# ProDoc_ZYNQ7020_V1_2024-12-19.net
KiCad netlist of a schematic drawn in EasyEDA Pro
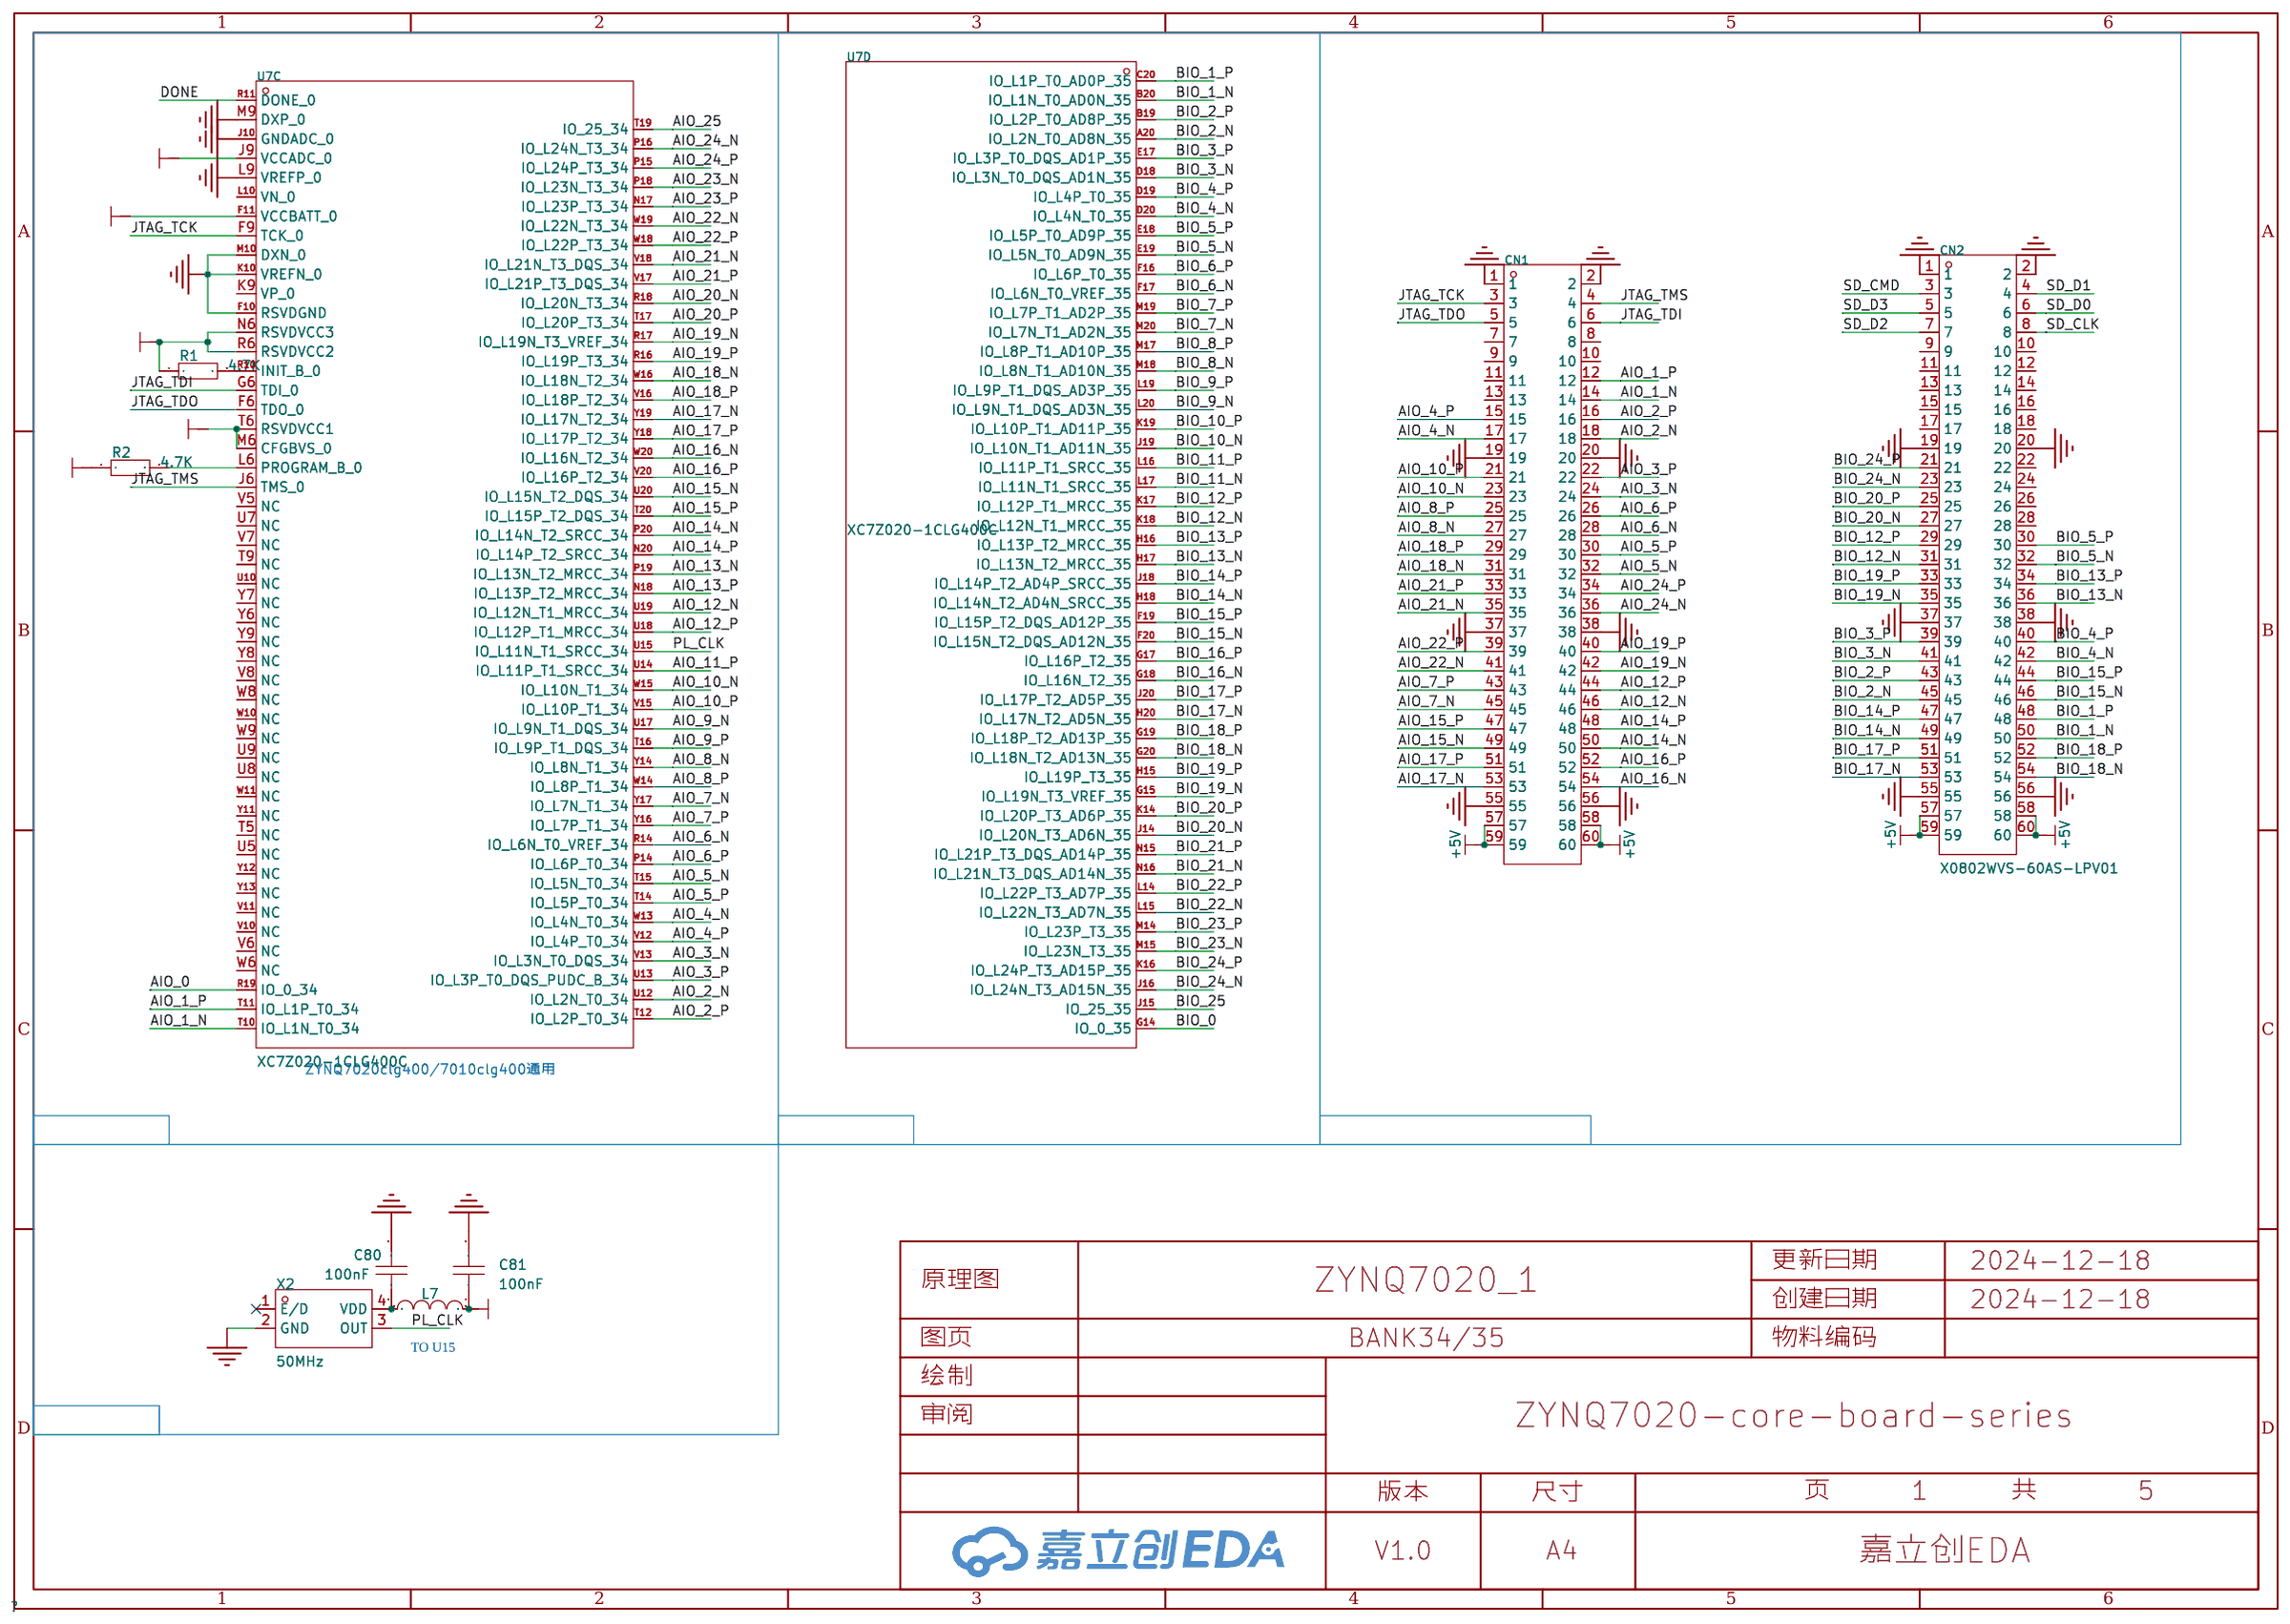
[diagram p0: BANK34/35]
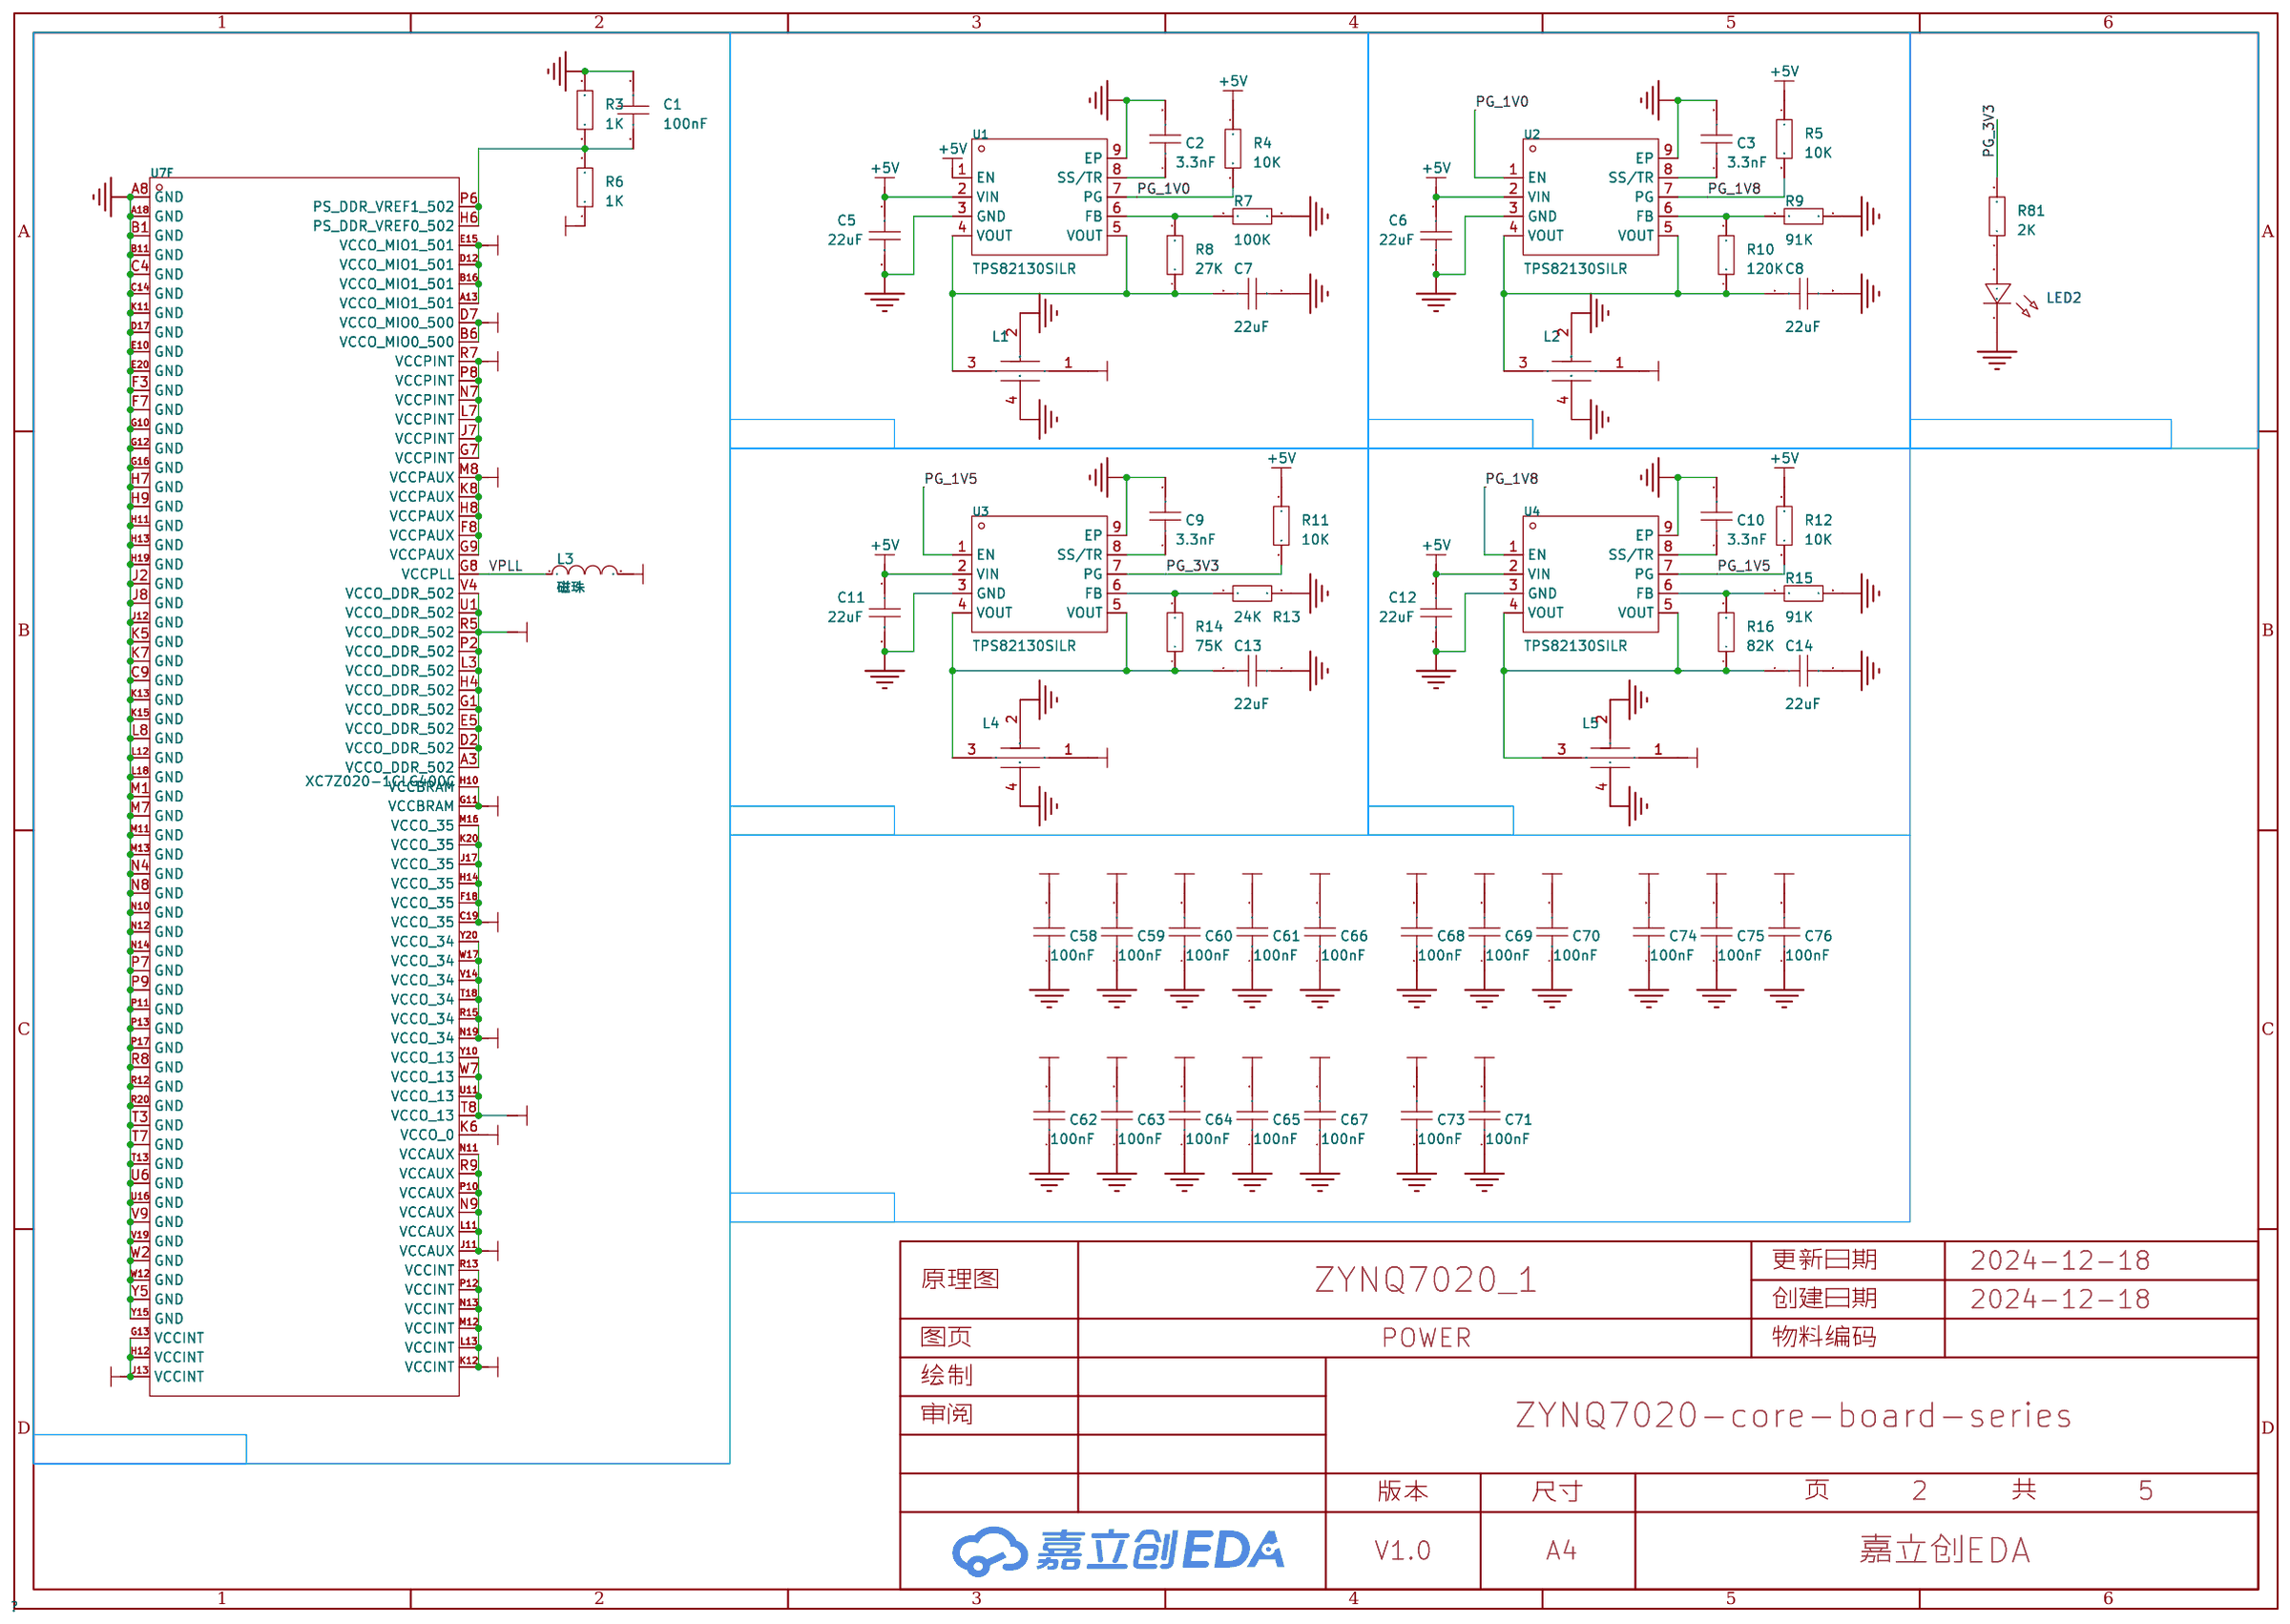
[diagram p1: POWER]
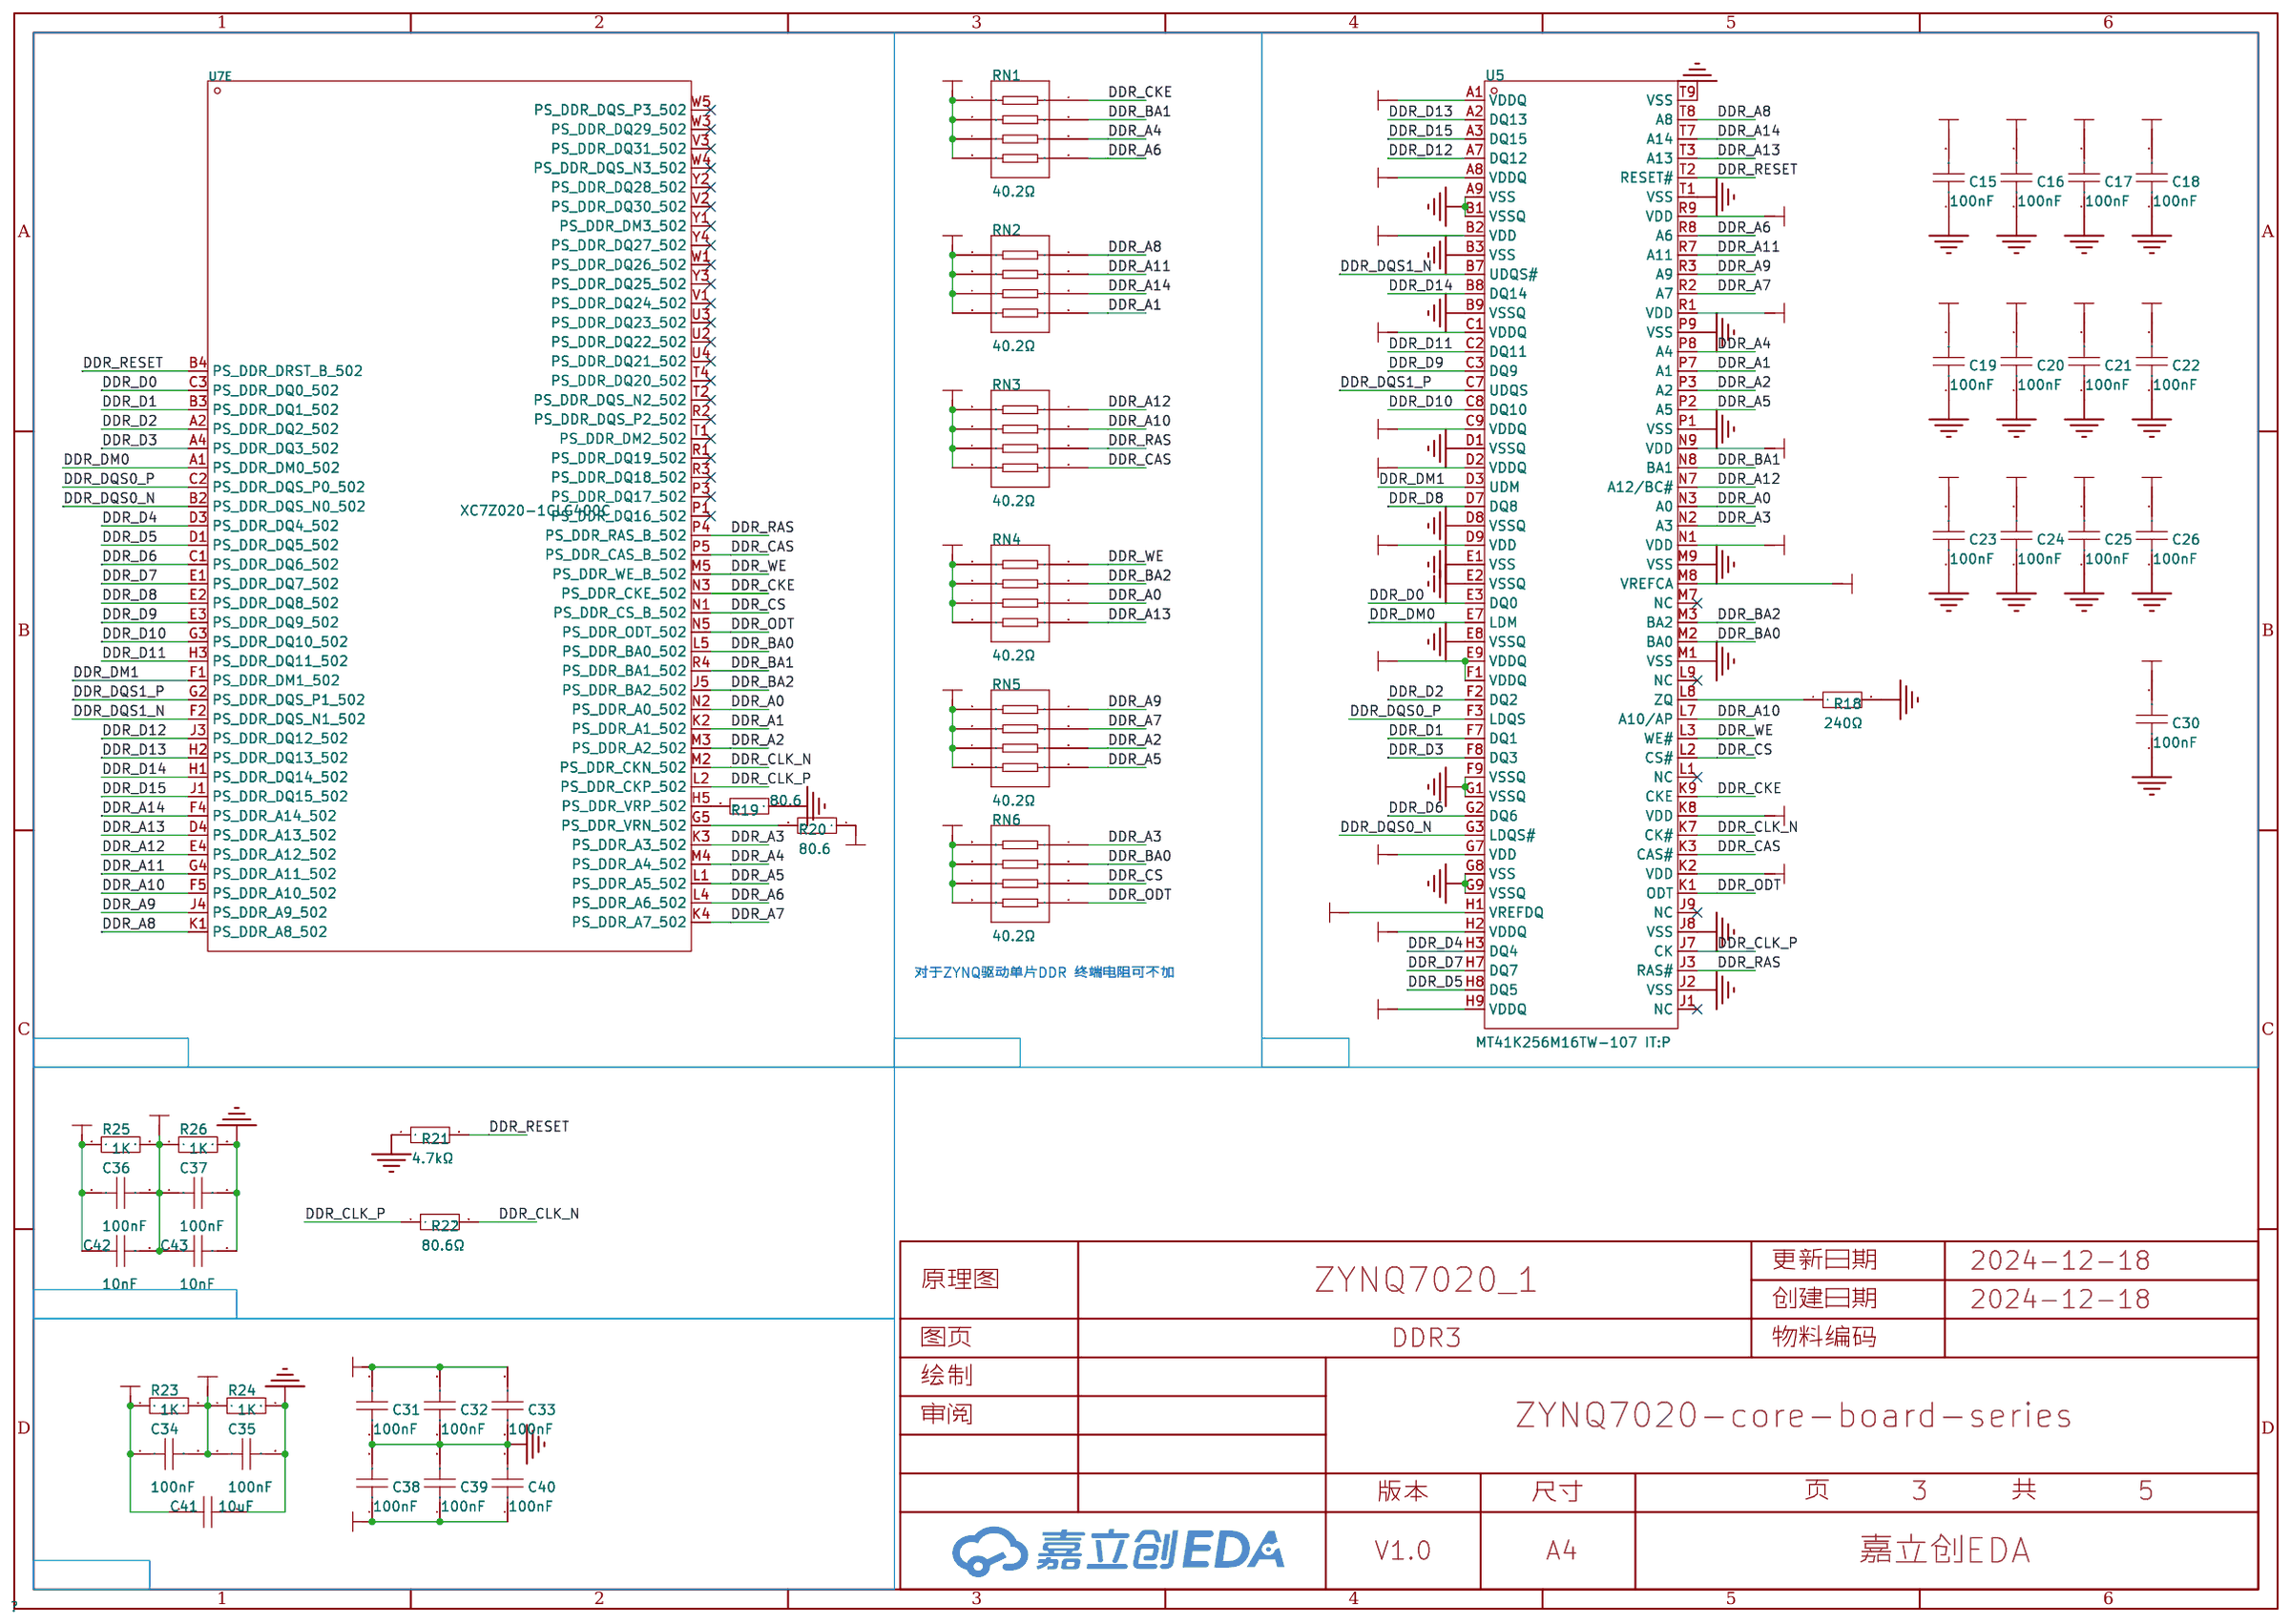
[diagram p2: DDR3]
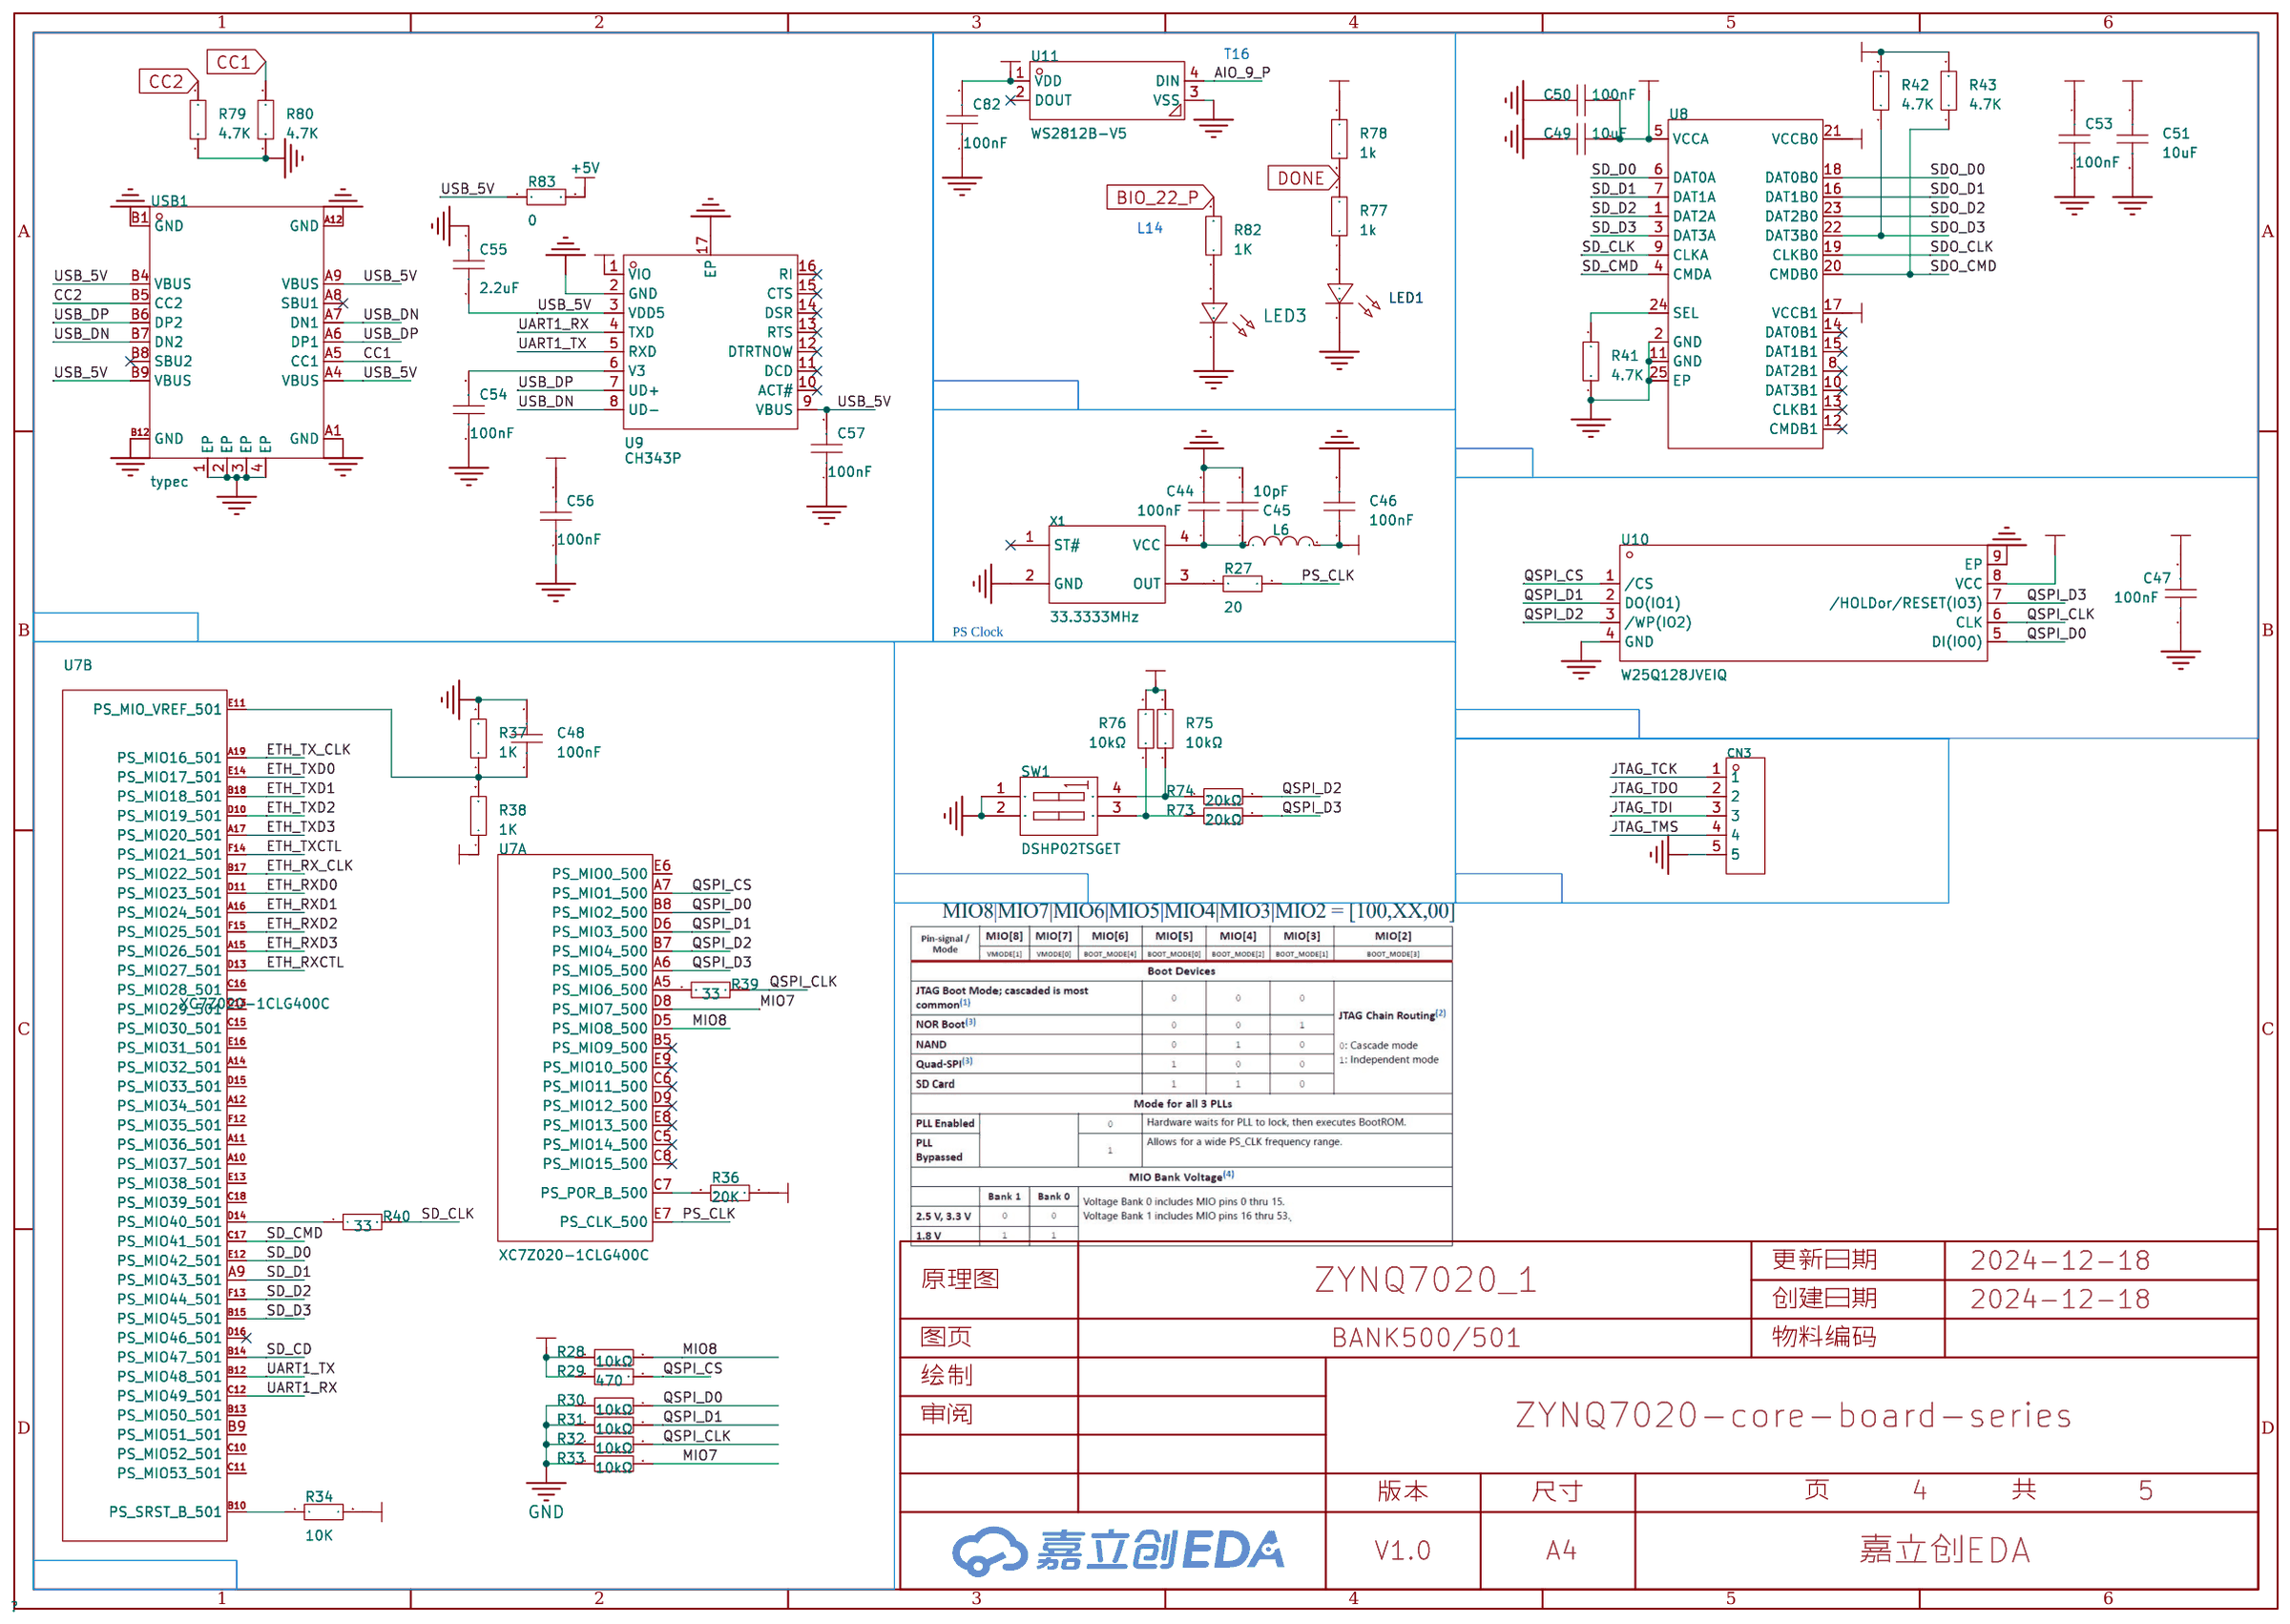
[diagram p3: BANK500/501]
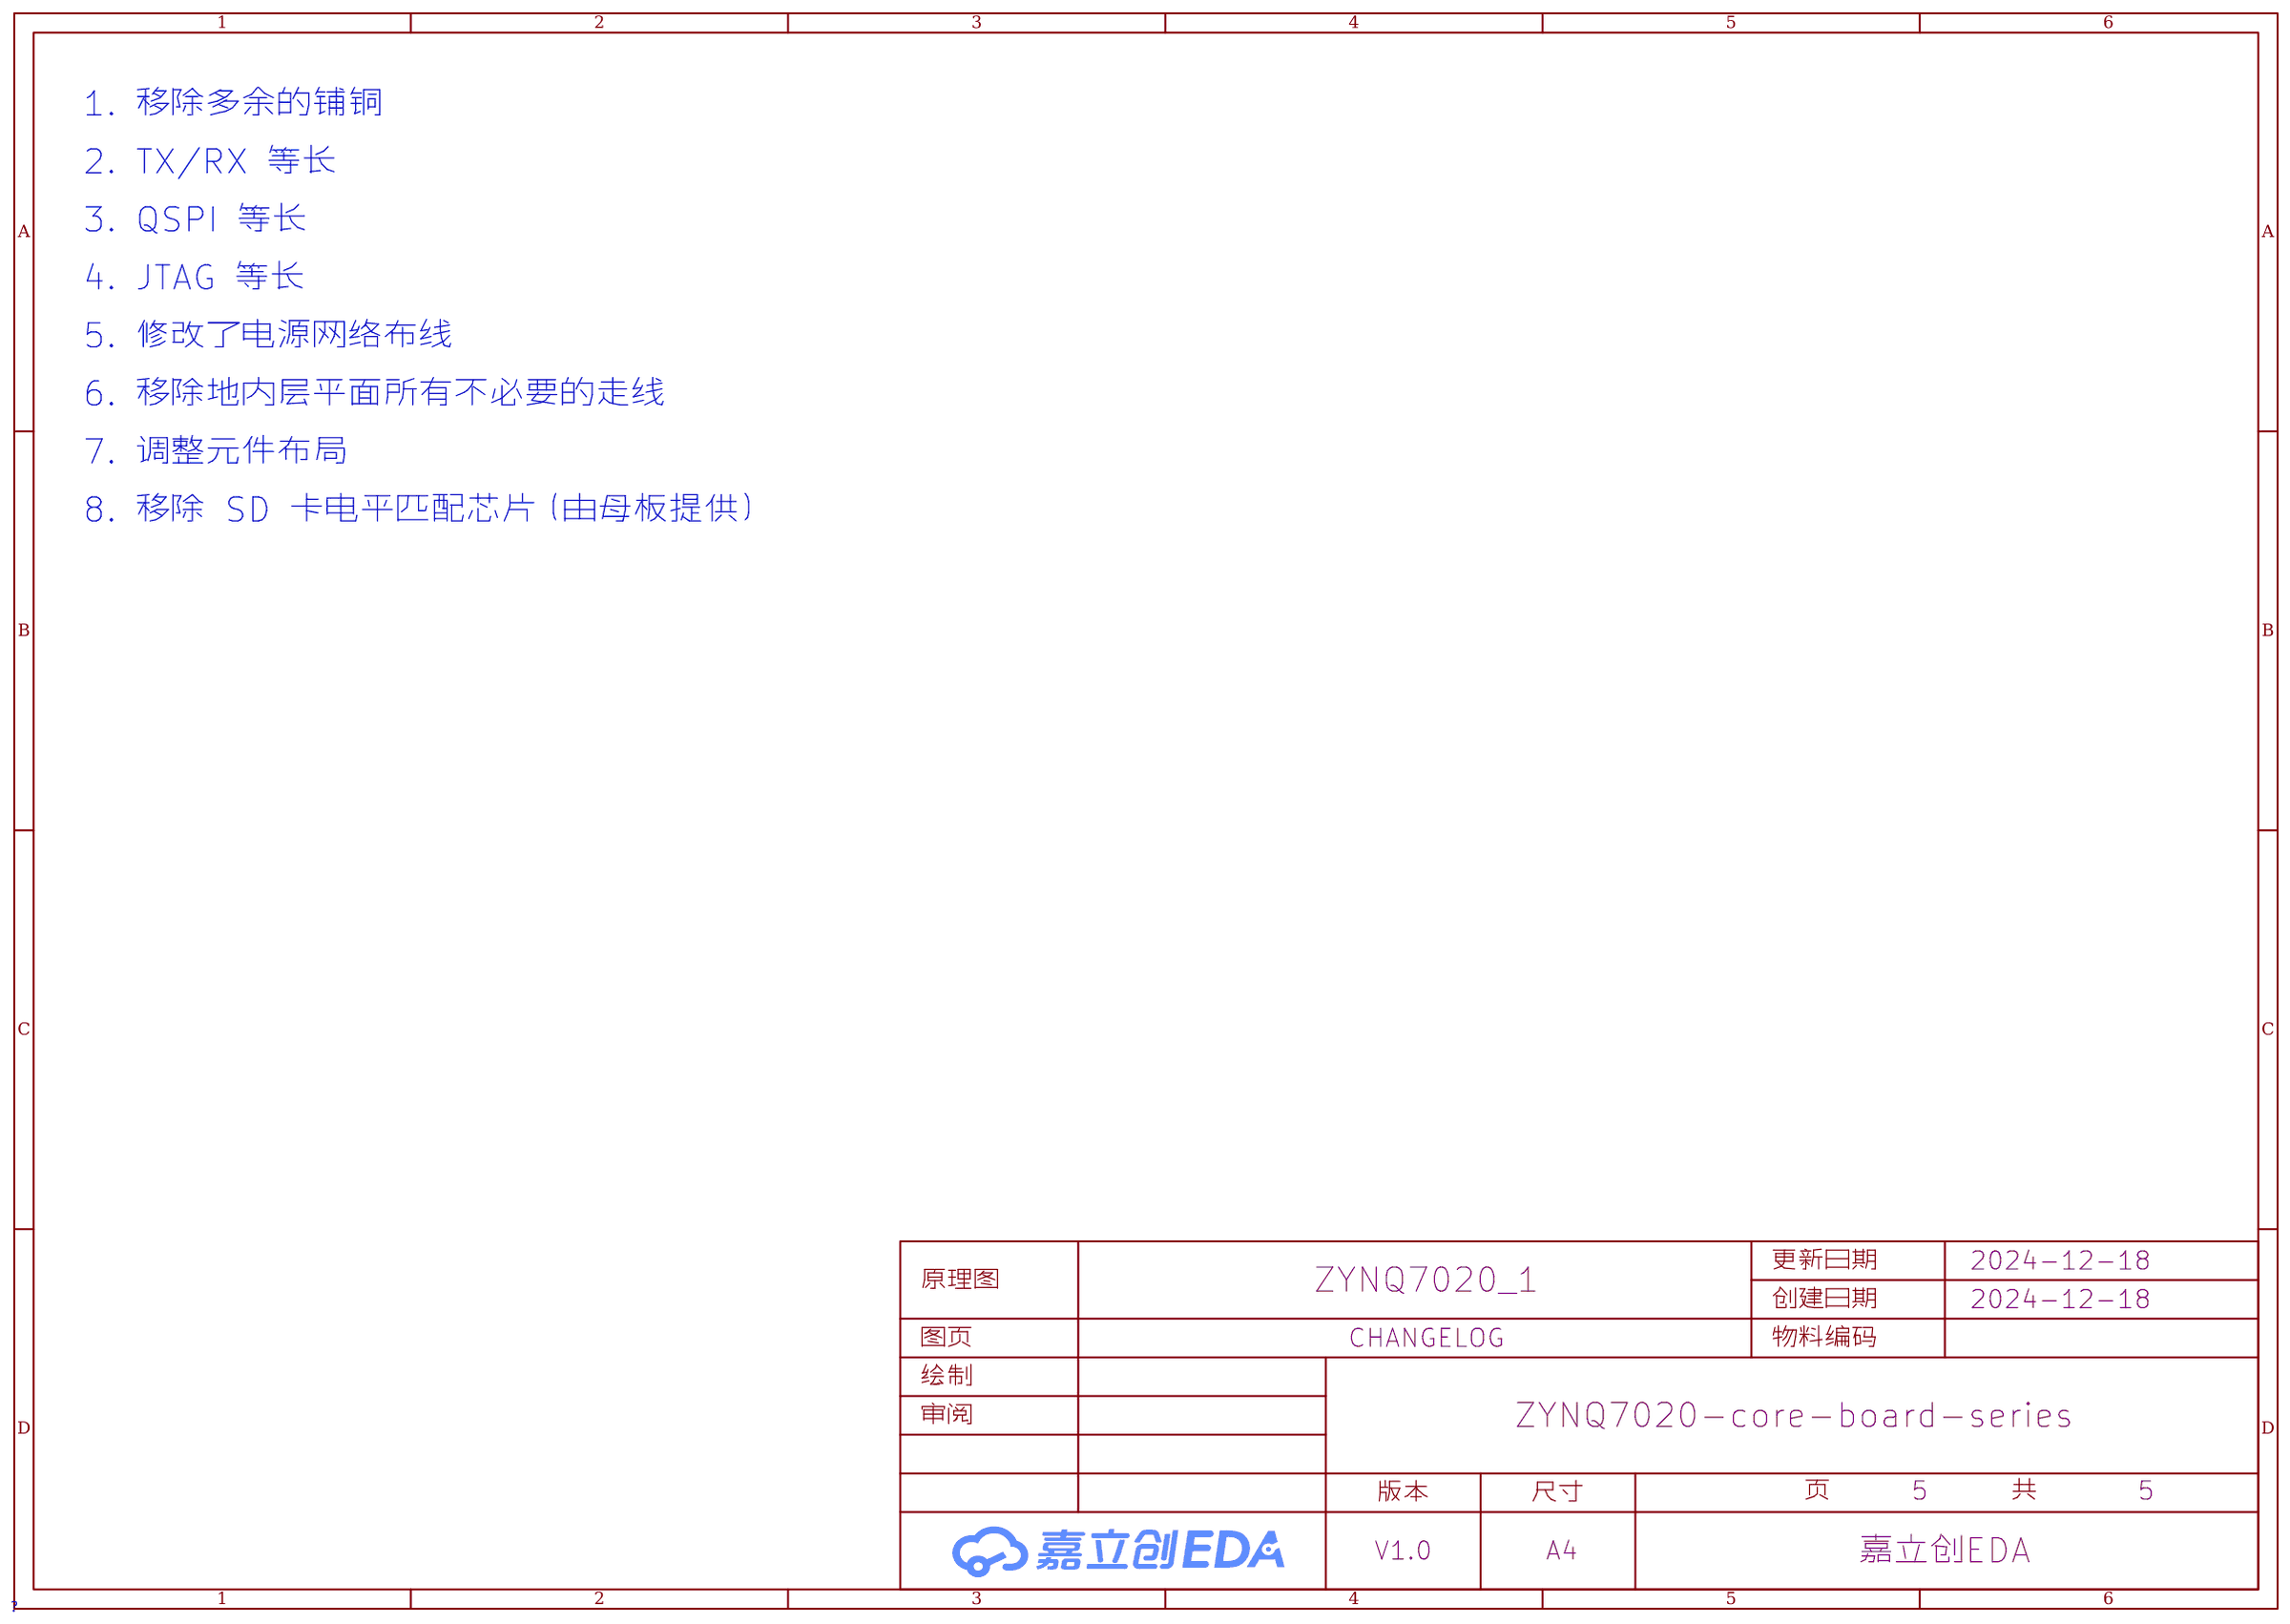
[diagram p4: CHANGELOG]

(export (version "E")
  (design (tool "Eeschema 10.0.6"))
  (components
    (comp (ref "C80")
      (value "100nF")
      (footprint "easyedapro:C0402")
      (libsource (lib "easyedapro") (part "CapAcitance"))
    )
    (comp (ref "C81")
      (value "100nF")
      (footprint "easyedapro:C0402")
      (libsource (lib "easyedapro") (part "CapAcitance"))
    )
    (comp (ref "CN1")
      (value "X0802WVS-60AS-LPV01")
      (footprint "easyedapro:CONN-SMD_60P-P0.80_XKB_X0802WVS-60ADS-LPV01")
      (description "PIN总数:60;间距:0.8mm;行数:2;公母:公;安装方式:立贴;额定电流:500mA;工作温度范围:-25°C~+85°C;")
      (fields (field (name "Manufacturer") "XKB Connectivity(中国星坤)"))
      (libsource (lib "easyedapro") (part "X0802WVS-60ADS-LPV01"))
    )
    (comp (ref "CN2")
      (value "X0802WVS-60AS-LPV01")
      (footprint "easyedapro:CONN-SMD_60P-P0.80_XKB_X0802WVS-60ADS-LPV01")
      (description "PIN总数:60;间距:0.8mm;行数:2;公母:公;安装方式:立贴;额定电流:500mA;工作温度范围:-25°C~+85°C;")
      (fields (field (name "Manufacturer") "XKB Connectivity(中国星坤)"))
      (libsource (lib "easyedapro") (part "X0802WVS-60ADS-LPV01"))
    )
    (comp (ref "L7")
      (value "10uH")
      (footprint "easyedapro:L0603")
      (libsource (lib "easyedapro") (part "SDFL1608S100KTF"))
    )
    (comp (ref "R1") (value "4.7K") (footprint "easyedapro:R0402") (libsource (lib "easyedapro") (part "电阻")))
    (comp (ref "R2") (value "4.7K") (footprint "easyedapro:R0402") (libsource (lib "easyedapro") (part "电阻")))
    (comp (ref "U7")
      (value "XC7Z020-1CLG400C")
      (footprint "easyedapro:FBGA-400_L17.0-W17.0-R20-C20-P0.80-TL")
      (fields (field (name "Manufacturer") "XILINX(赛灵思)"))
      (libsource (lib "easyedapro") (part "XC7Z010-1CLG400C"))
    )
    (comp (ref "X2")
      (value "50MHz")
      (footprint "easyedapro:OSC-SMD_4P-L2.5-W2.0-BL")
      (description "频率:50MHz;工作电压:1.8V~3.3V;频率稳定度:±10ppm;")
      (fields (field (name "Manufacturer Part") "OT252050MJBA4SL") (field (name "Manufacturer") "YXC(扬兴晶振)"))
      (libsource (lib "easyedapro") (part "OT252050MJBA4SL"))
    )
    (comp (ref "C1")
      (value "100nF")
      (footprint "easyedapro:C0402")
      (libsource (lib "easyedapro") (part "CapAcitance"))
    )
    (comp (ref "C2")
      (value "3.3nF")
      (footprint "easyedapro:C0402")
      (libsource (lib "easyedapro") (part "CapAcitance"))
    )
    (comp (ref "C3")
      (value "3.3nF")
      (footprint "easyedapro:C0402")
      (libsource (lib "easyedapro") (part "CapAcitance"))
    )
    (comp (ref "C5")
      (value "22uF")
      (footprint "easyedapro:C0402")
      (libsource (lib "easyedapro") (part "CapAcitance"))
    )
    (comp (ref "C6")
      (value "22uF")
      (footprint "easyedapro:C0402")
      (libsource (lib "easyedapro") (part "CapAcitance"))
    )
    (comp (ref "C7")
      (value "22uF")
      (footprint "easyedapro:C0402")
      (libsource (lib "easyedapro") (part "CapAcitance"))
    )
    (comp (ref "C8")
      (value "22uF")
      (footprint "easyedapro:C0402")
      (libsource (lib "easyedapro") (part "CapAcitance"))
    )
    (comp (ref "C9")
      (value "3.3nF")
      (footprint "easyedapro:C0402")
      (libsource (lib "easyedapro") (part "CapAcitance"))
    )
    (comp (ref "C10")
      (value "3.3nF")
      (footprint "easyedapro:C0402")
      (libsource (lib "easyedapro") (part "CapAcitance"))
    )
    (comp (ref "C11")
      (value "22uF")
      (footprint "easyedapro:C0402")
      (libsource (lib "easyedapro") (part "CapAcitance"))
    )
    (comp (ref "C12")
      (value "22uF")
      (footprint "easyedapro:C0402")
      (libsource (lib "easyedapro") (part "CapAcitance"))
    )
    (comp (ref "C13")
      (value "22uF")
      (footprint "easyedapro:C0402")
      (libsource (lib "easyedapro") (part "CapAcitance"))
    )
    (comp (ref "C14")
      (value "22uF")
      (footprint "easyedapro:C0402")
      (libsource (lib "easyedapro") (part "CapAcitance"))
    )
    (comp (ref "C58")
      (value "100nF")
      (footprint "easyedapro:C0402")
      (libsource (lib "easyedapro") (part "CapAcitance"))
    )
    (comp (ref "C59")
      (value "100nF")
      (footprint "easyedapro:C0402")
      (libsource (lib "easyedapro") (part "CapAcitance"))
    )
    (comp (ref "C60")
      (value "100nF")
      (footprint "easyedapro:C0402")
      (libsource (lib "easyedapro") (part "CapAcitance"))
    )
    (comp (ref "C61")
      (value "100nF")
      (footprint "easyedapro:C0402")
      (libsource (lib "easyedapro") (part "CapAcitance"))
    )
    (comp (ref "C62")
      (value "100nF")
      (footprint "easyedapro:C0402")
      (libsource (lib "easyedapro") (part "CapAcitance"))
    )
    (comp (ref "C63")
      (value "100nF")
      (footprint "easyedapro:C0402")
      (libsource (lib "easyedapro") (part "CapAcitance"))
    )
    (comp (ref "C64")
      (value "100nF")
      (footprint "easyedapro:C0402")
      (libsource (lib "easyedapro") (part "CapAcitance"))
    )
    (comp (ref "C65")
      (value "100nF")
      (footprint "easyedapro:C0402")
      (libsource (lib "easyedapro") (part "CapAcitance"))
    )
    (comp (ref "C66")
      (value "100nF")
      (footprint "easyedapro:C0402")
      (libsource (lib "easyedapro") (part "CapAcitance"))
    )
    (comp (ref "C67")
      (value "100nF")
      (footprint "easyedapro:C0402")
      (libsource (lib "easyedapro") (part "CapAcitance"))
    )
    (comp (ref "C68")
      (value "100nF")
      (footprint "easyedapro:C0402")
      (libsource (lib "easyedapro") (part "CapAcitance"))
    )
    (comp (ref "C69")
      (value "100nF")
      (footprint "easyedapro:C0402")
      (libsource (lib "easyedapro") (part "CapAcitance"))
    )
    (comp (ref "C70")
      (value "100nF")
      (footprint "easyedapro:C0402")
      (libsource (lib "easyedapro") (part "CapAcitance"))
    )
    (comp (ref "C71")
      (value "100nF")
      (footprint "easyedapro:C0402")
      (libsource (lib "easyedapro") (part "CapAcitance"))
    )
    (comp (ref "C73")
      (value "100nF")
      (footprint "easyedapro:C0402")
      (libsource (lib "easyedapro") (part "CapAcitance"))
    )
    (comp (ref "C74")
      (value "100nF")
      (footprint "easyedapro:C0402")
      (libsource (lib "easyedapro") (part "CapAcitance"))
    )
    (comp (ref "C75")
      (value "100nF")
      (footprint "easyedapro:C0402")
      (libsource (lib "easyedapro") (part "CapAcitance"))
    )
    (comp (ref "C76")
      (value "100nF")
      (footprint "easyedapro:C0402")
      (libsource (lib "easyedapro") (part "CapAcitance"))
    )
    (comp (ref "L1")
      (value "NFM21PC104R1E3D")
      (footprint "easyedapro:CAP-SMD_4P-L2.0-W1.25")
      (description "电容量:100nF;精度:±20%;直流电阻:30mΩ;")
      (fields (field (name "Manufacturer") "muRata(村田)"))
      (libsource (lib "easyedapro") (part "NFM21PC104R1E3D"))
    )
    (comp (ref "L2")
      (value "NFM21PC104R1E3D")
      (footprint "easyedapro:CAP-SMD_4P-L2.0-W1.25")
      (description "电容量:100nF;精度:±20%;直流电阻:30mΩ;")
      (fields (field (name "Manufacturer") "muRata(村田)"))
      (libsource (lib "easyedapro") (part "NFM21PC104R1E3D"))
    )
    (comp (ref "L3")
      (value "磁珠")
      (footprint "easyedapro:L0603")
      (libsource (lib "easyedapro") (part "SDFL1608S100KTF"))
    )
    (comp (ref "L4")
      (value "NFM21PC104R1E3D")
      (footprint "easyedapro:CAP-SMD_4P-L2.0-W1.25")
      (description "电容量:100nF;精度:±20%;直流电阻:30mΩ;")
      (fields (field (name "Manufacturer") "muRata(村田)"))
      (libsource (lib "easyedapro") (part "NFM21PC104R1E3D"))
    )
    (comp (ref "L5")
      (value "NFM21PC104R1E3D")
      (footprint "easyedapro:CAP-SMD_4P-L2.0-W1.25")
      (description "电容量:100nF;精度:±20%;直流电阻:30mΩ;")
      (fields (field (name "Manufacturer") "muRata(村田)"))
      (libsource (lib "easyedapro") (part "NFM21PC104R1E3D"))
    )
    (comp (ref "LED2")
      (value "~")
      (footprint "easyedapro:LED_0603")
      (libsource (lib "easyedapro") (part "LED_G"))
    )
    (comp (ref "R3") (value "1K") (footprint "easyedapro:R0402") (libsource (lib "easyedapro") (part "电阻")))
    (comp (ref "R4") (value "10K") (footprint "easyedapro:R0402") (libsource (lib "easyedapro") (part "电阻")))
    (comp (ref "R5") (value "10K") (footprint "easyedapro:R0402") (libsource (lib "easyedapro") (part "电阻")))
    (comp (ref "R6") (value "1K") (footprint "easyedapro:R0402") (libsource (lib "easyedapro") (part "电阻")))
    (comp (ref "R7") (value "100K") (footprint "easyedapro:R0402") (libsource (lib "easyedapro") (part "电阻")))
    (comp (ref "R8") (value "27K") (footprint "easyedapro:R0402") (libsource (lib "easyedapro") (part "电阻")))
    (comp (ref "R9") (value "91K") (footprint "easyedapro:R0402") (libsource (lib "easyedapro") (part "电阻")))
    (comp (ref "R10")
      (value "120K")
      (footprint "easyedapro:R0402")
      (libsource (lib "easyedapro") (part "电阻"))
    )
    (comp (ref "R11") (value "10K") (footprint "easyedapro:R0402") (libsource (lib "easyedapro") (part "电阻")))
    (comp (ref "R12") (value "10K") (footprint "easyedapro:R0402") (libsource (lib "easyedapro") (part "电阻")))
    (comp (ref "R13") (value "24K") (footprint "easyedapro:R0402") (libsource (lib "easyedapro") (part "电阻")))
    (comp (ref "R14") (value "75K") (footprint "easyedapro:R0402") (libsource (lib "easyedapro") (part "电阻")))
    (comp (ref "R15") (value "91K") (footprint "easyedapro:R0402") (libsource (lib "easyedapro") (part "电阻")))
    (comp (ref "R16") (value "82K") (footprint "easyedapro:R0402") (libsource (lib "easyedapro") (part "电阻")))
    (comp (ref "R81") (value "2K") (footprint "easyedapro:R0402") (libsource (lib "easyedapro") (part "电阻")))
    (comp (ref "U1")
      (value "TPS82130SILR")
      (footprint "easyedapro:USIP-8_L3.0-W2.8-P0.65-TL-EP")
      (description "输入电压(DC):3V~17V;输出电压:900mV~6V;输出电流(最大值):3A;")
      (fields (field (name "Manufacturer") "TI(德州仪器)"))
      (libsource (lib "easyedapro") (part "TPS82130SILR"))
    )
    (comp (ref "U2")
      (value "TPS82130SILR")
      (footprint "easyedapro:USIP-8_L3.0-W2.8-P0.65-TL-EP")
      (description "输入电压(DC):3V~17V;输出电压:900mV~6V;输出电流(最大值):3A;")
      (fields (field (name "Manufacturer") "TI(德州仪器)"))
      (libsource (lib "easyedapro") (part "TPS82130SILR"))
    )
    (comp (ref "U3")
      (value "TPS82130SILR")
      (footprint "easyedapro:USIP-8_L3.0-W2.8-P0.65-TL-EP")
      (description "输入电压(DC):3V~17V;输出电压:900mV~6V;输出电流(最大值):3A;")
      (fields (field (name "Manufacturer") "TI(德州仪器)"))
      (libsource (lib "easyedapro") (part "TPS82130SILR"))
    )
    (comp (ref "U4")
      (value "TPS82130SILR")
      (footprint "easyedapro:USIP-8_L3.0-W2.8-P0.65-TL-EP")
      (description "输入电压(DC):3V~17V;输出电压:900mV~6V;输出电流(最大值):3A;")
      (fields (field (name "Manufacturer") "TI(德州仪器)"))
      (libsource (lib "easyedapro") (part "TPS82130SILR"))
    )
    (comp (ref "C15")
      (value "100nF")
      (footprint "easyedapro:C0402")
      (libsource (lib "easyedapro") (part "CapAcitance"))
    )
    (comp (ref "C16")
      (value "100nF")
      (footprint "easyedapro:C0402")
      (libsource (lib "easyedapro") (part "CapAcitance"))
    )
    (comp (ref "C17")
      (value "100nF")
      (footprint "easyedapro:C0402")
      (libsource (lib "easyedapro") (part "CapAcitance"))
    )
    (comp (ref "C18")
      (value "100nF")
      (footprint "easyedapro:C0402")
      (libsource (lib "easyedapro") (part "CapAcitance"))
    )
    (comp (ref "C19")
      (value "100nF")
      (footprint "easyedapro:C0402")
      (libsource (lib "easyedapro") (part "CapAcitance"))
    )
    (comp (ref "C20")
      (value "100nF")
      (footprint "easyedapro:C0402")
      (libsource (lib "easyedapro") (part "CapAcitance"))
    )
    (comp (ref "C21")
      (value "100nF")
      (footprint "easyedapro:C0402")
      (libsource (lib "easyedapro") (part "CapAcitance"))
    )
    (comp (ref "C22")
      (value "100nF")
      (footprint "easyedapro:C0402")
      (libsource (lib "easyedapro") (part "CapAcitance"))
    )
    (comp (ref "C23")
      (value "100nF")
      (footprint "easyedapro:C0402")
      (libsource (lib "easyedapro") (part "CapAcitance"))
    )
    (comp (ref "C24")
      (value "100nF")
      (footprint "easyedapro:C0402")
      (libsource (lib "easyedapro") (part "CapAcitance"))
    )
    (comp (ref "C25")
      (value "100nF")
      (footprint "easyedapro:C0402")
      (libsource (lib "easyedapro") (part "CapAcitance"))
    )
    (comp (ref "C26")
      (value "100nF")
      (footprint "easyedapro:C0402")
      (libsource (lib "easyedapro") (part "CapAcitance"))
    )
    (comp (ref "C30")
      (value "100nF")
      (footprint "easyedapro:C0402")
      (libsource (lib "easyedapro") (part "CapAcitance"))
    )
    (comp (ref "C31")
      (value "100nF")
      (footprint "easyedapro:C0402")
      (libsource (lib "easyedapro") (part "CapAcitance"))
    )
    (comp (ref "C32")
      (value "100nF")
      (footprint "easyedapro:C0402")
      (libsource (lib "easyedapro") (part "CapAcitance"))
    )
    (comp (ref "C33")
      (value "100nF")
      (footprint "easyedapro:C0402")
      (libsource (lib "easyedapro") (part "CapAcitance"))
    )
    (comp (ref "C34")
      (value "100nF")
      (footprint "easyedapro:C0402")
      (libsource (lib "easyedapro") (part "CapAcitance"))
    )
    (comp (ref "C35")
      (value "100nF")
      (footprint "easyedapro:C0402")
      (libsource (lib "easyedapro") (part "CapAcitance"))
    )
    (comp (ref "C36")
      (value "100nF")
      (footprint "easyedapro:C0402")
      (libsource (lib "easyedapro") (part "CapAcitance"))
    )
    (comp (ref "C37")
      (value "100nF")
      (footprint "easyedapro:C0402")
      (libsource (lib "easyedapro") (part "CapAcitance"))
    )
    (comp (ref "C38")
      (value "100nF")
      (footprint "easyedapro:C0402")
      (libsource (lib "easyedapro") (part "CapAcitance"))
    )
    (comp (ref "C39")
      (value "100nF")
      (footprint "easyedapro:C0402")
      (libsource (lib "easyedapro") (part "CapAcitance"))
    )
    (comp (ref "C40")
      (value "100nF")
      (footprint "easyedapro:C0402")
      (libsource (lib "easyedapro") (part "CapAcitance"))
    )
    (comp (ref "C41")
      (value "10uF")
      (footprint "easyedapro:C0402")
      (libsource (lib "easyedapro") (part "CapAcitance"))
    )
    (comp (ref "C42")
      (value "10nF")
      (footprint "easyedapro:C0402")
      (libsource (lib "easyedapro") (part "CapAcitance"))
    )
    (comp (ref "C43")
      (value "10nF")
      (footprint "easyedapro:C0402")
      (libsource (lib "easyedapro") (part "CapAcitance"))
    )
    (comp (ref "R18")
      (value "240Ω")
      (footprint "easyedapro:R0402")
      (libsource (lib "easyedapro") (part "电阻"))
    )
    (comp (ref "R19")
      (value "80.6")
      (footprint "easyedapro:R0402")
      (libsource (lib "easyedapro") (part "电阻"))
    )
    (comp (ref "R20")
      (value "80.6")
      (footprint "easyedapro:R0402")
      (libsource (lib "easyedapro") (part "电阻"))
    )
    (comp (ref "R21")
      (value "4.7kΩ")
      (footprint "easyedapro:R0402")
      (libsource (lib "easyedapro") (part "电阻"))
    )
    (comp (ref "R22")
      (value "80.6Ω")
      (footprint "easyedapro:R0402")
      (libsource (lib "easyedapro") (part "电阻"))
    )
    (comp (ref "R23") (value "1K") (footprint "easyedapro:R0402") (libsource (lib "easyedapro") (part "电阻")))
    (comp (ref "R24") (value "1K") (footprint "easyedapro:R0402") (libsource (lib "easyedapro") (part "电阻")))
    (comp (ref "R25") (value "1K") (footprint "easyedapro:R0402") (libsource (lib "easyedapro") (part "电阻")))
    (comp (ref "R26") (value "1K") (footprint "easyedapro:R0402") (libsource (lib "easyedapro") (part "电阻")))
    (comp (ref "RN1")
      (value "40.2Ω")
      (footprint "easyedapro:RES-ARRAY-SMD_0402-8P-L2.0-W1.0-BL")
      (description "阻值:49.9Ω;精度:±1%;单个元件功率:62.5mW;电阻器数:4;")
      (fields (field (name "Manufacturer Part") "YC124-FR-0749R9L") (field (name "Manufacturer") "YAGEO(国巨)"))
      (libsource (lib "easyedapro") (part "YC124-FR-0749R9L"))
    )
    (comp (ref "RN2")
      (value "40.2Ω")
      (footprint "easyedapro:RES-ARRAY-SMD_0402-8P-L2.0-W1.0-BL")
      (description "阻值:49.9Ω;精度:±1%;单个元件功率:62.5mW;电阻器数:4;")
      (fields (field (name "Manufacturer Part") "YC124-FR-0749R9L") (field (name "Manufacturer") "YAGEO(国巨)"))
      (libsource (lib "easyedapro") (part "YC124-FR-0749R9L"))
    )
    (comp (ref "RN3")
      (value "40.2Ω")
      (footprint "easyedapro:RES-ARRAY-SMD_0402-8P-L2.0-W1.0-BL")
      (description "阻值:49.9Ω;精度:±1%;单个元件功率:62.5mW;电阻器数:4;")
      (fields (field (name "Manufacturer Part") "YC124-FR-0749R9L") (field (name "Manufacturer") "YAGEO(国巨)"))
      (libsource (lib "easyedapro") (part "YC124-FR-0749R9L"))
    )
    (comp (ref "RN4")
      (value "40.2Ω")
      (footprint "easyedapro:RES-ARRAY-SMD_0402-8P-L2.0-W1.0-BL")
      (description "阻值:49.9Ω;精度:±1%;单个元件功率:62.5mW;电阻器数:4;")
      (fields (field (name "Manufacturer Part") "YC124-FR-0749R9L") (field (name "Manufacturer") "YAGEO(国巨)"))
      (libsource (lib "easyedapro") (part "YC124-FR-0749R9L"))
    )
    (comp (ref "RN5")
      (value "40.2Ω")
      (footprint "easyedapro:RES-ARRAY-SMD_0402-8P-L2.0-W1.0-BL")
      (description "阻值:49.9Ω;精度:±1%;单个元件功率:62.5mW;电阻器数:4;")
      (fields (field (name "Manufacturer Part") "YC124-FR-0749R9L") (field (name "Manufacturer") "YAGEO(国巨)"))
      (libsource (lib "easyedapro") (part "YC124-FR-0749R9L"))
    )
    (comp (ref "RN6")
      (value "40.2Ω")
      (footprint "easyedapro:RES-ARRAY-SMD_0402-8P-L2.0-W1.0-BL")
      (description "阻值:49.9Ω;精度:±1%;单个元件功率:62.5mW;电阻器数:4;")
      (fields (field (name "Manufacturer Part") "YC124-FR-0749R9L") (field (name "Manufacturer") "YAGEO(国巨)"))
      (libsource (lib "easyedapro") (part "YC124-FR-0749R9L"))
    )
    (comp (ref "U5")
      (value "MT41K256M16TW-107 IT:P")
      (footprint "easyedapro:FBGA-96_L14.0-W8.0-R16-C6-P0.80-TL")
      (fields (field (name "Manufacturer") "micron(镁光)"))
      (libsource (lib "easyedapro") (part "MT41K256M16TW-107IT{colon}P"))
    )
    (comp (ref "C44")
      (value "100nF")
      (footprint "easyedapro:C0402")
      (libsource (lib "easyedapro") (part "CapAcitance"))
    )
    (comp (ref "C45")
      (value "10pF")
      (footprint "easyedapro:C0402")
      (libsource (lib "easyedapro") (part "CapAcitance"))
    )
    (comp (ref "C46")
      (value "100nF")
      (footprint "easyedapro:C0402")
      (libsource (lib "easyedapro") (part "CapAcitance"))
    )
    (comp (ref "C47")
      (value "100nF")
      (footprint "easyedapro:C0402")
      (libsource (lib "easyedapro") (part "CapAcitance"))
    )
    (comp (ref "C48")
      (value "100nF")
      (footprint "easyedapro:C0402")
      (libsource (lib "easyedapro") (part "CapAcitance"))
    )
    (comp (ref "C49")
      (value "10uF")
      (footprint "easyedapro:C0402")
      (libsource (lib "easyedapro") (part "CapAcitance"))
    )
    (comp (ref "C50")
      (value "100nF")
      (footprint "easyedapro:C0402")
      (libsource (lib "easyedapro") (part "CapAcitance"))
    )
    (comp (ref "C51")
      (value "10uF")
      (footprint "easyedapro:C0402")
      (libsource (lib "easyedapro") (part "CapAcitance"))
    )
    (comp (ref "C53")
      (value "100nF")
      (footprint "easyedapro:C0402")
      (libsource (lib "easyedapro") (part "CapAcitance"))
    )
    (comp (ref "C54")
      (value "100nF")
      (footprint "easyedapro:C0402")
      (libsource (lib "easyedapro") (part "CapAcitance"))
    )
    (comp (ref "C55")
      (value "2.2uF")
      (footprint "easyedapro:C0402")
      (libsource (lib "easyedapro") (part "CapAcitance"))
    )
    (comp (ref "C56")
      (value "100nF")
      (footprint "easyedapro:C0402")
      (libsource (lib "easyedapro") (part "CapAcitance"))
    )
    (comp (ref "C57")
      (value "100nF")
      (footprint "easyedapro:C0402")
      (libsource (lib "easyedapro") (part "CapAcitance"))
    )
    (comp (ref "C82")
      (value "100nF")
      (footprint "easyedapro:C0402")
      (libsource (lib "easyedapro") (part "CapAcitance"))
    )
    (comp (ref "CN3")
      (value "1125-1105G0Z087CR01")
      (footprint "easyedapro:CONN-SMD_1125-1105G0Z087CR01")
      (fields (field (name "Manufacturer") "Wcon(维峰电子)"))
      (libsource (lib "easyedapro") (part "1125-1105G0Z087CR01"))
    )
    (comp (ref "L6")
      (value "10uH")
      (footprint "easyedapro:L0603")
      (libsource (lib "easyedapro") (part "SDFL1608S100KTF"))
    )
    (comp (ref "LED1")
      (value "~")
      (footprint "easyedapro:LED_0603")
      (libsource (lib "easyedapro") (part "LED_G"))
    )
    (comp (ref "LED3")
      (value "~")
      (footprint "easyedapro:LED_0603")
      (libsource (lib "easyedapro") (part "LED_R"))
    )
    (comp (ref "R27") (value "20") (footprint "easyedapro:R0402") (libsource (lib "easyedapro") (part "电阻")))
    (comp (ref "R28")
      (value "10kΩ")
      (footprint "easyedapro:R0402")
      (description "电阻类型:厚膜电阻;阻值:20kΩ;精度:±1%;功率:62.5mW;")
      (fields
        (field (name "Manufacturer Part") "0402WGF2002TCE")
        (field (name "Manufacturer") "UNI-ROYAL(厚声)")
      )
      (libsource (lib "easyedapro") (part "0402WGF2002TCE"))
    )
    (comp (ref "R29")
      (value "470")
      (footprint "easyedapro:R0402")
      (description "电阻类型:厚膜电阻;阻值:20kΩ;精度:±1%;功率:62.5mW;")
      (fields
        (field (name "Manufacturer Part") "0402WGF2002TCE")
        (field (name "Manufacturer") "UNI-ROYAL(厚声)")
      )
      (libsource (lib "easyedapro") (part "0402WGF2002TCE"))
    )
    (comp (ref "R30")
      (value "10kΩ")
      (footprint "easyedapro:R0402")
      (description "电阻类型:厚膜电阻;阻值:20kΩ;精度:±1%;功率:62.5mW;")
      (fields
        (field (name "Manufacturer Part") "0402WGF2002TCE")
        (field (name "Manufacturer") "UNI-ROYAL(厚声)")
      )
      (libsource (lib "easyedapro") (part "0402WGF2002TCE"))
    )
    (comp (ref "R31")
      (value "10kΩ")
      (footprint "easyedapro:R0402")
      (description "电阻类型:厚膜电阻;阻值:20kΩ;精度:±1%;功率:62.5mW;")
      (fields
        (field (name "Manufacturer Part") "0402WGF2002TCE")
        (field (name "Manufacturer") "UNI-ROYAL(厚声)")
      )
      (libsource (lib "easyedapro") (part "0402WGF2002TCE"))
    )
    (comp (ref "R32")
      (value "10kΩ")
      (footprint "easyedapro:R0402")
      (description "电阻类型:厚膜电阻;阻值:20kΩ;精度:±1%;功率:62.5mW;")
      (fields
        (field (name "Manufacturer Part") "0402WGF2002TCE")
        (field (name "Manufacturer") "UNI-ROYAL(厚声)")
      )
      (libsource (lib "easyedapro") (part "0402WGF2002TCE"))
    )
    (comp (ref "R33")
      (value "10kΩ")
      (footprint "easyedapro:R0402")
      (description "电阻类型:厚膜电阻;阻值:20kΩ;精度:±1%;功率:62.5mW;")
      (fields
        (field (name "Manufacturer Part") "0402WGF2002TCE")
        (field (name "Manufacturer") "UNI-ROYAL(厚声)")
      )
      (libsource (lib "easyedapro") (part "0402WGF2002TCE"))
    )
    (comp (ref "R34") (value "10K") (footprint "easyedapro:R0402") (libsource (lib "easyedapro") (part "电阻")))
    (comp (ref "R36") (value "20K") (footprint "easyedapro:R0402") (libsource (lib "easyedapro") (part "电阻")))
    (comp (ref "R37") (value "1K") (footprint "easyedapro:R0402") (libsource (lib "easyedapro") (part "电阻")))
    (comp (ref "R38") (value "1K") (footprint "easyedapro:R0402") (libsource (lib "easyedapro") (part "电阻")))
    (comp (ref "R39") (value "33") (footprint "easyedapro:R0402") (libsource (lib "easyedapro") (part "电阻")))
    (comp (ref "R40") (value "33") (footprint "easyedapro:R0402") (libsource (lib "easyedapro") (part "电阻")))
    (comp (ref "R41")
      (value "4.7K")
      (footprint "easyedapro:R0402")
      (libsource (lib "easyedapro") (part "电阻"))
    )
    (comp (ref "R42")
      (value "4.7K")
      (footprint "easyedapro:R0402")
      (libsource (lib "easyedapro") (part "电阻"))
    )
    (comp (ref "R43")
      (value "4.7K")
      (footprint "easyedapro:R0402")
      (libsource (lib "easyedapro") (part "电阻"))
    )
    (comp (ref "R73")
      (value "20kΩ")
      (footprint "easyedapro:R0402")
      (description "电阻类型:厚膜电阻;阻值:20kΩ;精度:±1%;功率:62.5mW;")
      (fields
        (field (name "Manufacturer Part") "0402WGF2002TCE")
        (field (name "Manufacturer") "UNI-ROYAL(厚声)")
      )
      (libsource (lib "easyedapro") (part "0402WGF2002TCE"))
    )
    (comp (ref "R74")
      (value "20kΩ")
      (footprint "easyedapro:R0402")
      (description "电阻类型:厚膜电阻;阻值:20kΩ;精度:±1%;功率:62.5mW;")
      (fields
        (field (name "Manufacturer Part") "0402WGF2002TCE")
        (field (name "Manufacturer") "UNI-ROYAL(厚声)")
      )
      (libsource (lib "easyedapro") (part "0402WGF2002TCE"))
    )
    (comp (ref "R75")
      (value "10kΩ")
      (footprint "easyedapro:R0402")
      (description "电阻类型:厚膜电阻;阻值:20kΩ;精度:±1%;功率:62.5mW;")
      (fields
        (field (name "Manufacturer Part") "0402WGF2002TCE")
        (field (name "Manufacturer") "UNI-ROYAL(厚声)")
      )
      (libsource (lib "easyedapro") (part "0402WGF2002TCE"))
    )
    (comp (ref "R76")
      (value "10kΩ")
      (footprint "easyedapro:R0402")
      (description "电阻类型:厚膜电阻;阻值:20kΩ;精度:±1%;功率:62.5mW;")
      (fields
        (field (name "Manufacturer Part") "0402WGF2002TCE")
        (field (name "Manufacturer") "UNI-ROYAL(厚声)")
      )
      (libsource (lib "easyedapro") (part "0402WGF2002TCE"))
    )
    (comp (ref "R77") (value "1k") (footprint "easyedapro:R0402") (libsource (lib "easyedapro") (part "电阻")))
    (comp (ref "R78") (value "1k") (footprint "easyedapro:R0402") (libsource (lib "easyedapro") (part "电阻")))
    (comp (ref "R79")
      (value "4.7K")
      (footprint "easyedapro:R0402")
      (libsource (lib "easyedapro") (part "电阻"))
    )
    (comp (ref "R80")
      (value "4.7K")
      (footprint "easyedapro:R0402")
      (libsource (lib "easyedapro") (part "电阻"))
    )
    (comp (ref "R82") (value "1K") (footprint "easyedapro:R0402") (libsource (lib "easyedapro") (part "电阻")))
    (comp (ref "R83") (value "0") (footprint "easyedapro:R0402") (libsource (lib "easyedapro") (part "电阻")))
    (comp (ref "SW1")
      (value "DSHP02TSGET")
      (footprint "easyedapro:SW-SMD_4P_DSHP02TSGET")
      (description "类型:平拨，凹槽式;电路结构:单刀单掷;开关位数:2;引脚间距:1.27mm;颜色:黑色;")
      (fields (field (name "Manufacturer") "YE"))
      (libsource (lib "easyedapro") (part "DSHP02TSGET"))
    )
    (comp (ref "U8")
      (value "~")
      (footprint "easyedapro:WQFN-24_L4.0-W4.0-P0.50-TL-EP2.5")
      (description "TXS02612 具有电压电平转换功能的 SDIO 端口扩展器")
      (fields (field (name "Manufacturer Part") "TXS02612RTWR") (field (name "Manufacturer") "TI(德州仪器)"))
      (libsource (lib "easyedapro") (part "TXS02612RTWR"))
    )
    (comp (ref "U9")
      (value "CH343P")
      (footprint "easyedapro:TQFN-16_L3.0-W3.0-P0.50-BL-EP1.7")
      (description "应用功能:-;接口协议:-;")
      (fields (field (name "Manufacturer") "WCH(南京沁恒)"))
      (libsource (lib "easyedapro") (part "CH343P"))
    )
    (comp (ref "U10")
      (value "W25Q128JVEIQ")
      (footprint "easyedapro:WSON-8_L6.0-W8.0-P1.27-BL-EP")
      (fields (field (name "Manufacturer") "WINBOND(华邦)"))
      (libsource (lib "easyedapro") (part "W25Q128JVEIQ"))
    )
    (comp (ref "U11")
      (value "WS2812B-V5")
      (footprint "easyedapro:LED-SMD_4P-L5.0-W5.0-TL_WS2812B-B")
      (libsource (lib "easyedapro") (part "WS2812B-V5"))
    )
    (comp (ref "USB1")
      (value "typec")
      (footprint "easyedapro:USB-C-SMD_KH-TYPE-C-16P")
      (libsource (lib "easyedapro") (part "TYPEC_C9900016956"))
    )
    (comp (ref "X1")
      (value "33.3333MHz")
      (footprint "easyedapro:OSC-SMD_4P-L3.2-W2.5-BL")
      (description "频率:50MHz;工作电压:3.3V;")
      (fields (field (name "Manufacturer Part") "Q33310F700622") (field (name "Manufacturer") "EPSON(爱普生)"))
      (libsource (lib "easyedapro") (part "Q33310F70062200"))
    )
  )
  (nets
    (net (code "1") (name "+5V") (class "Default")
      (node (ref "C11") (pin "1") (pinfunction "1_1") (pintype "input"))
      (node (ref "C12") (pin "1") (pinfunction "1_1") (pintype "input"))
      (node (ref "C5") (pin "1") (pinfunction "1_1") (pintype "input"))
      (node (ref "C6") (pin "1") (pinfunction "1_1") (pintype "input"))
      (node (ref "CN1") (pin "57") (pinfunction "57_57") (pintype "input"))
      (node (ref "CN1") (pin "58") (pinfunction "58_58") (pintype "input"))
      (node (ref "CN1") (pin "59") (pinfunction "59_59") (pintype "input"))
      (node (ref "CN1") (pin "60") (pinfunction "60_60") (pintype "input"))
      (node (ref "CN2") (pin "57") (pinfunction "57_57") (pintype "input"))
      (node (ref "CN2") (pin "58") (pinfunction "58_58") (pintype "input"))
      (node (ref "CN2") (pin "59") (pinfunction "59_59") (pintype "input"))
      (node (ref "CN2") (pin "60") (pinfunction "60_60") (pintype "input"))
      (node (ref "R11") (pin "1") (pinfunction "1_1") (pintype "input"))
      (node (ref "R12") (pin "2") (pinfunction "2_2") (pintype "input"))
      (node (ref "R4") (pin "1") (pinfunction "1_1") (pintype "input"))
      (node (ref "R5") (pin "1") (pinfunction "1_1") (pintype "input"))
      (node (ref "R83") (pin "2") (pinfunction "2_2") (pintype "input"))
      (node (ref "U1") (pin "1") (pinfunction "EN_1") (pintype "input"))
      (node (ref "U1") (pin "2") (pinfunction "VIN_2") (pintype "input"))
      (node (ref "U2") (pin "2") (pinfunction "VIN_2") (pintype "input"))
      (node (ref "U3") (pin "2") (pinfunction "VIN_2") (pintype "input"))
      (node (ref "U4") (pin "2") (pinfunction "VIN_2") (pintype "input"))
    )
    (net (code "2") (name "1V0") (class "Default")
      (node (ref "C68") (pin "2") (pinfunction "2_2") (pintype "input"))
      (node (ref "C69") (pin "2") (pinfunction "2_2") (pintype "input"))
      (node (ref "C70") (pin "2") (pinfunction "2_2") (pintype "input"))
      (node (ref "C71") (pin "2") (pinfunction "2_2") (pintype "input"))
      (node (ref "C73") (pin "2") (pinfunction "2_2") (pintype "input"))
      (node (ref "L1") (pin "1") (pinfunction "IN_1") (pintype "input"))
      (node (ref "U7") (pin "G11") (pinfunction "VCCBRAM_G11") (pintype "input"))
      (node (ref "U7") (pin "G13") (pinfunction "VCCINT_G13") (pintype "input"))
      (node (ref "U7") (pin "G7") (pinfunction "VCCPINT_G7") (pintype "input"))
      (node (ref "U7") (pin "H10") (pinfunction "VCCBRAM_H10") (pintype "input"))
      (node (ref "U7") (pin "H12") (pinfunction "VCCINT_H12") (pintype "input"))
      (node (ref "U7") (pin "J13") (pinfunction "VCCINT_J13") (pintype "input"))
      (node (ref "U7") (pin "J7") (pinfunction "VCCPINT_J7") (pintype "input"))
      (node (ref "U7") (pin "K12") (pinfunction "VCCINT_K12") (pintype "input"))
      (node (ref "U7") (pin "L13") (pinfunction "VCCINT_L13") (pintype "input"))
      (node (ref "U7") (pin "L7") (pinfunction "VCCPINT_L7") (pintype "input"))
      (node (ref "U7") (pin "M12") (pinfunction "VCCINT_M12") (pintype "input"))
      (node (ref "U7") (pin "N13") (pinfunction "VCCINT_N13") (pintype "input"))
      (node (ref "U7") (pin "N7") (pinfunction "VCCPINT_N7") (pintype "input"))
      (node (ref "U7") (pin "P12") (pinfunction "VCCINT_P12") (pintype "input"))
      (node (ref "U7") (pin "P8") (pinfunction "VCCPINT_P8") (pintype "input"))
      (node (ref "U7") (pin "R13") (pinfunction "VCCINT_R13") (pintype "input"))
      (node (ref "U7") (pin "R7") (pinfunction "VCCPINT_R7") (pintype "input"))
    )
    (net (code "3") (name "1V5") (class "Default")
      (node (ref "C15") (pin "2") (pinfunction "2_2") (pintype "input"))
      (node (ref "C16") (pin "2") (pinfunction "2_2") (pintype "input"))
      (node (ref "C17") (pin "2") (pinfunction "2_2") (pintype "input"))
      (node (ref "C18") (pin "2") (pinfunction "2_2") (pintype "input"))
      (node (ref "C19") (pin "2") (pinfunction "2_2") (pintype "input"))
      (node (ref "C20") (pin "2") (pinfunction "2_2") (pintype "input"))
      (node (ref "C21") (pin "2") (pinfunction "2_2") (pintype "input"))
      (node (ref "C22") (pin "2") (pinfunction "2_2") (pintype "input"))
      (node (ref "C23") (pin "2") (pinfunction "2_2") (pintype "input"))
      (node (ref "C24") (pin "2") (pinfunction "2_2") (pintype "input"))
      (node (ref "C25") (pin "2") (pinfunction "2_2") (pintype "input"))
      (node (ref "C26") (pin "2") (pinfunction "2_2") (pintype "input"))
      (node (ref "C30") (pin "2") (pinfunction "2_2") (pintype "input"))
      (node (ref "C34") (pin "1") (pinfunction "1_1") (pintype "input"))
      (node (ref "C36") (pin "1") (pinfunction "1_1") (pintype "input"))
      (node (ref "C41") (pin "1") (pinfunction "1_1") (pintype "input"))
      (node (ref "C42") (pin "1") (pinfunction "1_1") (pintype "input"))
      (node (ref "L5") (pin "1") (pinfunction "IN_1") (pintype "input"))
      (node (ref "R20") (pin "1") (pinfunction "1_1") (pintype "input"))
      (node (ref "R23") (pin "1") (pinfunction "1_1") (pintype "input"))
      (node (ref "R25") (pin "1") (pinfunction "1_1") (pintype "input"))
      (node (ref "R6") (pin "1") (pinfunction "1_1") (pintype "input"))
      (node (ref "U5") (pin "A1") (pinfunction "VDDQ_A1") (pintype "input"))
      (node (ref "U5") (pin "A8") (pinfunction "VDDQ_A8") (pintype "input"))
      (node (ref "U5") (pin "B2") (pinfunction "VDD_B2") (pintype "input"))
      (node (ref "U5") (pin "C1") (pinfunction "VDDQ_C1") (pintype "input"))
      (node (ref "U5") (pin "C9") (pinfunction "VDDQ_C9") (pintype "input"))
      (node (ref "U5") (pin "D2") (pinfunction "VDDQ_D2") (pintype "input"))
      (node (ref "U5") (pin "D9") (pinfunction "VDD_D9") (pintype "input"))
      (node (ref "U5") (pin "E9") (pinfunction "VDDQ_E9") (pintype "input"))
      (node (ref "U5") (pin "F1") (pinfunction "VDDQ_F1") (pintype "input"))
      (node (ref "U5") (pin "G7") (pinfunction "VDD_G7") (pintype "input"))
      (node (ref "U5") (pin "H2") (pinfunction "VDDQ_H2") (pintype "input"))
      (node (ref "U5") (pin "H9") (pinfunction "VDDQ_H9") (pintype "input"))
      (node (ref "U5") (pin "K2") (pinfunction "VDD_K2") (pintype "input"))
      (node (ref "U5") (pin "K8") (pinfunction "VDD_K8") (pintype "input"))
      (node (ref "U5") (pin "N1") (pinfunction "VDD_N1") (pintype "input"))
      (node (ref "U5") (pin "N9") (pinfunction "VDD_N9") (pintype "input"))
      (node (ref "U5") (pin "R1") (pinfunction "VDD_R1") (pintype "input"))
      (node (ref "U5") (pin "R9") (pinfunction "VDD_R9") (pintype "input"))
      (node (ref "U7") (pin "A3") (pinfunction "VCCO_DDR_502_A3") (pintype "input"))
      (node (ref "U7") (pin "D2") (pinfunction "VCCO_DDR_502_D2") (pintype "input"))
      (node (ref "U7") (pin "E5") (pinfunction "VCCO_DDR_502_E5") (pintype "input"))
      (node (ref "U7") (pin "G1") (pinfunction "VCCO_DDR_502_G1") (pintype "input"))
      (node (ref "U7") (pin "H4") (pinfunction "VCCO_DDR_502_H4") (pintype "input"))
      (node (ref "U7") (pin "L3") (pinfunction "VCCO_DDR_502_L3") (pintype "input"))
      (node (ref "U7") (pin "P2") (pinfunction "VCCO_DDR_502_P2") (pintype "input"))
      (node (ref "U7") (pin "R5") (pinfunction "VCCO_DDR_502_R5") (pintype "input"))
      (node (ref "U7") (pin "U1") (pinfunction "VCCO_DDR_502_U1") (pintype "input"))
      (node (ref "U7") (pin "V4") (pinfunction "VCCO_DDR_502_V4") (pintype "input"))
    )
    (net (code "4") (name "1V8") (class "Default")
      (node (ref "C49") (pin "1") (pinfunction "1_1") (pintype "input"))
      (node (ref "C50") (pin "1") (pinfunction "1_1") (pintype "input"))
      (node (ref "C56") (pin "2") (pinfunction "2_2") (pintype "input"))
      (node (ref "C74") (pin "2") (pinfunction "2_2") (pintype "input"))
      (node (ref "C75") (pin "2") (pinfunction "2_2") (pintype "input"))
      (node (ref "C76") (pin "2") (pinfunction "2_2") (pintype "input"))
      (node (ref "L2") (pin "1") (pinfunction "IN_1") (pintype "input"))
      (node (ref "L3") (pin "2") (pinfunction "2_2") (pintype "input"))
      (node (ref "R34") (pin "2") (pinfunction "2_2") (pintype "input"))
      (node (ref "R38") (pin "1") (pinfunction "1_1") (pintype "input"))
      (node (ref "U7") (pin "A13") (pinfunction "VCCO_MIO1_501_A13") (pintype "input"))
      (node (ref "U7") (pin "B16") (pinfunction "VCCO_MIO1_501_B16") (pintype "input"))
      (node (ref "U7") (pin "D12") (pinfunction "VCCO_MIO1_501_D12") (pintype "input"))
      (node (ref "U7") (pin "E15") (pinfunction "VCCO_MIO1_501_E15") (pintype "input"))
      (node (ref "U7") (pin "F11") (pinfunction "VCCBATT_0_F11") (pintype "input"))
      (node (ref "U7") (pin "F8") (pinfunction "VCCPAUX_F8") (pintype "input"))
      (node (ref "U7") (pin "G9") (pinfunction "VCCPAUX_G9") (pintype "input"))
      (node (ref "U7") (pin "H8") (pinfunction "VCCPAUX_H8") (pintype "input"))
      (node (ref "U7") (pin "J11") (pinfunction "VCCAUX_J11") (pintype "input"))
      (node (ref "U7") (pin "J9") (pinfunction "VCCADC_0_J9") (pintype "input"))
      (node (ref "U7") (pin "K8") (pinfunction "VCCPAUX_K8") (pintype "input"))
      (node (ref "U7") (pin "L11") (pinfunction "VCCAUX_L11") (pintype "input"))
      (node (ref "U7") (pin "M8") (pinfunction "VCCPAUX_M8") (pintype "input"))
      (node (ref "U7") (pin "N11") (pinfunction "VCCAUX_N11") (pintype "input"))
      (node (ref "U7") (pin "N9") (pinfunction "VCCAUX_N9") (pintype "input"))
      (node (ref "U7") (pin "P10") (pinfunction "VCCAUX_P10") (pintype "input"))
      (node (ref "U7") (pin "R9") (pinfunction "VCCAUX_R9") (pintype "input"))
      (node (ref "U8") (pin "5") (pinfunction "VCCA_5") (pintype "input"))
      (node (ref "U9") (pin "1") (pinfunction "VIO_1") (pintype "unspecified"))
    )
    (net (code "5") (name "3V3") (class "Default")
      (node (ref "C46") (pin "1") (pinfunction "1_1") (pintype "input"))
      (node (ref "C47") (pin "2") (pinfunction "2_2") (pintype "input"))
      (node (ref "C51") (pin "1") (pinfunction "1_1") (pintype "input"))
      (node (ref "C53") (pin "1") (pinfunction "1_1") (pintype "input"))
      (node (ref "C58") (pin "2") (pinfunction "2_2") (pintype "input"))
      (node (ref "C59") (pin "2") (pinfunction "2_2") (pintype "input"))
      (node (ref "C60") (pin "2") (pinfunction "2_2") (pintype "input"))
      (node (ref "C61") (pin "2") (pinfunction "2_2") (pintype "input"))
      (node (ref "C62") (pin "2") (pinfunction "2_2") (pintype "input"))
      (node (ref "C63") (pin "2") (pinfunction "2_2") (pintype "input"))
      (node (ref "C64") (pin "2") (pinfunction "2_2") (pintype "input"))
      (node (ref "C65") (pin "2") (pinfunction "2_2") (pintype "input"))
      (node (ref "C66") (pin "2") (pinfunction "2_2") (pintype "input"))
      (node (ref "C67") (pin "2") (pinfunction "2_2") (pintype "input"))
      (node (ref "C81") (pin "1") (pinfunction "1_1") (pintype "input"))
      (node (ref "C82") (pin "2") (pinfunction "2_2") (pintype "input"))
      (node (ref "L4") (pin "1") (pinfunction "IN_1") (pintype "input"))
      (node (ref "L6") (pin "2") (pinfunction "2_2") (pintype "input"))
      (node (ref "L7") (pin "2") (pinfunction "2_2") (pintype "input"))
      (node (ref "R1") (pin "1") (pinfunction "1_1") (pintype "input"))
      (node (ref "R2") (pin "1") (pinfunction "1_1") (pintype "input"))
      (node (ref "R28") (pin "1") (pinfunction "1_1") (pintype "input"))
      (node (ref "R29") (pin "1") (pinfunction "1_1") (pintype "input"))
      (node (ref "R36") (pin "1") (pinfunction "1_1") (pintype "input"))
      (node (ref "R42") (pin "2") (pinfunction "2_2") (pintype "input"))
      (node (ref "R43") (pin "2") (pinfunction "2_2") (pintype "input"))
      (node (ref "R75") (pin "2") (pinfunction "2_2") (pintype "input"))
      (node (ref "R76") (pin "2") (pinfunction "2_2") (pintype "input"))
      (node (ref "R78") (pin "1") (pinfunction "1_1") (pintype "input"))
      (node (ref "U10") (pin "8") (pinfunction "VCC_8") (pintype "input"))
      (node (ref "U11") (pin "1") (pinfunction "VDD_1") (pintype "input"))
      (node (ref "U7") (pin "B6") (pinfunction "VCCO_MIO0_500_B6") (pintype "input"))
      (node (ref "U7") (pin "C19") (pinfunction "VCCO_35_C19") (pintype "input"))
      (node (ref "U7") (pin "D7") (pinfunction "VCCO_MIO0_500_D7") (pintype "input"))
      (node (ref "U7") (pin "F18") (pinfunction "VCCO_35_F18") (pintype "input"))
      (node (ref "U7") (pin "H14") (pinfunction "VCCO_35_H14") (pintype "input"))
      (node (ref "U7") (pin "J17") (pinfunction "VCCO_35_J17") (pintype "input"))
      (node (ref "U7") (pin "K20") (pinfunction "VCCO_35_K20") (pintype "input"))
      (node (ref "U7") (pin "K6") (pinfunction "VCCO_0_K6") (pintype "input"))
      (node (ref "U7") (pin "M16") (pinfunction "VCCO_35_M16") (pintype "input"))
      (node (ref "U7") (pin "M6") (pinfunction "CFGBVS_0_M6") (pintype "input"))
      (node (ref "U7") (pin "N19") (pinfunction "VCCO_34_N19") (pintype "input"))
      (node (ref "U7") (pin "N6") (pinfunction "RSVDVCC3_N6") (pintype "input"))
      (node (ref "U7") (pin "R15") (pinfunction "VCCO_34_R15") (pintype "input"))
      (node (ref "U7") (pin "R6") (pinfunction "RSVDVCC2_R6") (pintype "input"))
      (node (ref "U7") (pin "T18") (pinfunction "VCCO_34_T18") (pintype "input"))
      (node (ref "U7") (pin "T6") (pinfunction "RSVDVCC1_T6") (pintype "input"))
      (node (ref "U7") (pin "T8") (pinfunction "VCCO_13_T8") (pintype "input"))
      (node (ref "U7") (pin "U11") (pinfunction "VCCO_13_U11") (pintype "input"))
      (node (ref "U7") (pin "V14") (pinfunction "VCCO_34_V14") (pintype "input"))
      (node (ref "U7") (pin "W17") (pinfunction "VCCO_34_W17") (pintype "input"))
      (node (ref "U7") (pin "W7") (pinfunction "VCCO_13_W7") (pintype "input"))
      (node (ref "U7") (pin "Y10") (pinfunction "VCCO_13_Y10") (pintype "input"))
      (node (ref "U7") (pin "Y20") (pinfunction "VCCO_34_Y20") (pintype "input"))
      (node (ref "U8") (pin "17") (pinfunction "VCCB1_17") (pintype "input"))
      (node (ref "U8") (pin "21") (pinfunction "VCCB0_21") (pintype "input"))
    )
    (net (code "6") (name "AIO_0") (class "Default")
      (node (ref "U7") (pin "R19") (pinfunction "IO_0_34_R19") (pintype "input"))
    )
    (net (code "7") (name "AIO_1_N") (class "Default")
      (node (ref "CN1") (pin "14") (pinfunction "14_14") (pintype "input"))
      (node (ref "U7") (pin "T10") (pinfunction "IO_L1N_T0_34_T10") (pintype "input"))
    )
    (net (code "8") (name "AIO_1_P") (class "Default")
      (node (ref "CN1") (pin "12") (pinfunction "12_12") (pintype "input"))
      (node (ref "U7") (pin "T11") (pinfunction "IO_L1P_T0_34_T11") (pintype "input"))
    )
    (net (code "9") (name "AIO_2_N") (class "Default")
      (node (ref "CN1") (pin "18") (pinfunction "18_18") (pintype "input"))
      (node (ref "U7") (pin "U12") (pinfunction "IO_L2N_T0_34_U12") (pintype "input"))
    )
    (net (code "10") (name "AIO_2_P") (class "Default")
      (node (ref "CN1") (pin "16") (pinfunction "16_16") (pintype "input"))
      (node (ref "U7") (pin "T12") (pinfunction "IO_L2P_T0_34_T12") (pintype "input"))
    )
    (net (code "11") (name "AIO_3_N") (class "Default")
      (node (ref "CN1") (pin "24") (pinfunction "24_24") (pintype "input"))
      (node (ref "U7") (pin "V13") (pinfunction "IO_L3N_T0_DQS_34_V13") (pintype "input"))
    )
    (net (code "12") (name "AIO_3_P") (class "Default")
      (node (ref "CN1") (pin "22") (pinfunction "22_22") (pintype "input"))
      (node (ref "U7") (pin "U13") (pinfunction "IO_L3P_T0_DQS_PUDC_B_34_U13") (pintype "input"))
    )
    (net (code "13") (name "AIO_4_N") (class "Default")
      (node (ref "CN1") (pin "17") (pinfunction "17_17") (pintype "input"))
      (node (ref "U7") (pin "W13") (pinfunction "IO_L4N_T0_34_W13") (pintype "input"))
    )
    (net (code "14") (name "AIO_4_P") (class "Default")
      (node (ref "CN1") (pin "15") (pinfunction "15_15") (pintype "input"))
      (node (ref "U7") (pin "V12") (pinfunction "IO_L4P_T0_34_V12") (pintype "input"))
    )
    (net (code "15") (name "AIO_5_N") (class "Default")
      (node (ref "CN1") (pin "32") (pinfunction "32_32") (pintype "input"))
      (node (ref "U7") (pin "T15") (pinfunction "IO_L5N_T0_34_T15") (pintype "input"))
    )
    (net (code "16") (name "AIO_5_P") (class "Default")
      (node (ref "CN1") (pin "30") (pinfunction "30_30") (pintype "input"))
      (node (ref "U7") (pin "T14") (pinfunction "IO_L5P_T0_34_T14") (pintype "input"))
    )
    (net (code "17") (name "AIO_6_N") (class "Default")
      (node (ref "CN1") (pin "28") (pinfunction "28_28") (pintype "input"))
      (node (ref "U7") (pin "R14") (pinfunction "IO_L6N_T0_VREF_34_R14") (pintype "input"))
    )
    (net (code "18") (name "AIO_6_P") (class "Default")
      (node (ref "CN1") (pin "26") (pinfunction "26_26") (pintype "input"))
      (node (ref "U7") (pin "P14") (pinfunction "IO_L6P_T0_34_P14") (pintype "input"))
    )
    (net (code "19") (name "AIO_7_N") (class "Default")
      (node (ref "CN1") (pin "45") (pinfunction "45_45") (pintype "input"))
      (node (ref "U7") (pin "Y17") (pinfunction "IO_L7N_T1_34_Y17") (pintype "input"))
    )
    (net (code "20") (name "AIO_7_P") (class "Default")
      (node (ref "CN1") (pin "43") (pinfunction "43_43") (pintype "input"))
      (node (ref "U7") (pin "Y16") (pinfunction "IO_L7P_T1_34_Y16") (pintype "input"))
    )
    (net (code "21") (name "AIO_8_N") (class "Default")
      (node (ref "CN1") (pin "27") (pinfunction "27_27") (pintype "input"))
      (node (ref "U7") (pin "Y14") (pinfunction "IO_L8N_T1_34_Y14") (pintype "input"))
    )
    (net (code "22") (name "AIO_8_P") (class "Default")
      (node (ref "CN1") (pin "25") (pinfunction "25_25") (pintype "input"))
      (node (ref "U7") (pin "W14") (pinfunction "IO_L8P_T1_34_W14") (pintype "input"))
    )
    (net (code "23") (name "AIO_9_N") (class "Default")
      (node (ref "U7") (pin "U17") (pinfunction "IO_L9N_T1_DQS_34_U17") (pintype "input"))
    )
    (net (code "24") (name "AIO_9_P") (class "Default")
      (node (ref "U11") (pin "4") (pinfunction "DIN_4") (pintype "input"))
      (node (ref "U7") (pin "T16") (pinfunction "IO_L9P_T1_DQS_34_T16") (pintype "input"))
    )
    (net (code "25") (name "AIO_10_N") (class "Default")
      (node (ref "CN1") (pin "23") (pinfunction "23_23") (pintype "input"))
      (node (ref "U7") (pin "W15") (pinfunction "IO_L10N_T1_34_W15") (pintype "input"))
    )
    (net (code "26") (name "AIO_10_P") (class "Default")
      (node (ref "CN1") (pin "21") (pinfunction "21_21") (pintype "input"))
      (node (ref "U7") (pin "V15") (pinfunction "IO_L10P_T1_34_V15") (pintype "input"))
    )
    (net (code "27") (name "AIO_11_P") (class "Default")
      (node (ref "U7") (pin "U14") (pinfunction "IO_L11P_T1_SRCC_34_U14") (pintype "input"))
    )
    (net (code "28") (name "AIO_12_N") (class "Default")
      (node (ref "CN1") (pin "46") (pinfunction "46_46") (pintype "input"))
      (node (ref "U7") (pin "U19") (pinfunction "IO_L12N_T1_MRCC_34_U19") (pintype "input"))
    )
    (net (code "29") (name "AIO_12_P") (class "Default")
      (node (ref "CN1") (pin "44") (pinfunction "44_44") (pintype "input"))
      (node (ref "U7") (pin "U18") (pinfunction "IO_L12P_T1_MRCC_34_U18") (pintype "input"))
    )
    (net (code "30") (name "AIO_13_N") (class "Default")
      (node (ref "U7") (pin "P19") (pinfunction "IO_L13N_T2_MRCC_34_P19") (pintype "input"))
    )
    (net (code "31") (name "AIO_13_P") (class "Default")
      (node (ref "U7") (pin "N18") (pinfunction "IO_L13P_T2_MRCC_34_N18") (pintype "input"))
    )
    (net (code "32") (name "AIO_14_N") (class "Default")
      (node (ref "CN1") (pin "50") (pinfunction "50_50") (pintype "input"))
      (node (ref "U7") (pin "P20") (pinfunction "IO_L14N_T2_SRCC_34_P20") (pintype "input"))
    )
    (net (code "33") (name "AIO_14_P") (class "Default")
      (node (ref "CN1") (pin "48") (pinfunction "48_48") (pintype "input"))
      (node (ref "U7") (pin "N20") (pinfunction "IO_L14P_T2_SRCC_34_N20") (pintype "input"))
    )
    (net (code "34") (name "AIO_15_N") (class "Default")
      (node (ref "CN1") (pin "49") (pinfunction "49_49") (pintype "input"))
      (node (ref "U7") (pin "U20") (pinfunction "IO_L15N_T2_DQS_34_U20") (pintype "input"))
    )
    (net (code "35") (name "AIO_15_P") (class "Default")
      (node (ref "CN1") (pin "47") (pinfunction "47_47") (pintype "input"))
      (node (ref "U7") (pin "T20") (pinfunction "IO_L15P_T2_DQS_34_T20") (pintype "input"))
    )
    (net (code "36") (name "AIO_16_N") (class "Default")
      (node (ref "CN1") (pin "54") (pinfunction "54_54") (pintype "input"))
      (node (ref "U7") (pin "W20") (pinfunction "IO_L16N_T2_34_W20") (pintype "input"))
    )
    (net (code "37") (name "AIO_16_P") (class "Default")
      (node (ref "CN1") (pin "52") (pinfunction "52_52") (pintype "input"))
      (node (ref "U7") (pin "V20") (pinfunction "IO_L16P_T2_34_V20") (pintype "input"))
    )
    (net (code "38") (name "AIO_17_N") (class "Default")
      (node (ref "CN1") (pin "53") (pinfunction "53_53") (pintype "input"))
      (node (ref "U7") (pin "Y19") (pinfunction "IO_L17N_T2_34_Y19") (pintype "input"))
    )
    (net (code "39") (name "AIO_17_P") (class "Default")
      (node (ref "CN1") (pin "51") (pinfunction "51_51") (pintype "input"))
      (node (ref "U7") (pin "Y18") (pinfunction "IO_L17P_T2_34_Y18") (pintype "input"))
    )
    (net (code "40") (name "AIO_18_N") (class "Default")
      (node (ref "CN1") (pin "31") (pinfunction "31_31") (pintype "input"))
      (node (ref "U7") (pin "W16") (pinfunction "IO_L18N_T2_34_W16") (pintype "input"))
    )
    (net (code "41") (name "AIO_18_P") (class "Default")
      (node (ref "CN1") (pin "29") (pinfunction "29_29") (pintype "input"))
      (node (ref "U7") (pin "V16") (pinfunction "IO_L18P_T2_34_V16") (pintype "input"))
    )
    (net (code "42") (name "AIO_19_N") (class "Default")
      (node (ref "CN1") (pin "42") (pinfunction "42_42") (pintype "input"))
      (node (ref "U7") (pin "R17") (pinfunction "IO_L19N_T3_VREF_34_R17") (pintype "input"))
    )
    (net (code "43") (name "AIO_19_P") (class "Default")
      (node (ref "CN1") (pin "40") (pinfunction "40_40") (pintype "input"))
      (node (ref "U7") (pin "R16") (pinfunction "IO_L19P_T3_34_R16") (pintype "input"))
    )
    (net (code "44") (name "AIO_20_N") (class "Default")
      (node (ref "U7") (pin "R18") (pinfunction "IO_L20N_T3_34_R18") (pintype "input"))
    )
    (net (code "45") (name "AIO_20_P") (class "Default")
      (node (ref "U7") (pin "T17") (pinfunction "IO_L20P_T3_34_T17") (pintype "input"))
    )
    (net (code "46") (name "AIO_21_N") (class "Default")
      (node (ref "CN1") (pin "35") (pinfunction "35_35") (pintype "input"))
      (node (ref "U7") (pin "V18") (pinfunction "IO_L21N_T3_DQS_34_V18") (pintype "input"))
    )
    (net (code "47") (name "AIO_21_P") (class "Default")
      (node (ref "CN1") (pin "33") (pinfunction "33_33") (pintype "input"))
      (node (ref "U7") (pin "V17") (pinfunction "IO_L21P_T3_DQS_34_V17") (pintype "input"))
    )
    (net (code "48") (name "AIO_22_N") (class "Default")
      (node (ref "CN1") (pin "41") (pinfunction "41_41") (pintype "input"))
      (node (ref "U7") (pin "W19") (pinfunction "IO_L22N_T3_34_W19") (pintype "input"))
    )
    (net (code "49") (name "AIO_22_P") (class "Default")
      (node (ref "CN1") (pin "39") (pinfunction "39_39") (pintype "input"))
      (node (ref "U7") (pin "W18") (pinfunction "IO_L22P_T3_34_W18") (pintype "input"))
    )
    (net (code "50") (name "AIO_23_N") (class "Default")
      (node (ref "U7") (pin "P18") (pinfunction "IO_L23N_T3_34_P18") (pintype "input"))
    )
    (net (code "51") (name "AIO_23_P") (class "Default")
      (node (ref "U7") (pin "N17") (pinfunction "IO_L23P_T3_34_N17") (pintype "input"))
    )
    (net (code "52") (name "AIO_24_N") (class "Default")
      (node (ref "CN1") (pin "36") (pinfunction "36_36") (pintype "input"))
      (node (ref "U7") (pin "P16") (pinfunction "IO_L24N_T3_34_P16") (pintype "input"))
    )
    (net (code "53") (name "AIO_24_P") (class "Default")
      (node (ref "CN1") (pin "34") (pinfunction "34_34") (pintype "input"))
      (node (ref "U7") (pin "P15") (pinfunction "IO_L24P_T3_34_P15") (pintype "input"))
    )
    (net (code "54") (name "AIO_25") (class "Default")
      (node (ref "U7") (pin "T19") (pinfunction "IO_25_34_T19") (pintype "input"))
    )
    (net (code "55") (name "BIO_0") (class "Default")
      (node (ref "U7") (pin "G14") (pinfunction "IO_0_35_G14") (pintype "input"))
    )
    (net (code "56") (name "BIO_1_N") (class "Default")
      (node (ref "CN2") (pin "50") (pinfunction "50_50") (pintype "input"))
      (node (ref "U7") (pin "B20") (pinfunction "IO_L1N_T0_AD0N_35_B20") (pintype "input"))
    )
    (net (code "57") (name "BIO_1_P") (class "Default")
      (node (ref "CN2") (pin "48") (pinfunction "48_48") (pintype "input"))
      (node (ref "U7") (pin "C20") (pinfunction "IO_L1P_T0_AD0P_35_C20") (pintype "input"))
    )
    (net (code "58") (name "BIO_2_N") (class "Default")
      (node (ref "CN2") (pin "45") (pinfunction "45_45") (pintype "input"))
      (node (ref "U7") (pin "A20") (pinfunction "IO_L2N_T0_AD8N_35_A20") (pintype "input"))
    )
    (net (code "59") (name "BIO_2_P") (class "Default")
      (node (ref "CN2") (pin "43") (pinfunction "43_43") (pintype "input"))
      (node (ref "U7") (pin "B19") (pinfunction "IO_L2P_T0_AD8P_35_B19") (pintype "input"))
    )
    (net (code "60") (name "BIO_3_N") (class "Default")
      (node (ref "CN2") (pin "41") (pinfunction "41_41") (pintype "input"))
      (node (ref "U7") (pin "D18") (pinfunction "IO_L3N_T0_DQS_AD1N_35_D18") (pintype "input"))
    )
    (net (code "61") (name "BIO_3_P") (class "Default")
      (node (ref "CN2") (pin "39") (pinfunction "39_39") (pintype "input"))
      (node (ref "U7") (pin "E17") (pinfunction "IO_L3P_T0_DQS_AD1P_35_E17") (pintype "input"))
    )
    (net (code "62") (name "BIO_4_N") (class "Default")
      (node (ref "CN2") (pin "42") (pinfunction "42_42") (pintype "input"))
      (node (ref "U7") (pin "D20") (pinfunction "IO_L4N_T0_35_D20") (pintype "input"))
    )
    (net (code "63") (name "BIO_4_P") (class "Default")
      (node (ref "CN2") (pin "40") (pinfunction "40_40") (pintype "input"))
      (node (ref "U7") (pin "D19") (pinfunction "IO_L4P_T0_35_D19") (pintype "input"))
    )
    (net (code "64") (name "BIO_5_N") (class "Default")
      (node (ref "CN2") (pin "32") (pinfunction "32_32") (pintype "input"))
      (node (ref "U7") (pin "E19") (pinfunction "IO_L5N_T0_AD9N_35_E19") (pintype "input"))
    )
    (net (code "65") (name "BIO_5_P") (class "Default")
      (node (ref "CN2") (pin "30") (pinfunction "30_30") (pintype "input"))
      (node (ref "U7") (pin "E18") (pinfunction "IO_L5P_T0_AD9P_35_E18") (pintype "input"))
    )
    (net (code "66") (name "BIO_6_N") (class "Default")
      (node (ref "U7") (pin "F17") (pinfunction "IO_L6N_T0_VREF_35_F17") (pintype "input"))
    )
    (net (code "67") (name "BIO_6_P") (class "Default")
      (node (ref "U7") (pin "F16") (pinfunction "IO_L6P_T0_35_F16") (pintype "input"))
    )
    (net (code "68") (name "BIO_7_N") (class "Default")
      (node (ref "U7") (pin "M20") (pinfunction "IO_L7N_T1_AD2N_35_M20") (pintype "input"))
    )
    (net (code "69") (name "BIO_7_P") (class "Default")
      (node (ref "U7") (pin "M19") (pinfunction "IO_L7P_T1_AD2P_35_M19") (pintype "input"))
    )
    (net (code "70") (name "BIO_8_N") (class "Default")
      (node (ref "U7") (pin "M18") (pinfunction "IO_L8N_T1_AD10N_35_M18") (pintype "input"))
    )
    (net (code "71") (name "BIO_8_P") (class "Default")
      (node (ref "U7") (pin "M17") (pinfunction "IO_L8P_T1_AD10P_35_M17") (pintype "input"))
    )
    (net (code "72") (name "BIO_9_N") (class "Default")
      (node (ref "U7") (pin "L20") (pinfunction "IO_L9N_T1_DQS_AD3N_35_L20") (pintype "input"))
    )
    (net (code "73") (name "BIO_9_P") (class "Default")
      (node (ref "U7") (pin "L19") (pinfunction "IO_L9P_T1_DQS_AD3P_35_L19") (pintype "input"))
    )
    (net (code "74") (name "BIO_10_N") (class "Default")
      (node (ref "U7") (pin "J19") (pinfunction "IO_L10N_T1_AD11N_35_J19") (pintype "input"))
    )
    (net (code "75") (name "BIO_10_P") (class "Default")
      (node (ref "U7") (pin "K19") (pinfunction "IO_L10P_T1_AD11P_35_K19") (pintype "input"))
    )
    (net (code "76") (name "BIO_11_N") (class "Default")
      (node (ref "U7") (pin "L17") (pinfunction "IO_L11N_T1_SRCC_35_L17") (pintype "input"))
    )
    (net (code "77") (name "BIO_11_P") (class "Default")
      (node (ref "U7") (pin "L16") (pinfunction "IO_L11P_T1_SRCC_35_L16") (pintype "input"))
    )
    (net (code "78") (name "BIO_12_N") (class "Default")
      (node (ref "CN2") (pin "31") (pinfunction "31_31") (pintype "input"))
      (node (ref "U7") (pin "K18") (pinfunction "IO_L12N_T1_MRCC_35_K18") (pintype "input"))
    )
    (net (code "79") (name "BIO_12_P") (class "Default")
      (node (ref "CN2") (pin "29") (pinfunction "29_29") (pintype "input"))
      (node (ref "U7") (pin "K17") (pinfunction "IO_L12P_T1_MRCC_35_K17") (pintype "input"))
    )
    (net (code "80") (name "BIO_13_N") (class "Default")
      (node (ref "CN2") (pin "36") (pinfunction "36_36") (pintype "input"))
      (node (ref "U7") (pin "H17") (pinfunction "IO_L13N_T2_MRCC_35_H17") (pintype "input"))
    )
    (net (code "81") (name "BIO_13_P") (class "Default")
      (node (ref "CN2") (pin "34") (pinfunction "34_34") (pintype "input"))
      (node (ref "U7") (pin "H16") (pinfunction "IO_L13P_T2_MRCC_35_H16") (pintype "input"))
    )
    (net (code "82") (name "BIO_14_N") (class "Default")
      (node (ref "CN2") (pin "49") (pinfunction "49_49") (pintype "input"))
      (node (ref "U7") (pin "H18") (pinfunction "IO_L14N_T2_AD4N_SRCC_35_H18") (pintype "input"))
    )
    (net (code "83") (name "BIO_14_P") (class "Default")
      (node (ref "CN2") (pin "47") (pinfunction "47_47") (pintype "input"))
      (node (ref "U7") (pin "J18") (pinfunction "IO_L14P_T2_AD4P_SRCC_35_J18") (pintype "input"))
    )
    (net (code "84") (name "BIO_15_N") (class "Default")
      (node (ref "CN2") (pin "46") (pinfunction "46_46") (pintype "input"))
      (node (ref "U7") (pin "F20") (pinfunction "IO_L15N_T2_DQS_AD12N_35_F20") (pintype "input"))
    )
    (net (code "85") (name "BIO_15_P") (class "Default")
      (node (ref "CN2") (pin "44") (pinfunction "44_44") (pintype "input"))
      (node (ref "U7") (pin "F19") (pinfunction "IO_L15P_T2_DQS_AD12P_35_F19") (pintype "input"))
    )
    (net (code "86") (name "BIO_16_N") (class "Default")
      (node (ref "U7") (pin "G18") (pinfunction "IO_L16N_T2_35_G18") (pintype "input"))
    )
    (net (code "87") (name "BIO_16_P") (class "Default")
      (node (ref "U7") (pin "G17") (pinfunction "IO_L16P_T2_35_G17") (pintype "input"))
    )
    (net (code "88") (name "BIO_17_N") (class "Default")
      (node (ref "CN2") (pin "53") (pinfunction "53_53") (pintype "input"))
      (node (ref "U7") (pin "H20") (pinfunction "IO_L17N_T2_AD5N_35_H20") (pintype "input"))
    )
    (net (code "89") (name "BIO_17_P") (class "Default")
      (node (ref "CN2") (pin "51") (pinfunction "51_51") (pintype "input"))
      (node (ref "U7") (pin "J20") (pinfunction "IO_L17P_T2_AD5P_35_J20") (pintype "input"))
    )
    (net (code "90") (name "BIO_18_N") (class "Default")
      (node (ref "CN2") (pin "54") (pinfunction "54_54") (pintype "input"))
      (node (ref "U7") (pin "G20") (pinfunction "IO_L18N_T2_AD13N_35_G20") (pintype "input"))
    )
    (net (code "91") (name "BIO_18_P") (class "Default")
      (node (ref "CN2") (pin "52") (pinfunction "52_52") (pintype "input"))
      (node (ref "U7") (pin "G19") (pinfunction "IO_L18P_T2_AD13P_35_G19") (pintype "input"))
    )
    (net (code "92") (name "BIO_19_N") (class "Default")
      (node (ref "CN2") (pin "35") (pinfunction "35_35") (pintype "input"))
      (node (ref "U7") (pin "G15") (pinfunction "IO_L19N_T3_VREF_35_G15") (pintype "input"))
    )
    (net (code "93") (name "BIO_19_P") (class "Default")
      (node (ref "CN2") (pin "33") (pinfunction "33_33") (pintype "input"))
      (node (ref "U7") (pin "H15") (pinfunction "IO_L19P_T3_35_H15") (pintype "input"))
    )
    (net (code "94") (name "BIO_20_N") (class "Default")
      (node (ref "CN2") (pin "27") (pinfunction "27_27") (pintype "input"))
      (node (ref "U7") (pin "J14") (pinfunction "IO_L20N_T3_AD6N_35_J14") (pintype "input"))
    )
    (net (code "95") (name "BIO_20_P") (class "Default")
      (node (ref "CN2") (pin "25") (pinfunction "25_25") (pintype "input"))
      (node (ref "U7") (pin "K14") (pinfunction "IO_L20P_T3_AD6P_35_K14") (pintype "input"))
    )
    (net (code "96") (name "BIO_21_N") (class "Default")
      (node (ref "U7") (pin "N16") (pinfunction "IO_L21N_T3_DQS_AD14N_35_N16") (pintype "input"))
    )
    (net (code "97") (name "BIO_21_P") (class "Default")
      (node (ref "U7") (pin "N15") (pinfunction "IO_L21P_T3_DQS_AD14P_35_N15") (pintype "input"))
    )
    (net (code "98") (name "BIO_22_N") (class "Default")
      (node (ref "U7") (pin "L15") (pinfunction "IO_L22N_T3_AD7N_35_L15") (pintype "input"))
    )
    (net (code "99") (name "BIO_22_P") (class "Default")
      (node (ref "R82") (pin "2") (pinfunction "2_2") (pintype "input"))
      (node (ref "U7") (pin "L14") (pinfunction "IO_L22P_T3_AD7P_35_L14") (pintype "input"))
    )
    (net (code "100") (name "BIO_23_N") (class "Default")
      (node (ref "U7") (pin "M15") (pinfunction "IO_L23N_T3_35_M15") (pintype "input"))
    )
    (net (code "101") (name "BIO_23_P") (class "Default")
      (node (ref "U7") (pin "M14") (pinfunction "IO_L23P_T3_35_M14") (pintype "input"))
    )
    (net (code "102") (name "BIO_24_N") (class "Default")
      (node (ref "CN2") (pin "23") (pinfunction "23_23") (pintype "input"))
      (node (ref "U7") (pin "J16") (pinfunction "IO_L24N_T3_AD15N_35_J16") (pintype "input"))
    )
    (net (code "103") (name "BIO_24_P") (class "Default")
      (node (ref "CN2") (pin "21") (pinfunction "21_21") (pintype "input"))
      (node (ref "U7") (pin "K16") (pinfunction "IO_L24P_T3_AD15P_35_K16") (pintype "input"))
    )
    (net (code "104") (name "BIO_25") (class "Default")
      (node (ref "U7") (pin "J15") (pinfunction "IO_25_35_J15") (pintype "input"))
    )
    (net (code "105") (name "CC1") (class "Default")
      (node (ref "R80") (pin "2") (pinfunction "2_2") (pintype "input"))
      (node (ref "USB1") (pin "A5") (pinfunction "CC1_A5") (pintype "input"))
    )
    (net (code "106") (name "CC2") (class "Default")
      (node (ref "R79") (pin "2") (pinfunction "2_2") (pintype "input"))
      (node (ref "USB1") (pin "B5") (pinfunction "CC2_B5") (pintype "input"))
    )
    (net (code "107") (name "DDRVTT") (class "Default")
      (node (ref "C31") (pin "2") (pinfunction "2_2") (pintype "input"))
      (node (ref "C32") (pin "2") (pinfunction "2_2") (pintype "input"))
      (node (ref "C33") (pin "2") (pinfunction "2_2") (pintype "input"))
      (node (ref "C34") (pin "2") (pinfunction "2_2") (pintype "input"))
      (node (ref "C35") (pin "1") (pinfunction "1_1") (pintype "input"))
      (node (ref "C38") (pin "1") (pinfunction "1_1") (pintype "input"))
      (node (ref "C39") (pin "1") (pinfunction "1_1") (pintype "input"))
      (node (ref "C40") (pin "1") (pinfunction "1_1") (pintype "input"))
      (node (ref "R23") (pin "2") (pinfunction "2_2") (pintype "input"))
      (node (ref "R24") (pin "1") (pinfunction "1_1") (pintype "input"))
      (node (ref "RN1") (pin "5") (pinfunction "5_5") (pintype "input"))
      (node (ref "RN1") (pin "6") (pinfunction "6_6") (pintype "input"))
      (node (ref "RN1") (pin "7") (pinfunction "7_7") (pintype "input"))
      (node (ref "RN1") (pin "8") (pinfunction "8_8") (pintype "input"))
      (node (ref "RN2") (pin "5") (pinfunction "5_5") (pintype "input"))
      (node (ref "RN2") (pin "6") (pinfunction "6_6") (pintype "input"))
      (node (ref "RN2") (pin "7") (pinfunction "7_7") (pintype "input"))
      (node (ref "RN2") (pin "8") (pinfunction "8_8") (pintype "input"))
      (node (ref "RN3") (pin "5") (pinfunction "5_5") (pintype "input"))
      (node (ref "RN3") (pin "6") (pinfunction "6_6") (pintype "input"))
      (node (ref "RN3") (pin "7") (pinfunction "7_7") (pintype "input"))
      (node (ref "RN3") (pin "8") (pinfunction "8_8") (pintype "input"))
      (node (ref "RN4") (pin "5") (pinfunction "5_5") (pintype "input"))
      (node (ref "RN4") (pin "6") (pinfunction "6_6") (pintype "input"))
      (node (ref "RN4") (pin "7") (pinfunction "7_7") (pintype "input"))
      (node (ref "RN4") (pin "8") (pinfunction "8_8") (pintype "input"))
      (node (ref "RN5") (pin "5") (pinfunction "5_5") (pintype "input"))
      (node (ref "RN5") (pin "6") (pinfunction "6_6") (pintype "input"))
      (node (ref "RN5") (pin "7") (pinfunction "7_7") (pintype "input"))
      (node (ref "RN5") (pin "8") (pinfunction "8_8") (pintype "input"))
      (node (ref "RN6") (pin "5") (pinfunction "5_5") (pintype "input"))
      (node (ref "RN6") (pin "6") (pinfunction "6_6") (pintype "input"))
      (node (ref "RN6") (pin "7") (pinfunction "7_7") (pintype "input"))
      (node (ref "RN6") (pin "8") (pinfunction "8_8") (pintype "input"))
    )
    (net (code "108") (name "DDR_A0") (class "Default")
      (node (ref "RN4") (pin "2") (pinfunction "2_2") (pintype "input"))
      (node (ref "U5") (pin "N3") (pinfunction "A0_N3") (pintype "input"))
      (node (ref "U7") (pin "N2") (pinfunction "PS_DDR_A0_502_N2") (pintype "input"))
    )
    (net (code "109") (name "DDR_A1") (class "Default")
      (node (ref "RN2") (pin "1") (pinfunction "1_1") (pintype "input"))
      (node (ref "U5") (pin "P7") (pinfunction "A1_P7") (pintype "input"))
      (node (ref "U7") (pin "K2") (pinfunction "PS_DDR_A1_502_K2") (pintype "input"))
    )
    (net (code "110") (name "DDR_A2") (class "Default")
      (node (ref "RN5") (pin "2") (pinfunction "2_2") (pintype "input"))
      (node (ref "U5") (pin "P3") (pinfunction "A2_P3") (pintype "input"))
      (node (ref "U7") (pin "M3") (pinfunction "PS_DDR_A2_502_M3") (pintype "input"))
    )
    (net (code "111") (name "DDR_A3") (class "Default")
      (node (ref "RN6") (pin "4") (pinfunction "4_4") (pintype "input"))
      (node (ref "U5") (pin "N2") (pinfunction "A3_N2") (pintype "input"))
      (node (ref "U7") (pin "K3") (pinfunction "PS_DDR_A3_502_K3") (pintype "input"))
    )
    (net (code "112") (name "DDR_A4") (class "Default")
      (node (ref "RN1") (pin "2") (pinfunction "2_2") (pintype "input"))
      (node (ref "U5") (pin "P8") (pinfunction "A4_P8") (pintype "input"))
      (node (ref "U7") (pin "M4") (pinfunction "PS_DDR_A4_502_M4") (pintype "input"))
    )
    (net (code "113") (name "DDR_A5") (class "Default")
      (node (ref "RN5") (pin "1") (pinfunction "1_1") (pintype "input"))
      (node (ref "U5") (pin "P2") (pinfunction "A5_P2") (pintype "input"))
      (node (ref "U7") (pin "L1") (pinfunction "PS_DDR_A5_502_L1") (pintype "input"))
    )
    (net (code "114") (name "DDR_A6") (class "Default")
      (node (ref "RN1") (pin "1") (pinfunction "1_1") (pintype "input"))
      (node (ref "U5") (pin "R8") (pinfunction "A6_R8") (pintype "input"))
      (node (ref "U7") (pin "L4") (pinfunction "PS_DDR_A6_502_L4") (pintype "input"))
    )
    (net (code "115") (name "DDR_A7") (class "Default")
      (node (ref "RN5") (pin "3") (pinfunction "3_3") (pintype "input"))
      (node (ref "U5") (pin "R2") (pinfunction "A7_R2") (pintype "input"))
      (node (ref "U7") (pin "K4") (pinfunction "PS_DDR_A7_502_K4") (pintype "input"))
    )
    (net (code "116") (name "DDR_A8") (class "Default")
      (node (ref "RN2") (pin "4") (pinfunction "4_4") (pintype "input"))
      (node (ref "U5") (pin "T8") (pinfunction "A8_T8") (pintype "input"))
      (node (ref "U7") (pin "K1") (pinfunction "PS_DDR_A8_502_K1") (pintype "input"))
    )
    (net (code "117") (name "DDR_A9") (class "Default")
      (node (ref "RN5") (pin "4") (pinfunction "4_4") (pintype "input"))
      (node (ref "U5") (pin "R3") (pinfunction "A9_R3") (pintype "input"))
      (node (ref "U7") (pin "J4") (pinfunction "PS_DDR_A9_502_J4") (pintype "input"))
    )
    (net (code "118") (name "DDR_A10") (class "Default")
      (node (ref "RN3") (pin "3") (pinfunction "3_3") (pintype "input"))
      (node (ref "U5") (pin "L7") (pinfunction "A10/AP_L7") (pintype "input"))
      (node (ref "U7") (pin "F5") (pinfunction "PS_DDR_A10_502_F5") (pintype "input"))
    )
    (net (code "119") (name "DDR_A11") (class "Default")
      (node (ref "RN2") (pin "3") (pinfunction "3_3") (pintype "input"))
      (node (ref "U5") (pin "R7") (pinfunction "A11_R7") (pintype "input"))
      (node (ref "U7") (pin "G4") (pinfunction "PS_DDR_A11_502_G4") (pintype "input"))
    )
    (net (code "120") (name "DDR_A12") (class "Default")
      (node (ref "RN3") (pin "4") (pinfunction "4_4") (pintype "input"))
      (node (ref "U5") (pin "N7") (pinfunction "A12/BC#_N7") (pintype "input"))
      (node (ref "U7") (pin "E4") (pinfunction "PS_DDR_A12_502_E4") (pintype "input"))
    )
    (net (code "121") (name "DDR_A13") (class "Default")
      (node (ref "RN4") (pin "1") (pinfunction "1_1") (pintype "input"))
      (node (ref "U5") (pin "T3") (pinfunction "A13_T3") (pintype "input"))
      (node (ref "U7") (pin "D4") (pinfunction "PS_DDR_A13_502_D4") (pintype "input"))
    )
    (net (code "122") (name "DDR_A14") (class "Default")
      (node (ref "RN2") (pin "2") (pinfunction "2_2") (pintype "input"))
      (node (ref "U5") (pin "T7") (pinfunction "A14_T7") (pintype "input"))
      (node (ref "U7") (pin "F4") (pinfunction "PS_DDR_A14_502_F4") (pintype "input"))
    )
    (net (code "123") (name "DDR_BA0") (class "Default")
      (node (ref "RN6") (pin "3") (pinfunction "3_3") (pintype "input"))
      (node (ref "U5") (pin "M2") (pinfunction "BA0_M2") (pintype "input"))
      (node (ref "U7") (pin "L5") (pinfunction "PS_DDR_BA0_502_L5") (pintype "input"))
    )
    (net (code "124") (name "DDR_BA1") (class "Default")
      (node (ref "RN1") (pin "3") (pinfunction "3_3") (pintype "input"))
      (node (ref "U5") (pin "N8") (pinfunction "BA1_N8") (pintype "input"))
      (node (ref "U7") (pin "R4") (pinfunction "PS_DDR_BA1_502_R4") (pintype "input"))
    )
    (net (code "125") (name "DDR_BA2") (class "Default")
      (node (ref "RN4") (pin "3") (pinfunction "3_3") (pintype "input"))
      (node (ref "U5") (pin "M3") (pinfunction "BA2_M3") (pintype "input"))
      (node (ref "U7") (pin "J5") (pinfunction "PS_DDR_BA2_502_J5") (pintype "input"))
    )
    (net (code "126") (name "DDR_CAS") (class "Default")
      (node (ref "RN3") (pin "1") (pinfunction "1_1") (pintype "input"))
      (node (ref "U5") (pin "K3") (pinfunction "CAS#_K3") (pintype "input"))
      (node (ref "U7") (pin "P5") (pinfunction "PS_DDR_CAS_B_502_P5") (pintype "input"))
    )
    (net (code "127") (name "DDR_CKE") (class "Default")
      (node (ref "RN1") (pin "4") (pinfunction "4_4") (pintype "input"))
      (node (ref "U5") (pin "K9") (pinfunction "CKE_K9") (pintype "input"))
      (node (ref "U7") (pin "N3") (pinfunction "PS_DDR_CKE_502_N3") (pintype "input"))
    )
    (net (code "128") (name "DDR_CLK_N") (class "Default")
      (node (ref "R22") (pin "2") (pinfunction "2_2") (pintype "input"))
      (node (ref "U5") (pin "K7") (pinfunction "CK#_K7") (pintype "input"))
      (node (ref "U7") (pin "M2") (pinfunction "PS_DDR_CKN_502_M2") (pintype "input"))
    )
    (net (code "129") (name "DDR_CLK_P") (class "Default")
      (node (ref "R22") (pin "1") (pinfunction "1_1") (pintype "input"))
      (node (ref "U5") (pin "J7") (pinfunction "CK_J7") (pintype "input"))
      (node (ref "U7") (pin "L2") (pinfunction "PS_DDR_CKP_502_L2") (pintype "input"))
    )
    (net (code "130") (name "DDR_CS") (class "Default")
      (node (ref "RN6") (pin "2") (pinfunction "2_2") (pintype "input"))
      (node (ref "U5") (pin "L2") (pinfunction "CS#_L2") (pintype "input"))
      (node (ref "U7") (pin "N1") (pinfunction "PS_DDR_CS_B_502_N1") (pintype "input"))
    )
    (net (code "131") (name "DDR_D0") (class "Default")
      (node (ref "U5") (pin "E3") (pinfunction "DQ0_E3") (pintype "input"))
      (node (ref "U7") (pin "C3") (pinfunction "PS_DDR_DQ0_502_C3") (pintype "input"))
    )
    (net (code "132") (name "DDR_D1") (class "Default")
      (node (ref "U5") (pin "F7") (pinfunction "DQ1_F7") (pintype "input"))
      (node (ref "U7") (pin "B3") (pinfunction "PS_DDR_DQ1_502_B3") (pintype "input"))
    )
    (net (code "133") (name "DDR_D2") (class "Default")
      (node (ref "U5") (pin "F2") (pinfunction "DQ2_F2") (pintype "input"))
      (node (ref "U7") (pin "A2") (pinfunction "PS_DDR_DQ2_502_A2") (pintype "input"))
    )
    (net (code "134") (name "DDR_D3") (class "Default")
      (node (ref "U5") (pin "F8") (pinfunction "DQ3_F8") (pintype "input"))
      (node (ref "U7") (pin "A4") (pinfunction "PS_DDR_DQ3_502_A4") (pintype "input"))
    )
    (net (code "135") (name "DDR_D4") (class "Default")
      (node (ref "U5") (pin "H3") (pinfunction "DQ4_H3") (pintype "input"))
      (node (ref "U7") (pin "D3") (pinfunction "PS_DDR_DQ4_502_D3") (pintype "input"))
    )
    (net (code "136") (name "DDR_D5") (class "Default")
      (node (ref "U5") (pin "H8") (pinfunction "DQ5_H8") (pintype "input"))
      (node (ref "U7") (pin "D1") (pinfunction "PS_DDR_DQ5_502_D1") (pintype "input"))
    )
    (net (code "137") (name "DDR_D6") (class "Default")
      (node (ref "U5") (pin "G2") (pinfunction "DQ6_G2") (pintype "input"))
      (node (ref "U7") (pin "C1") (pinfunction "PS_DDR_DQ6_502_C1") (pintype "input"))
    )
    (net (code "138") (name "DDR_D7") (class "Default")
      (node (ref "U5") (pin "H7") (pinfunction "DQ7_H7") (pintype "input"))
      (node (ref "U7") (pin "E1") (pinfunction "PS_DDR_DQ7_502_E1") (pintype "input"))
    )
    (net (code "139") (name "DDR_D8") (class "Default")
      (node (ref "U5") (pin "D7") (pinfunction "DQ8_D7") (pintype "input"))
      (node (ref "U7") (pin "E2") (pinfunction "PS_DDR_DQ8_502_E2") (pintype "input"))
    )
    (net (code "140") (name "DDR_D9") (class "Default")
      (node (ref "U5") (pin "C3") (pinfunction "DQ9_C3") (pintype "input"))
      (node (ref "U7") (pin "E3") (pinfunction "PS_DDR_DQ9_502_E3") (pintype "input"))
    )
    (net (code "141") (name "DDR_D10") (class "Default")
      (node (ref "U5") (pin "C8") (pinfunction "DQ10_C8") (pintype "input"))
      (node (ref "U7") (pin "G3") (pinfunction "PS_DDR_DQ10_502_G3") (pintype "input"))
    )
    (net (code "142") (name "DDR_D11") (class "Default")
      (node (ref "U5") (pin "C2") (pinfunction "DQ11_C2") (pintype "input"))
      (node (ref "U7") (pin "H3") (pinfunction "PS_DDR_DQ11_502_H3") (pintype "input"))
    )
    (net (code "143") (name "DDR_D12") (class "Default")
      (node (ref "U5") (pin "A7") (pinfunction "DQ12_A7") (pintype "input"))
      (node (ref "U7") (pin "J3") (pinfunction "PS_DDR_DQ12_502_J3") (pintype "input"))
    )
    (net (code "144") (name "DDR_D13") (class "Default")
      (node (ref "U5") (pin "A2") (pinfunction "DQ13_A2") (pintype "input"))
      (node (ref "U7") (pin "H2") (pinfunction "PS_DDR_DQ13_502_H2") (pintype "input"))
    )
    (net (code "145") (name "DDR_D14") (class "Default")
      (node (ref "U5") (pin "B8") (pinfunction "DQ14_B8") (pintype "input"))
      (node (ref "U7") (pin "H1") (pinfunction "PS_DDR_DQ14_502_H1") (pintype "input"))
    )
    (net (code "146") (name "DDR_D15") (class "Default")
      (node (ref "U5") (pin "A3") (pinfunction "DQ15_A3") (pintype "input"))
      (node (ref "U7") (pin "J1") (pinfunction "PS_DDR_DQ15_502_J1") (pintype "input"))
    )
    (net (code "147") (name "DDR_DM0") (class "Default")
      (node (ref "U5") (pin "E7") (pinfunction "LDM_E7") (pintype "input"))
      (node (ref "U7") (pin "A1") (pinfunction "PS_DDR_DM0_502_A1") (pintype "input"))
    )
    (net (code "148") (name "DDR_DM1") (class "Default")
      (node (ref "U5") (pin "D3") (pinfunction "UDM_D3") (pintype "input"))
      (node (ref "U7") (pin "F1") (pinfunction "PS_DDR_DM1_502_F1") (pintype "input"))
    )
    (net (code "149") (name "DDR_DQS0_N") (class "Default")
      (node (ref "U5") (pin "G3") (pinfunction "LDQS#_G3") (pintype "input"))
      (node (ref "U7") (pin "B2") (pinfunction "PS_DDR_DQS_N0_502_B2") (pintype "input"))
    )
    (net (code "150") (name "DDR_DQS0_P") (class "Default")
      (node (ref "U5") (pin "F3") (pinfunction "LDQS_F3") (pintype "input"))
      (node (ref "U7") (pin "C2") (pinfunction "PS_DDR_DQS_P0_502_C2") (pintype "input"))
    )
    (net (code "151") (name "DDR_DQS1_N") (class "Default")
      (node (ref "U5") (pin "B7") (pinfunction "UDQS#_B7") (pintype "input"))
      (node (ref "U7") (pin "F2") (pinfunction "PS_DDR_DQS_N1_502_F2") (pintype "input"))
    )
    (net (code "152") (name "DDR_DQS1_P") (class "Default")
      (node (ref "U5") (pin "C7") (pinfunction "UDQS_C7") (pintype "input"))
      (node (ref "U7") (pin "G2") (pinfunction "PS_DDR_DQS_P1_502_G2") (pintype "input"))
    )
    (net (code "153") (name "DDR_ODT") (class "Default")
      (node (ref "RN6") (pin "1") (pinfunction "1_1") (pintype "input"))
      (node (ref "U5") (pin "K1") (pinfunction "ODT_K1") (pintype "input"))
      (node (ref "U7") (pin "N5") (pinfunction "PS_DDR_ODT_502_N5") (pintype "input"))
    )
    (net (code "154") (name "DDR_RAS") (class "Default")
      (node (ref "RN3") (pin "2") (pinfunction "2_2") (pintype "input"))
      (node (ref "U5") (pin "J3") (pinfunction "RAS#_J3") (pintype "input"))
      (node (ref "U7") (pin "P4") (pinfunction "PS_DDR_RAS_B_502_P4") (pintype "input"))
    )
    (net (code "155") (name "DDR_RESET") (class "Default")
      (node (ref "R21") (pin "2") (pinfunction "2_2") (pintype "input"))
      (node (ref "U5") (pin "T2") (pinfunction "RESET#_T2") (pintype "input"))
      (node (ref "U7") (pin "B4") (pinfunction "PS_DDR_DRST_B_502_B4") (pintype "input"))
    )
    (net (code "156") (name "DDR_WE") (class "Default")
      (node (ref "RN4") (pin "4") (pinfunction "4_4") (pintype "input"))
      (node (ref "U5") (pin "L3") (pinfunction "WE#_L3") (pintype "input"))
      (node (ref "U7") (pin "M5") (pinfunction "PS_DDR_WE_B_502_M5") (pintype "input"))
    )
    (net (code "157") (name "DONE") (class "Default")
      (node (ref "R77") (pin "2") (pinfunction "2_2") (pintype "input"))
      (node (ref "R78") (pin "2") (pinfunction "2_2") (pintype "input"))
      (node (ref "U7") (pin "R11") (pinfunction "DONE_0_R11") (pintype "input"))
    )
    (net (code "158") (name "ETH_RXCTL") (class "Default")
      (node (ref "U7") (pin "D13") (pinfunction "PS_MIO27_501_D13") (pintype "input"))
    )
    (net (code "159") (name "ETH_RXD0") (class "Default")
      (node (ref "U7") (pin "D11") (pinfunction "PS_MIO23_501_D11") (pintype "input"))
    )
    (net (code "160") (name "ETH_RXD1") (class "Default")
      (node (ref "U7") (pin "A16") (pinfunction "PS_MIO24_501_A16") (pintype "input"))
    )
    (net (code "161") (name "ETH_RXD2") (class "Default")
      (node (ref "U7") (pin "F15") (pinfunction "PS_MIO25_501_F15") (pintype "input"))
    )
    (net (code "162") (name "ETH_RXD3") (class "Default")
      (node (ref "U7") (pin "A15") (pinfunction "PS_MIO26_501_A15") (pintype "input"))
    )
    (net (code "163") (name "ETH_RX_CLK") (class "Default")
      (node (ref "U7") (pin "B17") (pinfunction "PS_MIO22_501_B17") (pintype "input"))
    )
    (net (code "164") (name "ETH_TXCTL") (class "Default")
      (node (ref "U7") (pin "F14") (pinfunction "PS_MIO21_501_F14") (pintype "input"))
    )
    (net (code "165") (name "ETH_TXD0") (class "Default")
      (node (ref "U7") (pin "E14") (pinfunction "PS_MIO17_501_E14") (pintype "input"))
    )
    (net (code "166") (name "ETH_TXD1") (class "Default")
      (node (ref "U7") (pin "B18") (pinfunction "PS_MIO18_501_B18") (pintype "input"))
    )
    (net (code "167") (name "ETH_TXD2") (class "Default")
      (node (ref "U7") (pin "D10") (pinfunction "PS_MIO19_501_D10") (pintype "input"))
    )
    (net (code "168") (name "ETH_TXD3") (class "Default")
      (node (ref "U7") (pin "A17") (pinfunction "PS_MIO20_501_A17") (pintype "input"))
    )
    (net (code "169") (name "ETH_TX_CLK") (class "Default")
      (node (ref "U7") (pin "A19") (pinfunction "PS_MIO16_501_A19") (pintype "input"))
    )
    (net (code "170") (name "GND") (class "Default")
      (node (ref "C1") (pin "2") (pinfunction "2_2") (pintype "input"))
      (node (ref "C10") (pin "2") (pinfunction "2_2") (pintype "input"))
      (node (ref "C11") (pin "2") (pinfunction "2_2") (pintype "input"))
      (node (ref "C12") (pin "2") (pinfunction "2_2") (pintype "input"))
      (node (ref "C13") (pin "2") (pinfunction "2_2") (pintype "input"))
      (node (ref "C14") (pin "2") (pinfunction "2_2") (pintype "input"))
      (node (ref "C15") (pin "1") (pinfunction "1_1") (pintype "input"))
      (node (ref "C16") (pin "1") (pinfunction "1_1") (pintype "input"))
      (node (ref "C17") (pin "1") (pinfunction "1_1") (pintype "input"))
      (node (ref "C18") (pin "1") (pinfunction "1_1") (pintype "input"))
      (node (ref "C19") (pin "1") (pinfunction "1_1") (pintype "input"))
      (node (ref "C2") (pin "2") (pinfunction "2_2") (pintype "input"))
      (node (ref "C20") (pin "1") (pinfunction "1_1") (pintype "input"))
      (node (ref "C21") (pin "1") (pinfunction "1_1") (pintype "input"))
      (node (ref "C22") (pin "1") (pinfunction "1_1") (pintype "input"))
      (node (ref "C23") (pin "1") (pinfunction "1_1") (pintype "input"))
      (node (ref "C24") (pin "1") (pinfunction "1_1") (pintype "input"))
      (node (ref "C25") (pin "1") (pinfunction "1_1") (pintype "input"))
      (node (ref "C26") (pin "1") (pinfunction "1_1") (pintype "input"))
      (node (ref "C3") (pin "2") (pinfunction "2_2") (pintype "input"))
      (node (ref "C30") (pin "1") (pinfunction "1_1") (pintype "input"))
      (node (ref "C31") (pin "1") (pinfunction "1_1") (pintype "input"))
      (node (ref "C32") (pin "1") (pinfunction "1_1") (pintype "input"))
      (node (ref "C33") (pin "1") (pinfunction "1_1") (pintype "input"))
      (node (ref "C35") (pin "2") (pinfunction "2_2") (pintype "input"))
      (node (ref "C37") (pin "2") (pinfunction "2_2") (pintype "input"))
      (node (ref "C38") (pin "2") (pinfunction "2_2") (pintype "input"))
      (node (ref "C39") (pin "2") (pinfunction "2_2") (pintype "input"))
      (node (ref "C40") (pin "2") (pinfunction "2_2") (pintype "input"))
      (node (ref "C41") (pin "2") (pinfunction "2_2") (pintype "input"))
      (node (ref "C43") (pin "2") (pinfunction "2_2") (pintype "input"))
      (node (ref "C44") (pin "2") (pinfunction "2_2") (pintype "input"))
      (node (ref "C45") (pin "2") (pinfunction "2_2") (pintype "input"))
      (node (ref "C46") (pin "2") (pinfunction "2_2") (pintype "input"))
      (node (ref "C47") (pin "1") (pinfunction "1_1") (pintype "input"))
      (node (ref "C48") (pin "2") (pinfunction "2_2") (pintype "input"))
      (node (ref "C49") (pin "2") (pinfunction "2_2") (pintype "input"))
      (node (ref "C5") (pin "2") (pinfunction "2_2") (pintype "input"))
      (node (ref "C50") (pin "2") (pinfunction "2_2") (pintype "input"))
      (node (ref "C51") (pin "2") (pinfunction "2_2") (pintype "input"))
      (node (ref "C53") (pin "2") (pinfunction "2_2") (pintype "input"))
      (node (ref "C54") (pin "1") (pinfunction "1_1") (pintype "input"))
      (node (ref "C55") (pin "2") (pinfunction "2_2") (pintype "input"))
      (node (ref "C56") (pin "1") (pinfunction "1_1") (pintype "input"))
      (node (ref "C57") (pin "1") (pinfunction "1_1") (pintype "input"))
      (node (ref "C58") (pin "1") (pinfunction "1_1") (pintype "input"))
      (node (ref "C59") (pin "1") (pinfunction "1_1") (pintype "input"))
      (node (ref "C6") (pin "2") (pinfunction "2_2") (pintype "input"))
      (node (ref "C60") (pin "1") (pinfunction "1_1") (pintype "input"))
      (node (ref "C61") (pin "1") (pinfunction "1_1") (pintype "input"))
      (node (ref "C62") (pin "1") (pinfunction "1_1") (pintype "input"))
      (node (ref "C63") (pin "1") (pinfunction "1_1") (pintype "input"))
      (node (ref "C64") (pin "1") (pinfunction "1_1") (pintype "input"))
      (node (ref "C65") (pin "1") (pinfunction "1_1") (pintype "input"))
      (node (ref "C66") (pin "1") (pinfunction "1_1") (pintype "input"))
      (node (ref "C67") (pin "1") (pinfunction "1_1") (pintype "input"))
      (node (ref "C68") (pin "1") (pinfunction "1_1") (pintype "input"))
      (node (ref "C69") (pin "1") (pinfunction "1_1") (pintype "input"))
      (node (ref "C7") (pin "2") (pinfunction "2_2") (pintype "input"))
      (node (ref "C70") (pin "1") (pinfunction "1_1") (pintype "input"))
      (node (ref "C71") (pin "1") (pinfunction "1_1") (pintype "input"))
      (node (ref "C73") (pin "1") (pinfunction "1_1") (pintype "input"))
      (node (ref "C74") (pin "1") (pinfunction "1_1") (pintype "input"))
      (node (ref "C75") (pin "1") (pinfunction "1_1") (pintype "input"))
      (node (ref "C76") (pin "1") (pinfunction "1_1") (pintype "input"))
      (node (ref "C8") (pin "2") (pinfunction "2_2") (pintype "input"))
      (node (ref "C80") (pin "2") (pinfunction "2_2") (pintype "input"))
      (node (ref "C81") (pin "2") (pinfunction "2_2") (pintype "input"))
      (node (ref "C82") (pin "1") (pinfunction "1_1") (pintype "input"))
      (node (ref "C9") (pin "2") (pinfunction "2_2") (pintype "input"))
      (node (ref "CN1") (pin "1") (pinfunction "1_1") (pintype "input"))
      (node (ref "CN1") (pin "19") (pinfunction "19_19") (pintype "input"))
      (node (ref "CN1") (pin "2") (pinfunction "2_2") (pintype "input"))
      (node (ref "CN1") (pin "20") (pinfunction "20_20") (pintype "input"))
      (node (ref "CN1") (pin "37") (pinfunction "37_37") (pintype "input"))
      (node (ref "CN1") (pin "38") (pinfunction "38_38") (pintype "input"))
      (node (ref "CN1") (pin "55") (pinfunction "55_55") (pintype "input"))
      (node (ref "CN1") (pin "56") (pinfunction "56_56") (pintype "input"))
      (node (ref "CN2") (pin "1") (pinfunction "1_1") (pintype "input"))
      (node (ref "CN2") (pin "19") (pinfunction "19_19") (pintype "input"))
      (node (ref "CN2") (pin "2") (pinfunction "2_2") (pintype "input"))
      (node (ref "CN2") (pin "20") (pinfunction "20_20") (pintype "input"))
      (node (ref "CN2") (pin "37") (pinfunction "37_37") (pintype "input"))
      (node (ref "CN2") (pin "38") (pinfunction "38_38") (pintype "input"))
      (node (ref "CN2") (pin "55") (pinfunction "55_55") (pintype "input"))
      (node (ref "CN2") (pin "56") (pinfunction "56_56") (pintype "input"))
      (node (ref "CN3") (pin "5") (pinfunction "5_5") (pintype "input"))
      (node (ref "L1") (pin "2") (pinfunction "GND_2") (pintype "input"))
      (node (ref "L1") (pin "4") (pinfunction "GND_4") (pintype "input"))
      (node (ref "L2") (pin "2") (pinfunction "GND_2") (pintype "input"))
      (node (ref "L2") (pin "4") (pinfunction "GND_4") (pintype "input"))
      (node (ref "L4") (pin "2") (pinfunction "GND_2") (pintype "input"))
      (node (ref "L4") (pin "4") (pinfunction "GND_4") (pintype "input"))
      (node (ref "L5") (pin "2") (pinfunction "GND_2") (pintype "input"))
      (node (ref "L5") (pin "4") (pinfunction "GND_4") (pintype "input"))
      (node (ref "LED1") (pin "1") (pinfunction "C_1") (pintype "input"))
      (node (ref "LED2") (pin "1") (pinfunction "C_1") (pintype "input"))
      (node (ref "LED3") (pin "1") (pinfunction "C_1") (pintype "input"))
      (node (ref "R13") (pin "2") (pinfunction "2_2") (pintype "input"))
      (node (ref "R15") (pin "2") (pinfunction "2_2") (pintype "input"))
      (node (ref "R18") (pin "2") (pinfunction "2_2") (pintype "input"))
      (node (ref "R19") (pin "1") (pinfunction "1_1") (pintype "input"))
      (node (ref "R21") (pin "1") (pinfunction "1_1") (pintype "input"))
      (node (ref "R24") (pin "2") (pinfunction "2_2") (pintype "input"))
      (node (ref "R26") (pin "2") (pinfunction "2_2") (pintype "input"))
      (node (ref "R3") (pin "2") (pinfunction "2_2") (pintype "input"))
      (node (ref "R30") (pin "1") (pinfunction "1_1") (pintype "input"))
      (node (ref "R31") (pin "1") (pinfunction "1_1") (pintype "input"))
      (node (ref "R32") (pin "1") (pinfunction "1_1") (pintype "input"))
      (node (ref "R33") (pin "1") (pinfunction "1_1") (pintype "input"))
      (node (ref "R37") (pin "2") (pinfunction "2_2") (pintype "input"))
      (node (ref "R41") (pin "1") (pinfunction "1_1") (pintype "input"))
      (node (ref "R7") (pin "2") (pinfunction "2_2") (pintype "input"))
      (node (ref "R79") (pin "1") (pinfunction "1_1") (pintype "input"))
      (node (ref "R80") (pin "1") (pinfunction "1_1") (pintype "input"))
      (node (ref "R9") (pin "2") (pinfunction "2_2") (pintype "input"))
      (node (ref "SW1") (pin "1") (pinfunction "A1_1") (pintype "input"))
      (node (ref "SW1") (pin "2") (pinfunction "A2_2") (pintype "input"))
      (node (ref "U1") (pin "3") (pinfunction "GND_3") (pintype "input"))
      (node (ref "U1") (pin "9") (pinfunction "EP_9") (pintype "input"))
      (node (ref "U10") (pin "4") (pinfunction "GND_4") (pintype "input"))
      (node (ref "U10") (pin "9") (pinfunction "EP_9") (pintype "input"))
      (node (ref "U11") (pin "3") (pinfunction "VSS_3") (pintype "input"))
      (node (ref "U2") (pin "3") (pinfunction "GND_3") (pintype "input"))
      (node (ref "U2") (pin "9") (pinfunction "EP_9") (pintype "input"))
      (node (ref "U3") (pin "3") (pinfunction "GND_3") (pintype "input"))
      (node (ref "U3") (pin "9") (pinfunction "EP_9") (pintype "input"))
      (node (ref "U4") (pin "3") (pinfunction "GND_3") (pintype "input"))
      (node (ref "U4") (pin "9") (pinfunction "EP_9") (pintype "input"))
      (node (ref "U5") (pin "A9") (pinfunction "VSS_A9") (pintype "input"))
      (node (ref "U5") (pin "B1") (pinfunction "VSSQ_B1") (pintype "input"))
      (node (ref "U5") (pin "B3") (pinfunction "VSS_B3") (pintype "input"))
      (node (ref "U5") (pin "B9") (pinfunction "VSSQ_B9") (pintype "input"))
      (node (ref "U5") (pin "D1") (pinfunction "VSSQ_D1") (pintype "input"))
      (node (ref "U5") (pin "D8") (pinfunction "VSSQ_D8") (pintype "input"))
      (node (ref "U5") (pin "E1") (pinfunction "VSS_E1") (pintype "input"))
      (node (ref "U5") (pin "E2") (pinfunction "VSSQ_E2") (pintype "input"))
      (node (ref "U5") (pin "E8") (pinfunction "VSSQ_E8") (pintype "input"))
      (node (ref "U5") (pin "F9") (pinfunction "VSSQ_F9") (pintype "input"))
      (node (ref "U5") (pin "G1") (pinfunction "VSSQ_G1") (pintype "input"))
      (node (ref "U5") (pin "G8") (pinfunction "VSS_G8") (pintype "input"))
      (node (ref "U5") (pin "G9") (pinfunction "VSSQ_G9") (pintype "input"))
      (node (ref "U5") (pin "J2") (pinfunction "VSS_J2") (pintype "input"))
      (node (ref "U5") (pin "J8") (pinfunction "VSS_J8") (pintype "input"))
      (node (ref "U5") (pin "M1") (pinfunction "VSS_M1") (pintype "input"))
      (node (ref "U5") (pin "M9") (pinfunction "VSS_M9") (pintype "input"))
      (node (ref "U5") (pin "P1") (pinfunction "VSS_P1") (pintype "input"))
      (node (ref "U5") (pin "P9") (pinfunction "VSS_P9") (pintype "input"))
      (node (ref "U5") (pin "T1") (pinfunction "VSS_T1") (pintype "input"))
      (node (ref "U5") (pin "T9") (pinfunction "VSS_T9") (pintype "input"))
      (node (ref "U7") (pin "A18") (pinfunction "GND_A18") (pintype "input"))
      (node (ref "U7") (pin "A8") (pinfunction "GND_A8") (pintype "input"))
      (node (ref "U7") (pin "B1") (pinfunction "GND_B1") (pintype "input"))
      (node (ref "U7") (pin "B11") (pinfunction "GND_B11") (pintype "input"))
      (node (ref "U7") (pin "C14") (pinfunction "GND_C14") (pintype "input"))
      (node (ref "U7") (pin "C4") (pinfunction "GND_C4") (pintype "input"))
      (node (ref "U7") (pin "C9") (pinfunction "GND_C9") (pintype "input"))
      (node (ref "U7") (pin "D17") (pinfunction "GND_D17") (pintype "input"))
      (node (ref "U7") (pin "E10") (pinfunction "GND_E10") (pintype "input"))
      (node (ref "U7") (pin "E20") (pinfunction "GND_E20") (pintype "input"))
      (node (ref "U7") (pin "F10") (pinfunction "RSVDGND_F10") (pintype "input"))
      (node (ref "U7") (pin "F3") (pinfunction "GND_F3") (pintype "input"))
      (node (ref "U7") (pin "F7") (pinfunction "GND_F7") (pintype "input"))
      (node (ref "U7") (pin "G10") (pinfunction "GND_G10") (pintype "input"))
      (node (ref "U7") (pin "G12") (pinfunction "GND_G12") (pintype "input"))
      (node (ref "U7") (pin "G16") (pinfunction "GND_G16") (pintype "input"))
      (node (ref "U7") (pin "H11") (pinfunction "GND_H11") (pintype "input"))
      (node (ref "U7") (pin "H13") (pinfunction "GND_H13") (pintype "input"))
      (node (ref "U7") (pin "H19") (pinfunction "GND_H19") (pintype "input"))
      (node (ref "U7") (pin "H7") (pinfunction "GND_H7") (pintype "input"))
      (node (ref "U7") (pin "H9") (pinfunction "GND_H9") (pintype "input"))
      (node (ref "U7") (pin "J10") (pinfunction "GNDADC_0_J10") (pintype "input"))
      (node (ref "U7") (pin "J12") (pinfunction "GND_J12") (pintype "input"))
      (node (ref "U7") (pin "J2") (pinfunction "GND_J2") (pintype "input"))
      (node (ref "U7") (pin "J8") (pinfunction "GND_J8") (pintype "input"))
      (node (ref "U7") (pin "K10") (pinfunction "VREFN_0_K10") (pintype "input"))
      (node (ref "U7") (pin "K11") (pinfunction "GND_K11") (pintype "input"))
      (node (ref "U7") (pin "K13") (pinfunction "GND_K13") (pintype "input"))
      (node (ref "U7") (pin "K15") (pinfunction "GND_K15") (pintype "input"))
      (node (ref "U7") (pin "K5") (pinfunction "GND_K5") (pintype "input"))
      (node (ref "U7") (pin "K7") (pinfunction "GND_K7") (pintype "input"))
      (node (ref "U7") (pin "L12") (pinfunction "GND_L12") (pintype "input"))
      (node (ref "U7") (pin "L18") (pinfunction "GND_L18") (pintype "input"))
      (node (ref "U7") (pin "L8") (pinfunction "GND_L8") (pintype "input"))
      (node (ref "U7") (pin "L9") (pinfunction "VREFP_0_L9") (pintype "input"))
      (node (ref "U7") (pin "M1") (pinfunction "GND_M1") (pintype "input"))
      (node (ref "U7") (pin "M10") (pinfunction "DXN_0_M10") (pintype "input"))
      (node (ref "U7") (pin "M11") (pinfunction "GND_M11") (pintype "input"))
      (node (ref "U7") (pin "M13") (pinfunction "GND_M13") (pintype "input"))
      (node (ref "U7") (pin "M7") (pinfunction "GND_M7") (pintype "input"))
      (node (ref "U7") (pin "M9") (pinfunction "DXP_0_M9") (pintype "input"))
      (node (ref "U7") (pin "N10") (pinfunction "GND_N10") (pintype "input"))
      (node (ref "U7") (pin "N12") (pinfunction "GND_N12") (pintype "input"))
      (node (ref "U7") (pin "N14") (pinfunction "GND_N14") (pintype "input"))
      (node (ref "U7") (pin "N4") (pinfunction "GND_N4") (pintype "input"))
      (node (ref "U7") (pin "N8") (pinfunction "GND_N8") (pintype "input"))
      (node (ref "U7") (pin "P11") (pinfunction "GND_P11") (pintype "input"))
      (node (ref "U7") (pin "P13") (pinfunction "GND_P13") (pintype "input"))
      (node (ref "U7") (pin "P17") (pinfunction "GND_P17") (pintype "input"))
      (node (ref "U7") (pin "P7") (pinfunction "GND_P7") (pintype "input"))
      (node (ref "U7") (pin "P9") (pinfunction "GND_P9") (pintype "input"))
      (node (ref "U7") (pin "R12") (pinfunction "GND_R12") (pintype "input"))
      (node (ref "U7") (pin "R20") (pinfunction "GND_R20") (pintype "input"))
      (node (ref "U7") (pin "R8") (pinfunction "GND_R8") (pintype "input"))
      (node (ref "U7") (pin "T13") (pinfunction "GND_T13") (pintype "input"))
      (node (ref "U7") (pin "T3") (pinfunction "GND_T3") (pintype "input"))
      (node (ref "U7") (pin "T7") (pinfunction "GND_T7") (pintype "input"))
      (node (ref "U7") (pin "U16") (pinfunction "GND_U16") (pintype "input"))
      (node (ref "U7") (pin "U6") (pinfunction "GND_U6") (pintype "input"))
      (node (ref "U7") (pin "V19") (pinfunction "GND_V19") (pintype "input"))
      (node (ref "U7") (pin "V9") (pinfunction "GND_V9") (pintype "input"))
      (node (ref "U7") (pin "W12") (pinfunction "GND_W12") (pintype "input"))
      (node (ref "U7") (pin "W2") (pinfunction "GND_W2") (pintype "input"))
      (node (ref "U7") (pin "Y15") (pinfunction "GND_Y15") (pintype "input"))
      (node (ref "U7") (pin "Y5") (pinfunction "GND_Y5") (pintype "input"))
      (node (ref "U8") (pin "11") (pinfunction "GND_11") (pintype "input"))
      (node (ref "U8") (pin "2") (pinfunction "GND_2") (pintype "input"))
      (node (ref "U8") (pin "25") (pinfunction "EP_25") (pintype "input"))
      (node (ref "U9") (pin "17") (pinfunction "EP_17") (pintype "unspecified"))
      (node (ref "U9") (pin "2") (pinfunction "GND_2") (pintype "unspecified"))
      (node (ref "USB1") (pin "1") (pinfunction "EP_1") (pintype "input"))
      (node (ref "USB1") (pin "2") (pinfunction "EP_2") (pintype "input"))
      (node (ref "USB1") (pin "3") (pinfunction "EP_3") (pintype "input"))
      (node (ref "USB1") (pin "4") (pinfunction "EP_4") (pintype "input"))
      (node (ref "USB1") (pin "A1") (pinfunction "GND_A1") (pintype "input"))
      (node (ref "USB1") (pin "A12") (pinfunction "GND_A12") (pintype "input"))
      (node (ref "USB1") (pin "B1") (pinfunction "GND_B1") (pintype "input"))
      (node (ref "USB1") (pin "B12") (pinfunction "GND_B12") (pintype "input"))
      (node (ref "X1") (pin "2") (pinfunction "GND_2") (pintype "input"))
      (node (ref "X2") (pin "2") (pinfunction "GND_2") (pintype "unspecified"))
    )
    (net (code "171") (name "JTAG_TCK") (class "Default")
      (node (ref "CN1") (pin "3") (pinfunction "3_3") (pintype "input"))
      (node (ref "CN3") (pin "1") (pinfunction "1_1") (pintype "input"))
      (node (ref "U7") (pin "F9") (pinfunction "TCK_0_F9") (pintype "input"))
    )
    (net (code "172") (name "JTAG_TDI") (class "Default")
      (node (ref "CN1") (pin "6") (pinfunction "6_6") (pintype "input"))
      (node (ref "CN3") (pin "3") (pinfunction "3_3") (pintype "input"))
      (node (ref "U7") (pin "G6") (pinfunction "TDI_0_G6") (pintype "input"))
    )
    (net (code "173") (name "JTAG_TDO") (class "Default")
      (node (ref "CN1") (pin "5") (pinfunction "5_5") (pintype "input"))
      (node (ref "CN3") (pin "2") (pinfunction "2_2") (pintype "input"))
      (node (ref "U7") (pin "F6") (pinfunction "TDO_0_F6") (pintype "input"))
    )
    (net (code "174") (name "JTAG_TMS") (class "Default")
      (node (ref "CN1") (pin "4") (pinfunction "4_4") (pintype "input"))
      (node (ref "CN3") (pin "4") (pinfunction "4_4") (pintype "input"))
      (node (ref "U7") (pin "J6") (pinfunction "TMS_0_J6") (pintype "input"))
    )
    (net (code "175") (name "MIO7") (class "Default")
      (node (ref "R33") (pin "2") (pinfunction "2_2") (pintype "input"))
      (node (ref "U7") (pin "D8") (pinfunction "PS_MIO7_500_D8") (pintype "input"))
    )
    (net (code "176") (name "MIO8") (class "Default")
      (node (ref "R28") (pin "2") (pinfunction "2_2") (pintype "input"))
      (node (ref "U7") (pin "D5") (pinfunction "PS_MIO8_500_D5") (pintype "input"))
    )
    (net (code "177") (name "Net-(L1-OUT)") (class "Default")
      (node (ref "C7") (pin "1") (pinfunction "1_1") (pintype "input"))
      (node (ref "L1") (pin "3") (pinfunction "OUT_3") (pintype "input"))
      (node (ref "R8") (pin "1") (pinfunction "1_1") (pintype "input"))
      (node (ref "U1") (pin "4") (pinfunction "VOUT_4") (pintype "input"))
      (node (ref "U1") (pin "5") (pinfunction "VOUT_5") (pintype "input"))
    )
    (net (code "178") (name "Net-(L2-OUT)") (class "Default")
      (node (ref "C8") (pin "1") (pinfunction "1_1") (pintype "input"))
      (node (ref "L2") (pin "3") (pinfunction "OUT_3") (pintype "input"))
      (node (ref "R10") (pin "1") (pinfunction "1_1") (pintype "input"))
      (node (ref "U2") (pin "4") (pinfunction "VOUT_4") (pintype "input"))
      (node (ref "U2") (pin "5") (pinfunction "VOUT_5") (pintype "input"))
    )
    (net (code "179") (name "Net-(L4-OUT)") (class "Default")
      (node (ref "C13") (pin "1") (pinfunction "1_1") (pintype "input"))
      (node (ref "L4") (pin "3") (pinfunction "OUT_3") (pintype "input"))
      (node (ref "R14") (pin "1") (pinfunction "1_1") (pintype "input"))
      (node (ref "U3") (pin "4") (pinfunction "VOUT_4") (pintype "input"))
      (node (ref "U3") (pin "5") (pinfunction "VOUT_5") (pintype "input"))
    )
    (net (code "180") (name "Net-(L5-OUT)") (class "Default")
      (node (ref "C14") (pin "1") (pinfunction "1_1") (pintype "input"))
      (node (ref "L5") (pin "3") (pinfunction "OUT_3") (pintype "input"))
      (node (ref "R16") (pin "1") (pinfunction "1_1") (pintype "input"))
      (node (ref "U4") (pin "4") (pinfunction "VOUT_4") (pintype "input"))
      (node (ref "U4") (pin "5") (pinfunction "VOUT_5") (pintype "input"))
    )
    (net (code "181") (name "Net-(LED1-A)") (class "Default")
      (node (ref "LED1") (pin "2") (pinfunction "A_2") (pintype "input"))
      (node (ref "R77") (pin "1") (pinfunction "1_1") (pintype "input"))
    )
    (net (code "182") (name "Net-(LED2-A)") (class "Default")
      (node (ref "LED2") (pin "2") (pinfunction "A_2") (pintype "input"))
      (node (ref "R81") (pin "1") (pinfunction "1_1") (pintype "input"))
    )
    (net (code "183") (name "Net-(LED3-A)") (class "Default")
      (node (ref "LED3") (pin "2") (pinfunction "A_2") (pintype "input"))
      (node (ref "R82") (pin "1") (pinfunction "1_1") (pintype "input"))
    )
    (net (code "184") (name "Net-(SW1-B1)") (class "Default")
      (node (ref "R74") (pin "1") (pinfunction "1_1") (pintype "input"))
      (node (ref "R75") (pin "1") (pinfunction "1_1") (pintype "input"))
      (node (ref "SW1") (pin "4") (pinfunction "B1_4") (pintype "input"))
    )
    (net (code "185") (name "Net-(SW1-B2)") (class "Default")
      (node (ref "R73") (pin "1") (pinfunction "1_1") (pintype "input"))
      (node (ref "R76") (pin "1") (pinfunction "1_1") (pintype "input"))
      (node (ref "SW1") (pin "3") (pinfunction "B2_3") (pintype "input"))
    )
    (net (code "186") (name "Net-(U1-FB)") (class "Default")
      (node (ref "R7") (pin "1") (pinfunction "1_1") (pintype "input"))
      (node (ref "R8") (pin "2") (pinfunction "2_2") (pintype "input"))
      (node (ref "U1") (pin "6") (pinfunction "FB_6") (pintype "input"))
    )
    (net (code "187") (name "Net-(U1-SS{slash}TR)") (class "Default")
      (node (ref "C2") (pin "1") (pinfunction "1_1") (pintype "input"))
      (node (ref "U1") (pin "8") (pinfunction "SS/TR_8") (pintype "input"))
    )
    (net (code "188") (name "Net-(U2-FB)") (class "Default")
      (node (ref "R10") (pin "2") (pinfunction "2_2") (pintype "input"))
      (node (ref "R9") (pin "1") (pinfunction "1_1") (pintype "input"))
      (node (ref "U2") (pin "6") (pinfunction "FB_6") (pintype "input"))
    )
    (net (code "189") (name "Net-(U2-SS{slash}TR)") (class "Default")
      (node (ref "C3") (pin "1") (pinfunction "1_1") (pintype "input"))
      (node (ref "U2") (pin "8") (pinfunction "SS/TR_8") (pintype "input"))
    )
    (net (code "190") (name "Net-(U3-FB)") (class "Default")
      (node (ref "R13") (pin "1") (pinfunction "1_1") (pintype "input"))
      (node (ref "R14") (pin "2") (pinfunction "2_2") (pintype "input"))
      (node (ref "U3") (pin "6") (pinfunction "FB_6") (pintype "input"))
    )
    (net (code "191") (name "Net-(U3-SS{slash}TR)") (class "Default")
      (node (ref "C9") (pin "1") (pinfunction "1_1") (pintype "input"))
      (node (ref "U3") (pin "8") (pinfunction "SS/TR_8") (pintype "input"))
    )
    (net (code "192") (name "Net-(U4-FB)") (class "Default")
      (node (ref "R15") (pin "1") (pinfunction "1_1") (pintype "input"))
      (node (ref "R16") (pin "2") (pinfunction "2_2") (pintype "input"))
      (node (ref "U4") (pin "6") (pinfunction "FB_6") (pintype "input"))
    )
    (net (code "193") (name "Net-(U4-SS{slash}TR)") (class "Default")
      (node (ref "C10") (pin "1") (pinfunction "1_1") (pintype "input"))
      (node (ref "U4") (pin "8") (pinfunction "SS/TR_8") (pintype "input"))
    )
    (net (code "194") (name "Net-(U5-ZQ)") (class "Default")
      (node (ref "R18") (pin "1") (pinfunction "1_1") (pintype "input"))
      (node (ref "U5") (pin "L8") (pinfunction "ZQ_L8") (pintype "input"))
    )
    (net (code "195") (name "Net-(U7A-PS_MIO6_500)") (class "Default")
      (node (ref "R39") (pin "1") (pinfunction "1_1") (pintype "input"))
      (node (ref "U7") (pin "A5") (pinfunction "PS_MIO6_500_A5") (pintype "input"))
    )
    (net (code "196") (name "Net-(U7A-PS_POR_B_500)") (class "Default")
      (node (ref "R36") (pin "2") (pinfunction "2_2") (pintype "input"))
      (node (ref "U7") (pin "C7") (pinfunction "PS_POR_B_500_C7") (pintype "input"))
    )
    (net (code "197") (name "Net-(U7B-PS_MIO40_501)") (class "Default")
      (node (ref "R40") (pin "1") (pinfunction "1_1") (pintype "input"))
      (node (ref "U7") (pin "D14") (pinfunction "PS_MIO40_501_D14") (pintype "input"))
    )
    (net (code "198") (name "Net-(U7B-PS_MIO_VREF_501)") (class "Default")
      (node (ref "C48") (pin "1") (pinfunction "1_1") (pintype "input"))
      (node (ref "R37") (pin "1") (pinfunction "1_1") (pintype "input"))
      (node (ref "R38") (pin "2") (pinfunction "2_2") (pintype "input"))
      (node (ref "U7") (pin "E11") (pinfunction "PS_MIO_VREF_501_E11") (pintype "input"))
    )
    (net (code "199") (name "Net-(U7B-PS_SRST_B_501)") (class "Default")
      (node (ref "R34") (pin "1") (pinfunction "1_1") (pintype "input"))
      (node (ref "U7") (pin "B10") (pinfunction "PS_SRST_B_501_B10") (pintype "input"))
    )
    (net (code "200") (name "Net-(U7C-INIT_B_0)") (class "Default")
      (node (ref "R1") (pin "2") (pinfunction "2_2") (pintype "input"))
      (node (ref "U7") (pin "R10") (pinfunction "INIT_B_0_R10") (pintype "input"))
    )
    (net (code "201") (name "Net-(U7C-PROGRAM_B_0)") (class "Default")
      (node (ref "R2") (pin "2") (pinfunction "2_2") (pintype "input"))
      (node (ref "U7") (pin "L6") (pinfunction "PROGRAM_B_0_L6") (pintype "input"))
    )
    (net (code "202") (name "Net-(U7E-PS_DDR_VRN_502)") (class "Default")
      (node (ref "R20") (pin "2") (pinfunction "2_2") (pintype "input"))
      (node (ref "U7") (pin "G5") (pinfunction "PS_DDR_VRN_502_G5") (pintype "input"))
    )
    (net (code "203") (name "Net-(U7E-PS_DDR_VRP_502)") (class "Default")
      (node (ref "R19") (pin "2") (pinfunction "2_2") (pintype "input"))
      (node (ref "U7") (pin "H5") (pinfunction "PS_DDR_VRP_502_H5") (pintype "input"))
    )
    (net (code "204") (name "Net-(U7F-PS_DDR_VREF0_502)") (class "Default")
      (node (ref "C1") (pin "1") (pinfunction "1_1") (pintype "input"))
      (node (ref "R3") (pin "1") (pinfunction "1_1") (pintype "input"))
      (node (ref "R6") (pin "2") (pinfunction "2_2") (pintype "input"))
      (node (ref "U7") (pin "H6") (pinfunction "PS_DDR_VREF0_502_H6") (pintype "input"))
      (node (ref "U7") (pin "P6") (pinfunction "PS_DDR_VREF1_502_P6") (pintype "input"))
    )
    (net (code "205") (name "Net-(U8-SEL)") (class "Default")
      (node (ref "R41") (pin "2") (pinfunction "2_2") (pintype "input"))
      (node (ref "U8") (pin "24") (pinfunction "SEL_24") (pintype "input"))
    )
    (net (code "206") (name "Net-(U9-V3)") (class "Default")
      (node (ref "C54") (pin "2") (pinfunction "2_2") (pintype "input"))
      (node (ref "U9") (pin "6") (pinfunction "V3_6") (pintype "unspecified"))
    )
    (net (code "207") (name "Net-(X1-OUT)") (class "Default")
      (node (ref "R27") (pin "1") (pinfunction "1_1") (pintype "input"))
      (node (ref "X1") (pin "3") (pinfunction "OUT_3") (pintype "input"))
    )
    (net (code "208") (name "Net-(X1-VCC)") (class "Default")
      (node (ref "C44") (pin "1") (pinfunction "1_1") (pintype "input"))
      (node (ref "C45") (pin "1") (pinfunction "1_1") (pintype "input"))
      (node (ref "L6") (pin "1") (pinfunction "1_1") (pintype "input"))
      (node (ref "X1") (pin "4") (pinfunction "VCC_4") (pintype "input"))
    )
    (net (code "209") (name "Net-(X2-VDD)") (class "Default")
      (node (ref "C80") (pin "1") (pinfunction "1_1") (pintype "input"))
      (node (ref "L7") (pin "1") (pinfunction "1_1") (pintype "input"))
      (node (ref "X2") (pin "4") (pinfunction "VDD_4") (pintype "unspecified"))
    )
    (net (code "210") (name "PG_1V0") (class "Default")
      (node (ref "R4") (pin "2") (pinfunction "2_2") (pintype "input"))
      (node (ref "U1") (pin "7") (pinfunction "PG_7") (pintype "input"))
      (node (ref "U2") (pin "1") (pinfunction "EN_1") (pintype "input"))
    )
    (net (code "211") (name "PG_1V5") (class "Default")
      (node (ref "R12") (pin "1") (pinfunction "1_1") (pintype "input"))
      (node (ref "U3") (pin "1") (pinfunction "EN_1") (pintype "input"))
      (node (ref "U4") (pin "7") (pinfunction "PG_7") (pintype "input"))
    )
    (net (code "212") (name "PG_1V8") (class "Default")
      (node (ref "R5") (pin "2") (pinfunction "2_2") (pintype "input"))
      (node (ref "U2") (pin "7") (pinfunction "PG_7") (pintype "input"))
      (node (ref "U4") (pin "1") (pinfunction "EN_1") (pintype "input"))
    )
    (net (code "213") (name "PG_3V3") (class "Default")
      (node (ref "R11") (pin "2") (pinfunction "2_2") (pintype "input"))
      (node (ref "R81") (pin "2") (pinfunction "2_2") (pintype "input"))
      (node (ref "U3") (pin "7") (pinfunction "PG_7") (pintype "input"))
    )
    (net (code "214") (name "PL_CLK") (class "Default")
      (node (ref "U7") (pin "U15") (pinfunction "IO_L11N_T1_SRCC_34_U15") (pintype "input"))
      (node (ref "X2") (pin "3") (pinfunction "OUT_3") (pintype "unspecified"))
    )
    (net (code "215") (name "PS_CLK") (class "Default")
      (node (ref "R27") (pin "2") (pinfunction "2_2") (pintype "input"))
      (node (ref "U7") (pin "E7") (pinfunction "PS_CLK_500_E7") (pintype "input"))
    )
    (net (code "216") (name "QSPI_CLK") (class "Default")
      (node (ref "R32") (pin "2") (pinfunction "2_2") (pintype "input"))
      (node (ref "R39") (pin "2") (pinfunction "2_2") (pintype "input"))
      (node (ref "U10") (pin "6") (pinfunction "CLK_6") (pintype "input"))
    )
    (net (code "217") (name "QSPI_CS") (class "Default")
      (node (ref "R29") (pin "2") (pinfunction "2_2") (pintype "input"))
      (node (ref "U10") (pin "1") (pinfunction "/CS_1") (pintype "input"))
      (node (ref "U7") (pin "A7") (pinfunction "PS_MIO1_500_A7") (pintype "input"))
    )
    (net (code "218") (name "QSPI_D0") (class "Default")
      (node (ref "R30") (pin "2") (pinfunction "2_2") (pintype "input"))
      (node (ref "U10") (pin "5") (pinfunction "DI(IO0)_5") (pintype "input"))
      (node (ref "U7") (pin "B8") (pinfunction "PS_MIO2_500_B8") (pintype "input"))
    )
    (net (code "219") (name "QSPI_D1") (class "Default")
      (node (ref "R31") (pin "2") (pinfunction "2_2") (pintype "input"))
      (node (ref "U10") (pin "2") (pinfunction "DO(IO1)_2") (pintype "input"))
      (node (ref "U7") (pin "D6") (pinfunction "PS_MIO3_500_D6") (pintype "input"))
    )
    (net (code "220") (name "QSPI_D2") (class "Default")
      (node (ref "R74") (pin "2") (pinfunction "2_2") (pintype "input"))
      (node (ref "U10") (pin "3") (pinfunction "/WP(IO2)_3") (pintype "input"))
      (node (ref "U7") (pin "B7") (pinfunction "PS_MIO4_500_B7") (pintype "input"))
    )
    (net (code "221") (name "QSPI_D3") (class "Default")
      (node (ref "R73") (pin "2") (pinfunction "2_2") (pintype "input"))
      (node (ref "U10") (pin "7") (pinfunction "/HOLDor/RESET(IO3)_7") (pintype "input"))
      (node (ref "U7") (pin "A6") (pinfunction "PS_MIO5_500_A6") (pintype "input"))
    )
    (net (code "222") (name "SDO_CLK") (class "Default")
      (node (ref "U8") (pin "19") (pinfunction "CLKB0_19") (pintype "input"))
    )
    (net (code "223") (name "SDO_CMD") (class "Default")
      (node (ref "R43") (pin "1") (pinfunction "1_1") (pintype "input"))
      (node (ref "U8") (pin "20") (pinfunction "CMDB0_20") (pintype "input"))
    )
    (net (code "224") (name "SDO_D0") (class "Default")
      (node (ref "U8") (pin "18") (pinfunction "DAT0B0_18") (pintype "input"))
    )
    (net (code "225") (name "SDO_D1") (class "Default")
      (node (ref "U8") (pin "16") (pinfunction "DAT1B0_16") (pintype "input"))
    )
    (net (code "226") (name "SDO_D2") (class "Default")
      (node (ref "U8") (pin "23") (pinfunction "DAT2B0_23") (pintype "input"))
    )
    (net (code "227") (name "SDO_D3") (class "Default")
      (node (ref "R42") (pin "1") (pinfunction "1_1") (pintype "input"))
      (node (ref "U8") (pin "22") (pinfunction "DAT3B0_22") (pintype "input"))
    )
    (net (code "228") (name "SD_CD") (class "Default")
      (node (ref "U7") (pin "B14") (pinfunction "PS_MIO47_501_B14") (pintype "input"))
    )
    (net (code "229") (name "SD_CLK") (class "Default")
      (node (ref "CN2") (pin "8") (pinfunction "8_8") (pintype "input"))
      (node (ref "R40") (pin "2") (pinfunction "2_2") (pintype "input"))
      (node (ref "U8") (pin "9") (pinfunction "CLKA_9") (pintype "input"))
    )
    (net (code "230") (name "SD_CMD") (class "Default")
      (node (ref "CN2") (pin "3") (pinfunction "3_3") (pintype "input"))
      (node (ref "U7") (pin "C17") (pinfunction "PS_MIO41_501_C17") (pintype "input"))
      (node (ref "U8") (pin "4") (pinfunction "CMDA_4") (pintype "input"))
    )
    (net (code "231") (name "SD_D0") (class "Default")
      (node (ref "CN2") (pin "6") (pinfunction "6_6") (pintype "input"))
      (node (ref "U7") (pin "E12") (pinfunction "PS_MIO42_501_E12") (pintype "input"))
      (node (ref "U8") (pin "6") (pinfunction "DAT0A_6") (pintype "input"))
    )
    (net (code "232") (name "SD_D1") (class "Default")
      (node (ref "CN2") (pin "4") (pinfunction "4_4") (pintype "input"))
      (node (ref "U7") (pin "A9") (pinfunction "PS_MIO43_501_A9") (pintype "input"))
      (node (ref "U8") (pin "7") (pinfunction "DAT1A_7") (pintype "input"))
    )
    (net (code "233") (name "SD_D2") (class "Default")
      (node (ref "CN2") (pin "7") (pinfunction "7_7") (pintype "input"))
      (node (ref "U7") (pin "F13") (pinfunction "PS_MIO44_501_F13") (pintype "input"))
      (node (ref "U8") (pin "1") (pinfunction "DAT2A_1") (pintype "input"))
    )
    (net (code "234") (name "SD_D3") (class "Default")
      (node (ref "CN2") (pin "5") (pinfunction "5_5") (pintype "input"))
      (node (ref "U7") (pin "B15") (pinfunction "PS_MIO45_501_B15") (pintype "input"))
      (node (ref "U8") (pin "3") (pinfunction "DAT3A_3") (pintype "input"))
    )
    (net (code "235") (name "UART1_RX") (class "Default")
      (node (ref "U7") (pin "C12") (pinfunction "PS_MIO49_501_C12") (pintype "input"))
      (node (ref "U9") (pin "4") (pinfunction "TXD_4") (pintype "unspecified"))
    )
    (net (code "236") (name "UART1_TX") (class "Default")
      (node (ref "U7") (pin "B12") (pinfunction "PS_MIO48_501_B12") (pintype "input"))
      (node (ref "U9") (pin "5") (pinfunction "RXD_5") (pintype "unspecified"))
    )
    (net (code "237") (name "USB_5V") (class "Default")
      (node (ref "C55") (pin "1") (pinfunction "1_1") (pintype "input"))
      (node (ref "C57") (pin "2") (pinfunction "2_2") (pintype "input"))
      (node (ref "R83") (pin "1") (pinfunction "1_1") (pintype "input"))
      (node (ref "U9") (pin "3") (pinfunction "VDD5_3") (pintype "unspecified"))
      (node (ref "U9") (pin "9") (pinfunction "VBUS_9") (pintype "unspecified"))
      (node (ref "USB1") (pin "A4") (pinfunction "VBUS_A4") (pintype "input"))
      (node (ref "USB1") (pin "A9") (pinfunction "VBUS_A9") (pintype "input"))
      (node (ref "USB1") (pin "B4") (pinfunction "VBUS_B4") (pintype "input"))
      (node (ref "USB1") (pin "B9") (pinfunction "VBUS_B9") (pintype "input"))
    )
    (net (code "238") (name "USB_DN") (class "Default")
      (node (ref "U9") (pin "8") (pinfunction "UD-_8") (pintype "unspecified"))
      (node (ref "USB1") (pin "A7") (pinfunction "DN1_A7") (pintype "input"))
      (node (ref "USB1") (pin "B7") (pinfunction "DN2_B7") (pintype "input"))
    )
    (net (code "239") (name "USB_DP") (class "Default")
      (node (ref "U9") (pin "7") (pinfunction "UD+_7") (pintype "unspecified"))
      (node (ref "USB1") (pin "A6") (pinfunction "DP1_A6") (pintype "input"))
      (node (ref "USB1") (pin "B6") (pinfunction "DP2_B6") (pintype "input"))
    )
    (net (code "240") (name "VPLL") (class "Default")
      (node (ref "L3") (pin "1") (pinfunction "1_1") (pintype "input"))
      (node (ref "U7") (pin "G8") (pinfunction "VCCPLL_G8") (pintype "input"))
    )
    (net (code "241") (name "VREF_DDR") (class "Default")
      (node (ref "C36") (pin "2") (pinfunction "2_2") (pintype "input"))
      (node (ref "C37") (pin "1") (pinfunction "1_1") (pintype "input"))
      (node (ref "C42") (pin "2") (pinfunction "2_2") (pintype "input"))
      (node (ref "C43") (pin "1") (pinfunction "1_1") (pintype "input"))
      (node (ref "R25") (pin "2") (pinfunction "2_2") (pintype "input"))
      (node (ref "R26") (pin "1") (pinfunction "1_1") (pintype "input"))
      (node (ref "U5") (pin "H1") (pinfunction "VREFDQ_H1") (pintype "input"))
      (node (ref "U5") (pin "M8") (pinfunction "VREFCA_M8") (pintype "input"))
    )
    (net (code "242") (name "unconnected-(CN1-Pad7)") (class "Default")
      (node (ref "CN1") (pin "7") (pinfunction "7_7") (pintype "input"))
    )
    (net (code "243") (name "unconnected-(CN1-Pad8)") (class "Default")
      (node (ref "CN1") (pin "8") (pinfunction "8_8") (pintype "input"))
    )
    (net (code "244") (name "unconnected-(CN1-Pad9)") (class "Default")
      (node (ref "CN1") (pin "9") (pinfunction "9_9") (pintype "input"))
    )
    (net (code "245") (name "unconnected-(CN1-Pad10)") (class "Default")
      (node (ref "CN1") (pin "10") (pinfunction "10_10") (pintype "input"))
    )
    (net (code "246") (name "unconnected-(CN1-Pad11)") (class "Default")
      (node (ref "CN1") (pin "11") (pinfunction "11_11") (pintype "input"))
    )
    (net (code "247") (name "unconnected-(CN1-Pad13)") (class "Default")
      (node (ref "CN1") (pin "13") (pinfunction "13_13") (pintype "input"))
    )
    (net (code "248") (name "unconnected-(CN2-Pad9)") (class "Default")
      (node (ref "CN2") (pin "9") (pinfunction "9_9") (pintype "input"))
    )
    (net (code "249") (name "unconnected-(CN2-Pad10)") (class "Default")
      (node (ref "CN2") (pin "10") (pinfunction "10_10") (pintype "input"))
    )
    (net (code "250") (name "unconnected-(CN2-Pad11)") (class "Default")
      (node (ref "CN2") (pin "11") (pinfunction "11_11") (pintype "input"))
    )
    (net (code "251") (name "unconnected-(CN2-Pad12)") (class "Default")
      (node (ref "CN2") (pin "12") (pinfunction "12_12") (pintype "input"))
    )
    (net (code "252") (name "unconnected-(CN2-Pad13)") (class "Default")
      (node (ref "CN2") (pin "13") (pinfunction "13_13") (pintype "input"))
    )
    (net (code "253") (name "unconnected-(CN2-Pad14)") (class "Default")
      (node (ref "CN2") (pin "14") (pinfunction "14_14") (pintype "input"))
    )
    (net (code "254") (name "unconnected-(CN2-Pad15)") (class "Default")
      (node (ref "CN2") (pin "15") (pinfunction "15_15") (pintype "input"))
    )
    (net (code "255") (name "unconnected-(CN2-Pad16)") (class "Default")
      (node (ref "CN2") (pin "16") (pinfunction "16_16") (pintype "input"))
    )
    (net (code "256") (name "unconnected-(CN2-Pad17)") (class "Default")
      (node (ref "CN2") (pin "17") (pinfunction "17_17") (pintype "input"))
    )
    (net (code "257") (name "unconnected-(CN2-Pad18)") (class "Default")
      (node (ref "CN2") (pin "18") (pinfunction "18_18") (pintype "input"))
    )
    (net (code "258") (name "unconnected-(CN2-Pad22)") (class "Default")
      (node (ref "CN2") (pin "22") (pinfunction "22_22") (pintype "input"))
    )
    (net (code "259") (name "unconnected-(CN2-Pad24)") (class "Default")
      (node (ref "CN2") (pin "24") (pinfunction "24_24") (pintype "input"))
    )
    (net (code "260") (name "unconnected-(CN2-Pad26)") (class "Default")
      (node (ref "CN2") (pin "26") (pinfunction "26_26") (pintype "input"))
    )
    (net (code "261") (name "unconnected-(CN2-Pad28)") (class "Default")
      (node (ref "CN2") (pin "28") (pinfunction "28_28") (pintype "input"))
    )
    (net (code "262") (name "unconnected-(U5-NC-PadJ1)") (class "Default")
      (node (ref "U5") (pin "J1") (pinfunction "NC_J1") (pintype "input+no_connect"))
    )
    (net (code "263") (name "unconnected-(U5-NC-PadJ9)") (class "Default")
      (node (ref "U5") (pin "J9") (pinfunction "NC_J9") (pintype "input+no_connect"))
    )
    (net (code "264") (name "unconnected-(U5-NC-PadL1)") (class "Default")
      (node (ref "U5") (pin "L1") (pinfunction "NC_L1") (pintype "input+no_connect"))
    )
    (net (code "265") (name "unconnected-(U5-NC-PadL9)") (class "Default")
      (node (ref "U5") (pin "L9") (pinfunction "NC_L9") (pintype "input+no_connect"))
    )
    (net (code "266") (name "unconnected-(U5-NC-PadM7)") (class "Default")
      (node (ref "U5") (pin "M7") (pinfunction "NC_M7") (pintype "input+no_connect"))
    )
    (net (code "267") (name "unconnected-(U7A-PS_MIO0_500-PadE6)") (class "Default")
      (node (ref "U7") (pin "E6") (pinfunction "PS_MIO0_500_E6") (pintype "input"))
    )
    (net (code "268") (name "unconnected-(U7A-PS_MIO9_500-PadB5)") (class "Default")
      (node (ref "U7") (pin "B5") (pinfunction "PS_MIO9_500_B5") (pintype "input+no_connect"))
    )
    (net (code "269") (name "unconnected-(U7A-PS_MIO10_500-PadE9)") (class "Default")
      (node (ref "U7") (pin "E9") (pinfunction "PS_MIO10_500_E9") (pintype "input+no_connect"))
    )
    (net (code "270") (name "unconnected-(U7A-PS_MIO11_500-PadC6)") (class "Default")
      (node (ref "U7") (pin "C6") (pinfunction "PS_MIO11_500_C6") (pintype "input+no_connect"))
    )
    (net (code "271") (name "unconnected-(U7A-PS_MIO12_500-PadD9)") (class "Default")
      (node (ref "U7") (pin "D9") (pinfunction "PS_MIO12_500_D9") (pintype "input+no_connect"))
    )
    (net (code "272") (name "unconnected-(U7A-PS_MIO13_500-PadE8)") (class "Default")
      (node (ref "U7") (pin "E8") (pinfunction "PS_MIO13_500_E8") (pintype "input+no_connect"))
    )
    (net (code "273") (name "unconnected-(U7A-PS_MIO14_500-PadC5)") (class "Default")
      (node (ref "U7") (pin "C5") (pinfunction "PS_MIO14_500_C5") (pintype "input+no_connect"))
    )
    (net (code "274") (name "unconnected-(U7A-PS_MIO15_500-PadC8)") (class "Default")
      (node (ref "U7") (pin "C8") (pinfunction "PS_MIO15_500_C8") (pintype "input+no_connect"))
    )
    (net (code "275") (name "unconnected-(U7B-PS_MIO28_501-PadC16)") (class "Default")
      (node (ref "U7") (pin "C16") (pinfunction "PS_MIO28_501_C16") (pintype "input"))
    )
    (net (code "276") (name "unconnected-(U7B-PS_MIO29_501-PadC13)") (class "Default")
      (node (ref "U7") (pin "C13") (pinfunction "PS_MIO29_501_C13") (pintype "input"))
    )
    (net (code "277") (name "unconnected-(U7B-PS_MIO30_501-PadC15)") (class "Default")
      (node (ref "U7") (pin "C15") (pinfunction "PS_MIO30_501_C15") (pintype "input"))
    )
    (net (code "278") (name "unconnected-(U7B-PS_MIO31_501-PadE16)") (class "Default")
      (node (ref "U7") (pin "E16") (pinfunction "PS_MIO31_501_E16") (pintype "input"))
    )
    (net (code "279") (name "unconnected-(U7B-PS_MIO32_501-PadA14)") (class "Default")
      (node (ref "U7") (pin "A14") (pinfunction "PS_MIO32_501_A14") (pintype "input"))
    )
    (net (code "280") (name "unconnected-(U7B-PS_MIO33_501-PadD15)") (class "Default")
      (node (ref "U7") (pin "D15") (pinfunction "PS_MIO33_501_D15") (pintype "input"))
    )
    (net (code "281") (name "unconnected-(U7B-PS_MIO34_501-PadA12)") (class "Default")
      (node (ref "U7") (pin "A12") (pinfunction "PS_MIO34_501_A12") (pintype "input"))
    )
    (net (code "282") (name "unconnected-(U7B-PS_MIO35_501-PadF12)") (class "Default")
      (node (ref "U7") (pin "F12") (pinfunction "PS_MIO35_501_F12") (pintype "input"))
    )
    (net (code "283") (name "unconnected-(U7B-PS_MIO36_501-PadA11)") (class "Default")
      (node (ref "U7") (pin "A11") (pinfunction "PS_MIO36_501_A11") (pintype "input"))
    )
    (net (code "284") (name "unconnected-(U7B-PS_MIO37_501-PadA10)") (class "Default")
      (node (ref "U7") (pin "A10") (pinfunction "PS_MIO37_501_A10") (pintype "input"))
    )
    (net (code "285") (name "unconnected-(U7B-PS_MIO38_501-PadE13)") (class "Default")
      (node (ref "U7") (pin "E13") (pinfunction "PS_MIO38_501_E13") (pintype "input"))
    )
    (net (code "286") (name "unconnected-(U7B-PS_MIO39_501-PadC18)") (class "Default")
      (node (ref "U7") (pin "C18") (pinfunction "PS_MIO39_501_C18") (pintype "input"))
    )
    (net (code "287") (name "unconnected-(U7B-PS_MIO46_501-PadD16)") (class "Default")
      (node (ref "U7") (pin "D16") (pinfunction "PS_MIO46_501_D16") (pintype "input+no_connect"))
    )
    (net (code "288") (name "unconnected-(U7B-PS_MIO50_501-PadB13)") (class "Default")
      (node (ref "U7") (pin "B13") (pinfunction "PS_MIO50_501_B13") (pintype "input"))
    )
    (net (code "289") (name "unconnected-(U7B-PS_MIO51_501-PadB9)") (class "Default")
      (node (ref "U7") (pin "B9") (pinfunction "PS_MIO51_501_B9") (pintype "input"))
    )
    (net (code "290") (name "unconnected-(U7B-PS_MIO52_501-PadC10)") (class "Default")
      (node (ref "U7") (pin "C10") (pinfunction "PS_MIO52_501_C10") (pintype "input"))
    )
    (net (code "291") (name "unconnected-(U7B-PS_MIO53_501-PadC11)") (class "Default")
      (node (ref "U7") (pin "C11") (pinfunction "PS_MIO53_501_C11") (pintype "input"))
    )
    (net (code "292") (name "unconnected-(U7C-NC-PadT5)") (class "Default")
      (node (ref "U7") (pin "T5") (pinfunction "NC_T5") (pintype "input"))
    )
    (net (code "293") (name "unconnected-(U7C-NC-PadT9)") (class "Default")
      (node (ref "U7") (pin "T9") (pinfunction "NC_T9") (pintype "input"))
    )
    (net (code "294") (name "unconnected-(U7C-NC-PadU5)") (class "Default")
      (node (ref "U7") (pin "U5") (pinfunction "NC_U5") (pintype "input"))
    )
    (net (code "295") (name "unconnected-(U7C-NC-PadU7)") (class "Default")
      (node (ref "U7") (pin "U7") (pinfunction "NC_U7") (pintype "input"))
    )
    (net (code "296") (name "unconnected-(U7C-NC-PadU8)") (class "Default")
      (node (ref "U7") (pin "U8") (pinfunction "NC_U8") (pintype "input"))
    )
    (net (code "297") (name "unconnected-(U7C-NC-PadU9)") (class "Default")
      (node (ref "U7") (pin "U9") (pinfunction "NC_U9") (pintype "input"))
    )
    (net (code "298") (name "unconnected-(U7C-NC-PadU10)") (class "Default")
      (node (ref "U7") (pin "U10") (pinfunction "NC_U10") (pintype "input"))
    )
    (net (code "299") (name "unconnected-(U7C-NC-PadV5)") (class "Default")
      (node (ref "U7") (pin "V5") (pinfunction "NC_V5") (pintype "input"))
    )
    (net (code "300") (name "unconnected-(U7C-NC-PadV6)") (class "Default")
      (node (ref "U7") (pin "V6") (pinfunction "NC_V6") (pintype "input"))
    )
    (net (code "301") (name "unconnected-(U7C-NC-PadV7)") (class "Default")
      (node (ref "U7") (pin "V7") (pinfunction "NC_V7") (pintype "input"))
    )
    (net (code "302") (name "unconnected-(U7C-NC-PadV8)") (class "Default")
      (node (ref "U7") (pin "V8") (pinfunction "NC_V8") (pintype "input"))
    )
    (net (code "303") (name "unconnected-(U7C-NC-PadV10)") (class "Default")
      (node (ref "U7") (pin "V10") (pinfunction "NC_V10") (pintype "input"))
    )
    (net (code "304") (name "unconnected-(U7C-NC-PadV11)") (class "Default")
      (node (ref "U7") (pin "V11") (pinfunction "NC_V11") (pintype "input"))
    )
    (net (code "305") (name "unconnected-(U7C-NC-PadW6)") (class "Default")
      (node (ref "U7") (pin "W6") (pinfunction "NC_W6") (pintype "input"))
    )
    (net (code "306") (name "unconnected-(U7C-NC-PadW8)") (class "Default")
      (node (ref "U7") (pin "W8") (pinfunction "NC_W8") (pintype "input"))
    )
    (net (code "307") (name "unconnected-(U7C-NC-PadW9)") (class "Default")
      (node (ref "U7") (pin "W9") (pinfunction "NC_W9") (pintype "input"))
    )
    (net (code "308") (name "unconnected-(U7C-NC-PadW10)") (class "Default")
      (node (ref "U7") (pin "W10") (pinfunction "NC_W10") (pintype "input"))
    )
    (net (code "309") (name "unconnected-(U7C-NC-PadW11)") (class "Default")
      (node (ref "U7") (pin "W11") (pinfunction "NC_W11") (pintype "input"))
    )
    (net (code "310") (name "unconnected-(U7C-NC-PadY6)") (class "Default")
      (node (ref "U7") (pin "Y6") (pinfunction "NC_Y6") (pintype "input"))
    )
    (net (code "311") (name "unconnected-(U7C-NC-PadY7)") (class "Default")
      (node (ref "U7") (pin "Y7") (pinfunction "NC_Y7") (pintype "input"))
    )
    (net (code "312") (name "unconnected-(U7C-NC-PadY8)") (class "Default")
      (node (ref "U7") (pin "Y8") (pinfunction "NC_Y8") (pintype "input"))
    )
    (net (code "313") (name "unconnected-(U7C-NC-PadY9)") (class "Default")
      (node (ref "U7") (pin "Y9") (pinfunction "NC_Y9") (pintype "input"))
    )
    (net (code "314") (name "unconnected-(U7C-NC-PadY11)") (class "Default")
      (node (ref "U7") (pin "Y11") (pinfunction "NC_Y11") (pintype "input"))
    )
    (net (code "315") (name "unconnected-(U7C-NC-PadY12)") (class "Default")
      (node (ref "U7") (pin "Y12") (pinfunction "NC_Y12") (pintype "input"))
    )
    (net (code "316") (name "unconnected-(U7C-NC-PadY13)") (class "Default")
      (node (ref "U7") (pin "Y13") (pinfunction "NC_Y13") (pintype "input"))
    )
    (net (code "317") (name "unconnected-(U7C-VN_0-PadL10)") (class "Default")
      (node (ref "U7") (pin "L10") (pinfunction "VN_0_L10") (pintype "input"))
    )
    (net (code "318") (name "unconnected-(U7C-VP_0-PadK9)") (class "Default")
      (node (ref "U7") (pin "K9") (pinfunction "VP_0_K9") (pintype "input"))
    )
    (net (code "319") (name "unconnected-(U7E-PS_DDR_DM2_502-PadT1)") (class "Default")
      (node (ref "U7") (pin "T1") (pinfunction "PS_DDR_DM2_502_T1") (pintype "input+no_connect"))
    )
    (net (code "320") (name "unconnected-(U7E-PS_DDR_DM3_502-PadY1)") (class "Default")
      (node (ref "U7") (pin "Y1") (pinfunction "PS_DDR_DM3_502_Y1") (pintype "input+no_connect"))
    )
    (net (code "321") (name "unconnected-(U7E-PS_DDR_DQ16_502-PadP1)") (class "Default")
      (node (ref "U7") (pin "P1") (pinfunction "PS_DDR_DQ16_502_P1") (pintype "input+no_connect"))
    )
    (net (code "322") (name "unconnected-(U7E-PS_DDR_DQ17_502-PadP3)") (class "Default")
      (node (ref "U7") (pin "P3") (pinfunction "PS_DDR_DQ17_502_P3") (pintype "input+no_connect"))
    )
    (net (code "323") (name "unconnected-(U7E-PS_DDR_DQ18_502-PadR3)") (class "Default")
      (node (ref "U7") (pin "R3") (pinfunction "PS_DDR_DQ18_502_R3") (pintype "input+no_connect"))
    )
    (net (code "324") (name "unconnected-(U7E-PS_DDR_DQ19_502-PadR1)") (class "Default")
      (node (ref "U7") (pin "R1") (pinfunction "PS_DDR_DQ19_502_R1") (pintype "input+no_connect"))
    )
    (net (code "325") (name "unconnected-(U7E-PS_DDR_DQ20_502-PadT4)") (class "Default")
      (node (ref "U7") (pin "T4") (pinfunction "PS_DDR_DQ20_502_T4") (pintype "input+no_connect"))
    )
    (net (code "326") (name "unconnected-(U7E-PS_DDR_DQ21_502-PadU4)") (class "Default")
      (node (ref "U7") (pin "U4") (pinfunction "PS_DDR_DQ21_502_U4") (pintype "input+no_connect"))
    )
    (net (code "327") (name "unconnected-(U7E-PS_DDR_DQ22_502-PadU2)") (class "Default")
      (node (ref "U7") (pin "U2") (pinfunction "PS_DDR_DQ22_502_U2") (pintype "input+no_connect"))
    )
    (net (code "328") (name "unconnected-(U7E-PS_DDR_DQ23_502-PadU3)") (class "Default")
      (node (ref "U7") (pin "U3") (pinfunction "PS_DDR_DQ23_502_U3") (pintype "input+no_connect"))
    )
    (net (code "329") (name "unconnected-(U7E-PS_DDR_DQ24_502-PadV1)") (class "Default")
      (node (ref "U7") (pin "V1") (pinfunction "PS_DDR_DQ24_502_V1") (pintype "input+no_connect"))
    )
    (net (code "330") (name "unconnected-(U7E-PS_DDR_DQ25_502-PadY3)") (class "Default")
      (node (ref "U7") (pin "Y3") (pinfunction "PS_DDR_DQ25_502_Y3") (pintype "input+no_connect"))
    )
    (net (code "331") (name "unconnected-(U7E-PS_DDR_DQ26_502-PadW1)") (class "Default")
      (node (ref "U7") (pin "W1") (pinfunction "PS_DDR_DQ26_502_W1") (pintype "input+no_connect"))
    )
    (net (code "332") (name "unconnected-(U7E-PS_DDR_DQ27_502-PadY4)") (class "Default")
      (node (ref "U7") (pin "Y4") (pinfunction "PS_DDR_DQ27_502_Y4") (pintype "input+no_connect"))
    )
    (net (code "333") (name "unconnected-(U7E-PS_DDR_DQ28_502-PadY2)") (class "Default")
      (node (ref "U7") (pin "Y2") (pinfunction "PS_DDR_DQ28_502_Y2") (pintype "input+no_connect"))
    )
    (net (code "334") (name "unconnected-(U7E-PS_DDR_DQ29_502-PadW3)") (class "Default")
      (node (ref "U7") (pin "W3") (pinfunction "PS_DDR_DQ29_502_W3") (pintype "input+no_connect"))
    )
    (net (code "335") (name "unconnected-(U7E-PS_DDR_DQ30_502-PadV2)") (class "Default")
      (node (ref "U7") (pin "V2") (pinfunction "PS_DDR_DQ30_502_V2") (pintype "input+no_connect"))
    )
    (net (code "336") (name "unconnected-(U7E-PS_DDR_DQ31_502-PadV3)") (class "Default")
      (node (ref "U7") (pin "V3") (pinfunction "PS_DDR_DQ31_502_V3") (pintype "input+no_connect"))
    )
    (net (code "337") (name "unconnected-(U7E-PS_DDR_DQS_N2_502-PadT2)") (class "Default")
      (node (ref "U7") (pin "T2") (pinfunction "PS_DDR_DQS_N2_502_T2") (pintype "input+no_connect"))
    )
    (net (code "338") (name "unconnected-(U7E-PS_DDR_DQS_N3_502-PadW4)") (class "Default")
      (node (ref "U7") (pin "W4") (pinfunction "PS_DDR_DQS_N3_502_W4") (pintype "input+no_connect"))
    )
    (net (code "339") (name "unconnected-(U7E-PS_DDR_DQS_P2_502-PadR2)") (class "Default")
      (node (ref "U7") (pin "R2") (pinfunction "PS_DDR_DQS_P2_502_R2") (pintype "input+no_connect"))
    )
    (net (code "340") (name "unconnected-(U7E-PS_DDR_DQS_P3_502-PadW5)") (class "Default")
      (node (ref "U7") (pin "W5") (pinfunction "PS_DDR_DQS_P3_502_W5") (pintype "input+no_connect"))
    )
    (net (code "341") (name "unconnected-(U8-CLKB1-Pad13)") (class "Default")
      (node (ref "U8") (pin "13") (pinfunction "CLKB1_13") (pintype "input+no_connect"))
    )
    (net (code "342") (name "unconnected-(U8-CMDB1-Pad12)") (class "Default")
      (node (ref "U8") (pin "12") (pinfunction "CMDB1_12") (pintype "input+no_connect"))
    )
    (net (code "343") (name "unconnected-(U8-DAT0B1-Pad14)") (class "Default")
      (node (ref "U8") (pin "14") (pinfunction "DAT0B1_14") (pintype "input+no_connect"))
    )
    (net (code "344") (name "unconnected-(U8-DAT1B1-Pad15)") (class "Default")
      (node (ref "U8") (pin "15") (pinfunction "DAT1B1_15") (pintype "input+no_connect"))
    )
    (net (code "345") (name "unconnected-(U8-DAT2B1-Pad8)") (class "Default")
      (node (ref "U8") (pin "8") (pinfunction "DAT2B1_8") (pintype "input+no_connect"))
    )
    (net (code "346") (name "unconnected-(U8-DAT3B1-Pad10)") (class "Default")
      (node (ref "U8") (pin "10") (pinfunction "DAT3B1_10") (pintype "input+no_connect"))
    )
    (net (code "347") (name "unconnected-(U9-ACT#-Pad10)") (class "Default")
      (node (ref "U9") (pin "10") (pinfunction "ACT#_10") (pintype "unspecified+no_connect"))
    )
    (net (code "348") (name "unconnected-(U9-CTS-Pad15)") (class "Default")
      (node (ref "U9") (pin "15") (pinfunction "CTS_15") (pintype "unspecified+no_connect"))
    )
    (net (code "349") (name "unconnected-(U9-DCD-Pad11)") (class "Default")
      (node (ref "U9") (pin "11") (pinfunction "DCD_11") (pintype "unspecified+no_connect"))
    )
    (net (code "350") (name "unconnected-(U9-DSR-Pad14)") (class "Default")
      (node (ref "U9") (pin "14") (pinfunction "DSR_14") (pintype "unspecified+no_connect"))
    )
    (net (code "351") (name "unconnected-(U9-DTRTNOW-Pad12)") (class "Default")
      (node (ref "U9") (pin "12") (pinfunction "DTRTNOW_12") (pintype "unspecified+no_connect"))
    )
    (net (code "352") (name "unconnected-(U9-RI-Pad16)") (class "Default")
      (node (ref "U9") (pin "16") (pinfunction "RI_16") (pintype "unspecified+no_connect"))
    )
    (net (code "353") (name "unconnected-(U9-RTS-Pad13)") (class "Default")
      (node (ref "U9") (pin "13") (pinfunction "RTS_13") (pintype "unspecified+no_connect"))
    )
    (net (code "354") (name "unconnected-(U11-DOUT-Pad2)") (class "Default")
      (node (ref "U11") (pin "2") (pinfunction "DOUT_2") (pintype "input+no_connect"))
    )
    (net (code "355") (name "unconnected-(USB1-SBU1-PadA8)") (class "Default")
      (node (ref "USB1") (pin "A8") (pinfunction "SBU1_A8") (pintype "input+no_connect"))
    )
    (net (code "356") (name "unconnected-(USB1-SBU2-PadB8)") (class "Default")
      (node (ref "USB1") (pin "B8") (pinfunction "SBU2_B8") (pintype "input+no_connect"))
    )
    (net (code "357") (name "unconnected-(X1-ST#-Pad1)") (class "Default")
      (node (ref "X1") (pin "1") (pinfunction "ST#_1") (pintype "input+no_connect"))
    )
    (net (code "358") (name "unconnected-(X2-E{slash}D-Pad1)") (class "Default")
      (node (ref "X2") (pin "1") (pinfunction "E/D_1") (pintype "unspecified+no_connect"))
    )
  )
)
